# BE_PROJECT_PCB_final.net
KiCad netlist of a schematic drawn in EAGLE
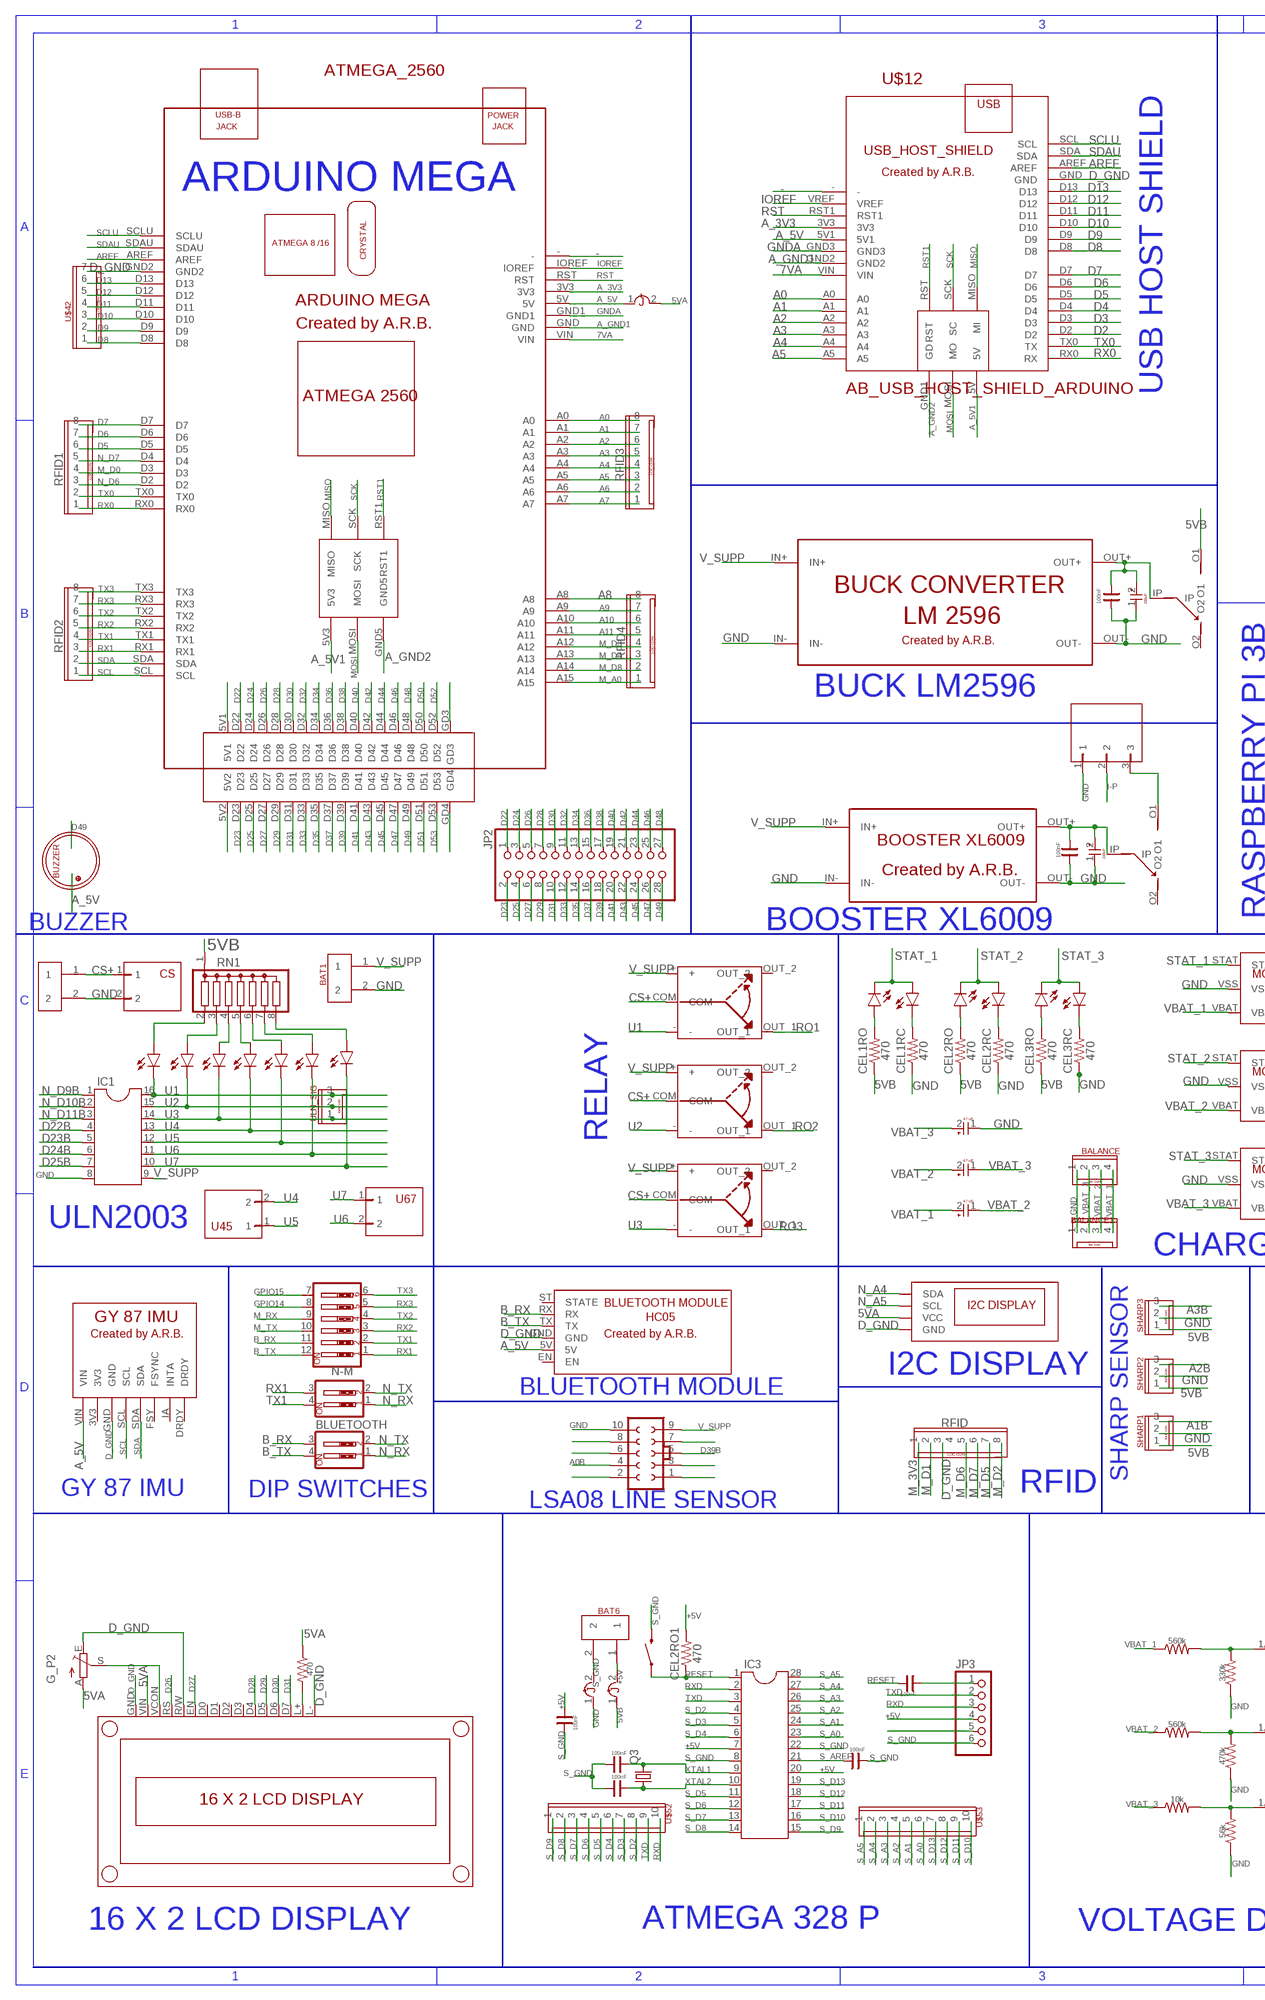
[diagram p0: schematic, sheet 1, part 1 of 3]
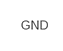
[diagram p1: schematic, sheet 1, part 2 of 3]
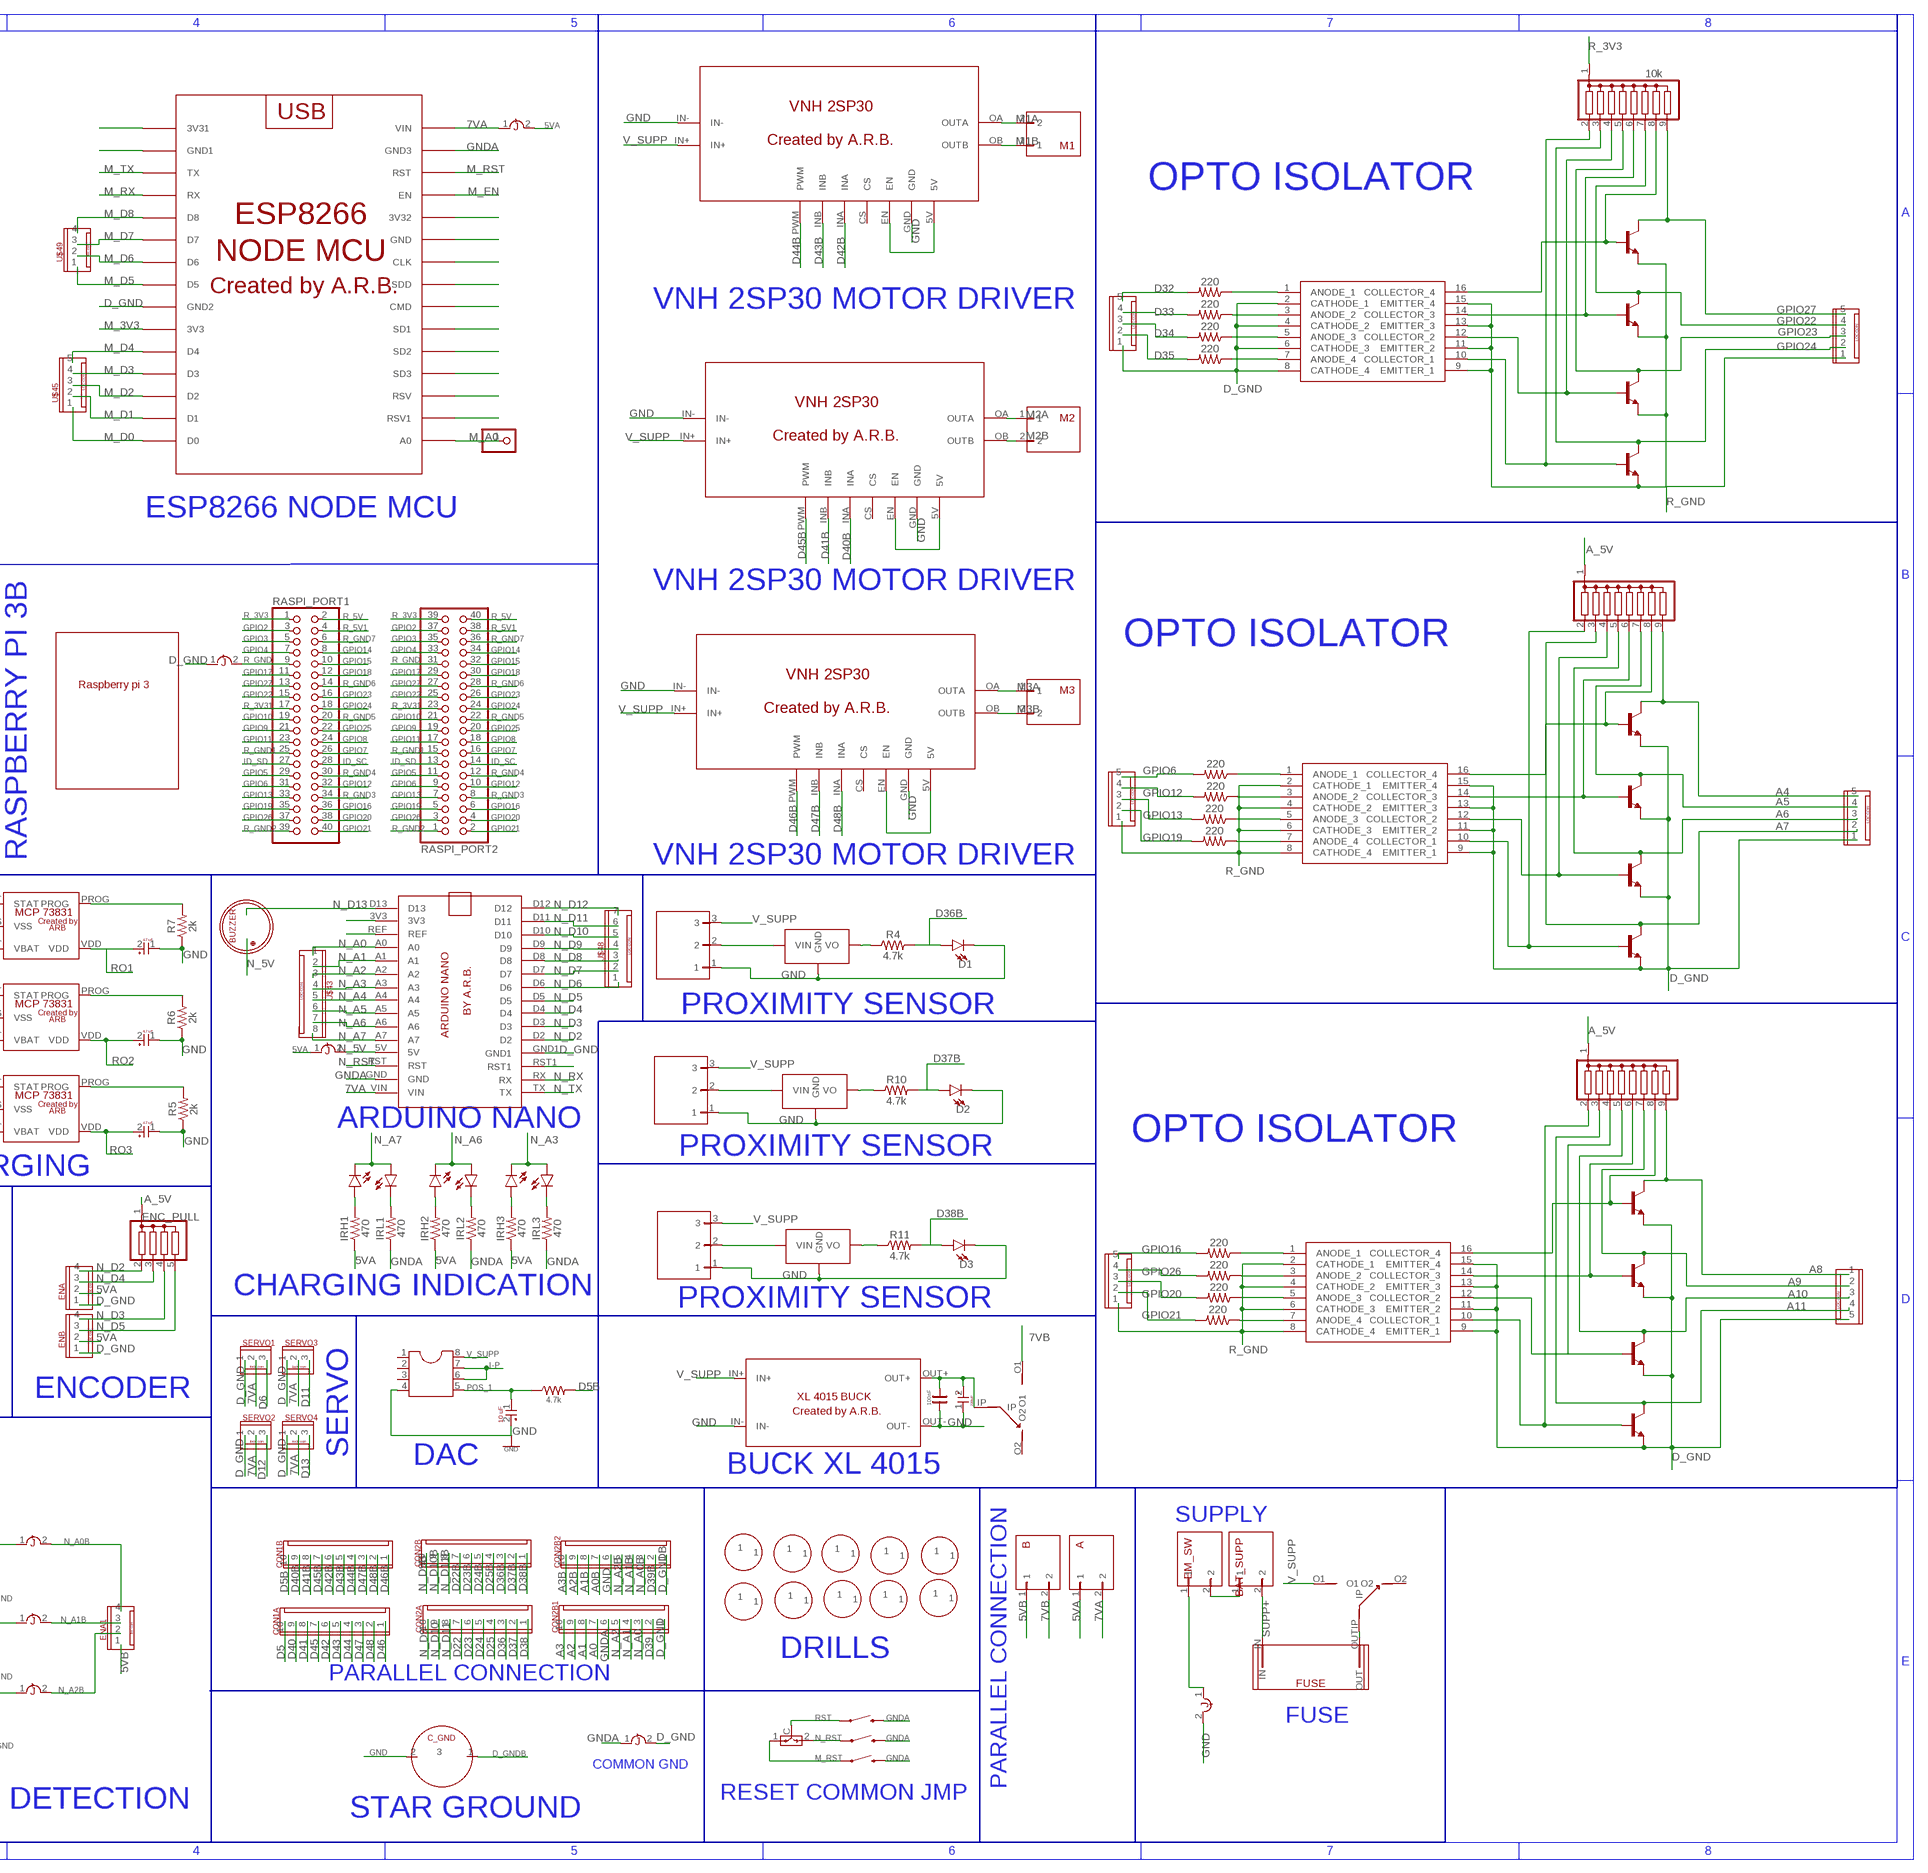
[diagram p2: schematic, sheet 1, part 3 of 3]

(export (version "E")
  (design (tool "Eeschema 10.0.6"))
  (components
    (comp (ref "10K")
      (value "10k")
      (footprint "eagle-import:SIL9")
      (libsource (lib "eagle-import") (part "G08R"))
    )
    (comp (ref "A")
      (value "AB_RIGHT_TER_BLK")
      (footprint "eagle-import:AB_RIGHT_TER_BLK")
      (libsource (lib "eagle-import") (part "AB_RIGHT_TER_BLK"))
    )
    (comp (ref "ATMEGA_2560")
      (value "AB_ARDUINO_MEGA")
      (footprint "eagle-import:AB_ARDUINO_MEGA")
      (libsource (lib "eagle-import") (part "AB_ARDUINO_MEGA"))
    )
    (comp (ref "B")
      (value "AB_RIGHT_TER_BLK")
      (footprint "eagle-import:AB_RIGHT_TER_BLK")
      (libsource (lib "eagle-import") (part "AB_RIGHT_TER_BLK"))
    )
    (comp (ref "BALANCE")
      (value "AB_4PIN_LOC_CONNECTOR")
      (footprint "eagle-import:AB_4PIN_LOC_CONNECTOR")
      (libsource (lib "eagle-import") (part "AB_4PIN_LOC_CONNECTOR"))
    )
    (comp (ref "BALANCE1")
      (value "AB_4PIN_LOC_CONNECTOR")
      (footprint "eagle-import:AB_4PIN_LOC_CONNECTOR")
      (libsource (lib "eagle-import") (part "AB_4PIN_LOC_CONNECTOR"))
    )
    (comp (ref "BAT1")
      (value "AB_SCREW_TERMINAL_5MM_2PIN")
      (footprint "eagle-import:AB_SCREW_TERMINAL_5MM_2PIN")
      (libsource (lib "eagle-import") (part "AB_SCREW_TERMINAL_5MM_2PIN"))
    )
    (comp (ref "BAT6")
      (value "AB_SCREW_TERMINAL_5MM_2PIN")
      (footprint "eagle-import:AB_SCREW_TERMINAL_5MM_2PIN")
      (libsource (lib "eagle-import") (part "AB_SCREW_TERMINAL_5MM_2PIN"))
    )
    (comp (ref "BAT_SUPP")
      (value "AB_RIGHT_TER_BLK")
      (footprint "eagle-import:AB_RIGHT_TER_BLK")
      (libsource (lib "eagle-import") (part "AB_RIGHT_TER_BLK"))
    )
    (comp (ref "BC547")
      (value "BC547")
      (footprint "eagle-import:TO92")
      (libsource (lib "eagle-import") (part "BC547"))
    )
    (comp (ref "BLUETOOTH")
      (value "SW_DIP-2")
      (footprint "eagle-import:EDG-02")
      (libsource (lib "eagle-import") (part "SW_DIP-2"))
    )
    (comp (ref "C1")
      (value "100nF")
      (footprint "eagle-import:C020-035X018")
      (libsource (lib "eagle-import") (part "CNP-C020-035X018"))
    )
    (comp (ref "C2")
      (value "100nF")
      (footprint "eagle-import:C020-035X018")
      (libsource (lib "eagle-import") (part "CNP-C020-035X018"))
    )
    (comp (ref "C3")
      (value "100nF")
      (footprint "eagle-import:C020-035X018")
      (libsource (lib "eagle-import") (part "CNP-C020-035X018"))
    )
    (comp (ref "C4")
      (value "100nF")
      (footprint "eagle-import:C020-035X018")
      (libsource (lib "eagle-import") (part "CNP-C020-035X018"))
    )
    (comp (ref "C5")
      (value "100nF")
      (footprint "eagle-import:C020-035X018")
      (libsource (lib "eagle-import") (part "CNP-C020-035X018"))
    )
    (comp (ref "C6")
      (value "100nF")
      (footprint "eagle-import:C020-035X018")
      (libsource (lib "eagle-import") (part "CNP-C020-035X018"))
    )
    (comp (ref "C7")
      (value "100nF")
      (footprint "eagle-import:C020-035X018")
      (libsource (lib "eagle-import") (part "CNP-C020-035X018"))
    )
    (comp (ref "C8")
      (value "100nF")
      (footprint "eagle-import:C020-035X018")
      (libsource (lib "eagle-import") (part "CNP-C020-035X018"))
    )
    (comp (ref "CEL1CC")
      (value "LED-3MM-NO_SILK")
      (footprint "eagle-import:LED_3MM-NS")
      (libsource (lib "eagle-import") (part "LED-3MM-NO_SILK"))
    )
    (comp (ref "CEL1CO")
      (value "LED-3MM-NO_SILK")
      (footprint "eagle-import:LED_3MM-NS")
      (libsource (lib "eagle-import") (part "LED-3MM-NO_SILK"))
    )
    (comp (ref "CEL1RC")
      (value "470")
      (footprint "eagle-import:AXIAL-0.3")
      (libsource (lib "eagle-import") (part "RESISTORAXIAL-0.3"))
    )
    (comp (ref "CEL1RO")
      (value "470")
      (footprint "eagle-import:AXIAL-0.3")
      (libsource (lib "eagle-import") (part "RESISTORAXIAL-0.3"))
    )
    (comp (ref "CEL2CC")
      (value "LED-3MM-NO_SILK")
      (footprint "eagle-import:LED_3MM-NS")
      (libsource (lib "eagle-import") (part "LED-3MM-NO_SILK"))
    )
    (comp (ref "CEL2CO")
      (value "LED-3MM-NO_SILK")
      (footprint "eagle-import:LED_3MM-NS")
      (libsource (lib "eagle-import") (part "LED-3MM-NO_SILK"))
    )
    (comp (ref "CEL2RC")
      (value "470")
      (footprint "eagle-import:AXIAL-0.3")
      (libsource (lib "eagle-import") (part "RESISTORAXIAL-0.3"))
    )
    (comp (ref "CEL2RO")
      (value "470")
      (footprint "eagle-import:AXIAL-0.3")
      (libsource (lib "eagle-import") (part "RESISTORAXIAL-0.3"))
    )
    (comp (ref "CEL2RO1")
      (value "470")
      (footprint "eagle-import:AXIAL-0.3")
      (libsource (lib "eagle-import") (part "RESISTORAXIAL-0.3"))
    )
    (comp (ref "CEL3CC")
      (value "LED-3MM-NO_SILK")
      (footprint "eagle-import:LED_3MM-NS")
      (libsource (lib "eagle-import") (part "LED-3MM-NO_SILK"))
    )
    (comp (ref "CEL3CO")
      (value "LED-3MM-NO_SILK")
      (footprint "eagle-import:LED_3MM-NS")
      (libsource (lib "eagle-import") (part "LED-3MM-NO_SILK"))
    )
    (comp (ref "CEL3RC")
      (value "470")
      (footprint "eagle-import:AXIAL-0.3")
      (libsource (lib "eagle-import") (part "RESISTORAXIAL-0.3"))
    )
    (comp (ref "CEL3RO")
      (value "470")
      (footprint "eagle-import:AXIAL-0.3")
      (libsource (lib "eagle-import") (part "RESISTORAXIAL-0.3"))
    )
    (comp (ref "CON1A")
      (value "AB_10PIN_LOC_CONNECTOR")
      (footprint "eagle-import:AB_10PIN_LOC_CONNECTOR")
      (libsource (lib "eagle-import") (part "AB_10PIN_LOC_CONNECTOR"))
    )
    (comp (ref "CON1B")
      (value "AB_10PIN_LOC_CONNECTOR")
      (footprint "eagle-import:AB_10PIN_LOC_CONNECTOR")
      (libsource (lib "eagle-import") (part "AB_10PIN_LOC_CONNECTOR"))
    )
    (comp (ref "CON2A")
      (value "AB_10PIN_LOC_CONNECTOR")
      (footprint "eagle-import:AB_10PIN_LOC_CONNECTOR")
      (libsource (lib "eagle-import") (part "AB_10PIN_LOC_CONNECTOR"))
    )
    (comp (ref "CON2B")
      (value "AB_10PIN_LOC_CONNECTOR")
      (footprint "eagle-import:AB_10PIN_LOC_CONNECTOR")
      (libsource (lib "eagle-import") (part "AB_10PIN_LOC_CONNECTOR"))
    )
    (comp (ref "CON2B1")
      (value "AB_10PIN_LOC_CONNECTOR")
      (footprint "eagle-import:AB_10PIN_LOC_CONNECTOR")
      (libsource (lib "eagle-import") (part "AB_10PIN_LOC_CONNECTOR"))
    )
    (comp (ref "CON2B2")
      (value "AB_10PIN_LOC_CONNECTOR")
      (footprint "eagle-import:AB_10PIN_LOC_CONNECTOR")
      (libsource (lib "eagle-import") (part "AB_10PIN_LOC_CONNECTOR"))
    )
    (comp (ref "CS")
      (value "AB_RIGHT_TER_BLK")
      (footprint "eagle-import:AB_RIGHT_TER_BLK")
      (libsource (lib "eagle-import") (part "AB_RIGHT_TER_BLK"))
    )
    (comp (ref "C_GND")
      (value "AB_JOINT_GND")
      (footprint "eagle-import:AB_JOINT_GND")
      (libsource (lib "eagle-import") (part "AB_JOINT_GND"))
    )
    (comp (ref "D1")
      (value "LED-3MM-NO_SILK")
      (footprint "eagle-import:LED_3MM-NS")
      (libsource (lib "eagle-import") (part "LED-3MM-NO_SILK"))
    )
    (comp (ref "D2")
      (value "LED-3MM-NO_SILK")
      (footprint "eagle-import:LED_3MM-NS")
      (libsource (lib "eagle-import") (part "LED-3MM-NO_SILK"))
    )
    (comp (ref "D3")
      (value "LED-3MM-NO_SILK")
      (footprint "eagle-import:LED_3MM-NS")
      (libsource (lib "eagle-import") (part "LED-3MM-NO_SILK"))
    )
    (comp (ref "EM_SW")
      (value "AB_RIGHT_TER_BLK")
      (footprint "eagle-import:AB_RIGHT_TER_BLK")
      (libsource (lib "eagle-import") (part "AB_RIGHT_TER_BLK"))
    )
    (comp (ref "ENA")
      (value "AB_4PIN_LOC_CONNECTOR")
      (footprint "eagle-import:AB_4PIN_LOC_CONNECTOR")
      (libsource (lib "eagle-import") (part "AB_4PIN_LOC_CONNECTOR"))
    )
    (comp (ref "ENA1")
      (value "AB_4PIN_LOC_CONNECTOR")
      (footprint "eagle-import:AB_4PIN_LOC_CONNECTOR")
      (libsource (lib "eagle-import") (part "AB_4PIN_LOC_CONNECTOR"))
    )
    (comp (ref "ENB")
      (value "AB_4PIN_LOC_CONNECTOR")
      (footprint "eagle-import:AB_4PIN_LOC_CONNECTOR")
      (libsource (lib "eagle-import") (part "AB_4PIN_LOC_CONNECTOR"))
    )
    (comp (ref "ENC_PULL")
      (value "G04R")
      (footprint "eagle-import:SIL5")
      (libsource (lib "eagle-import") (part "G04R"))
    )
    (comp (ref "FUSE")
      (value "AB_FUSE_HOLDER")
      (footprint "eagle-import:AB_FUSE_HOLDER")
      (libsource (lib "eagle-import") (part "AB_FUSE_HOLDER"))
    )
    (comp (ref "G_P2")
      (value "TRIM_EU-RS3")
      (footprint "eagle-import:RS3")
      (libsource (lib "eagle-import") (part "TRIM_EU-RS3"))
    )
    (comp (ref "IC1")
      (value "DIL16S")
      (footprint "eagle-import:SOCKET-16")
      (libsource (lib "eagle-import") (part "DIL16S"))
    )
    (comp (ref "IC2")
      (value "DIL8S")
      (footprint "eagle-import:SOCKET-08")
      (fields (field (name "SPICEPREFIX") "X"))
      (libsource (lib "eagle-import") (part "DIL8S"))
    )
    (comp (ref "IC3")
      (value "DIL28-3")
      (footprint "eagle-import:DIL28-3")
      (libsource (lib "eagle-import") (part "DIL28-3"))
    )
    (comp (ref "IC8")
      (value "TLP281-4(GB,J,F)")
      (footprint "eagle-import:SOIC127P700X210-16N")
      (fields
        (field (name "MOUSER_PART_NUMBER") "757-TLP281-4(GB,J,F)")
        (field (name "RS_PART_NUMBER") "7603227P")
      )
      (libsource (lib "eagle-import") (part "TLP281-4(GB,J,F)"))
    )
    (comp (ref "IC9")
      (value "TLP281-4(GB,J,F)")
      (footprint "eagle-import:SOIC127P700X210-16N")
      (fields
        (field (name "MOUSER_PART_NUMBER") "757-TLP281-4(GB,J,F)")
        (field (name "RS_PART_NUMBER") "7603227P")
      )
      (libsource (lib "eagle-import") (part "TLP281-4(GB,J,F)"))
    )
    (comp (ref "IC10")
      (value "TLP281-4(GB,J,F)")
      (footprint "eagle-import:SOIC127P700X210-16N")
      (fields
        (field (name "MOUSER_PART_NUMBER") "757-TLP281-4(GB,J,F)")
        (field (name "RS_PART_NUMBER") "7603227P")
      )
      (libsource (lib "eagle-import") (part "TLP281-4(GB,J,F)"))
    )
    (comp (ref "IH1")
      (value "LED-3MM-NO_SILK")
      (footprint "eagle-import:LED_3MM-NS")
      (libsource (lib "eagle-import") (part "LED-3MM-NO_SILK"))
    )
    (comp (ref "IH2")
      (value "LED-3MM-NO_SILK")
      (footprint "eagle-import:LED_3MM-NS")
      (libsource (lib "eagle-import") (part "LED-3MM-NO_SILK"))
    )
    (comp (ref "IH3")
      (value "LED-3MM-NO_SILK")
      (footprint "eagle-import:LED_3MM-NS")
      (libsource (lib "eagle-import") (part "LED-3MM-NO_SILK"))
    )
    (comp (ref "IL1")
      (value "LED-3MM-NO_SILK")
      (footprint "eagle-import:LED_3MM-NS")
      (libsource (lib "eagle-import") (part "LED-3MM-NO_SILK"))
    )
    (comp (ref "IL2")
      (value "LED-3MM-NO_SILK")
      (footprint "eagle-import:LED_3MM-NS")
      (libsource (lib "eagle-import") (part "LED-3MM-NO_SILK"))
    )
    (comp (ref "IL3")
      (value "LED-3MM-NO_SILK")
      (footprint "eagle-import:LED_3MM-NS")
      (libsource (lib "eagle-import") (part "LED-3MM-NO_SILK"))
    )
    (comp (ref "IRH1")
      (value "470")
      (footprint "eagle-import:AXIAL-0.3")
      (libsource (lib "eagle-import") (part "RESISTORAXIAL-0.3"))
    )
    (comp (ref "IRH2")
      (value "470")
      (footprint "eagle-import:AXIAL-0.3")
      (libsource (lib "eagle-import") (part "RESISTORAXIAL-0.3"))
    )
    (comp (ref "IRH3")
      (value "470")
      (footprint "eagle-import:AXIAL-0.3")
      (libsource (lib "eagle-import") (part "RESISTORAXIAL-0.3"))
    )
    (comp (ref "IRL1")
      (value "470")
      (footprint "eagle-import:AXIAL-0.3")
      (libsource (lib "eagle-import") (part "RESISTORAXIAL-0.3"))
    )
    (comp (ref "IRL2")
      (value "470")
      (footprint "eagle-import:AXIAL-0.3")
      (libsource (lib "eagle-import") (part "RESISTORAXIAL-0.3"))
    )
    (comp (ref "IRL3")
      (value "470")
      (footprint "eagle-import:AXIAL-0.3")
      (libsource (lib "eagle-import") (part "RESISTORAXIAL-0.3"))
    )
    (comp (ref "JP1")
      (value "PINHD-1X1")
      (footprint "eagle-import:1X01")
      (libsource (lib "eagle-import") (part "PINHD-1X1"))
    )
    (comp (ref "JP2")
      (value "PINHD-2X14")
      (footprint "eagle-import:2X14")
      (libsource (lib "eagle-import") (part "PINHD-2X14"))
    )
    (comp (ref "JP3")
      (value "PINHD-1X6")
      (footprint "eagle-import:1X06")
      (libsource (lib "eagle-import") (part "PINHD-1X6"))
    )
    (comp (ref "L1")
      (value "LED-3MM-NO_SILK")
      (footprint "eagle-import:LED_3MM-NS")
      (libsource (lib "eagle-import") (part "LED-3MM-NO_SILK"))
    )
    (comp (ref "L2")
      (value "LED-3MM-NO_SILK")
      (footprint "eagle-import:LED_3MM-NS")
      (libsource (lib "eagle-import") (part "LED-3MM-NO_SILK"))
    )
    (comp (ref "L3")
      (value "LED-3MM-NO_SILK")
      (footprint "eagle-import:LED_3MM-NS")
      (libsource (lib "eagle-import") (part "LED-3MM-NO_SILK"))
    )
    (comp (ref "L4")
      (value "LED-3MM-NO_SILK")
      (footprint "eagle-import:LED_3MM-NS")
      (libsource (lib "eagle-import") (part "LED-3MM-NO_SILK"))
    )
    (comp (ref "L5")
      (value "LED-3MM-NO_SILK")
      (footprint "eagle-import:LED_3MM-NS")
      (libsource (lib "eagle-import") (part "LED-3MM-NO_SILK"))
    )
    (comp (ref "L6")
      (value "LED-3MM-NO_SILK")
      (footprint "eagle-import:LED_3MM-NS")
      (libsource (lib "eagle-import") (part "LED-3MM-NO_SILK"))
    )
    (comp (ref "L7")
      (value "LED-3MM-NO_SILK")
      (footprint "eagle-import:LED_3MM-NS")
      (libsource (lib "eagle-import") (part "LED-3MM-NO_SILK"))
    )
    (comp (ref "LSA_2")
      (value "LSA1")
      (footprint "eagle-import:S10V")
      (libsource (lib "eagle-import") (part "SOCKET-10V"))
    )
    (comp (ref "M1")
      (value "AB_RIGHT_TER_BLK")
      (footprint "eagle-import:AB_RIGHT_TER_BLK")
      (libsource (lib "eagle-import") (part "AB_RIGHT_TER_BLK"))
    )
    (comp (ref "M2")
      (value "AB_RIGHT_TER_BLK")
      (footprint "eagle-import:AB_RIGHT_TER_BLK")
      (libsource (lib "eagle-import") (part "AB_RIGHT_TER_BLK"))
    )
    (comp (ref "M3")
      (value "AB_RIGHT_TER_BLK")
      (footprint "eagle-import:AB_RIGHT_TER_BLK")
      (libsource (lib "eagle-import") (part "AB_RIGHT_TER_BLK"))
    )
    (comp (ref "MEGA_RST")
      (value "MOMENTARY-SWITCH-SPST-PTH-6.0MM")
      (footprint "eagle-import:TACTILE_SWITCH_PTH_6.0MM")
      (libsource (lib "eagle-import") (part "MOMENTARY-SWITCH-SPST-PTH-6.0MM"))
    )
    (comp (ref "MEGA_RST1")
      (value "MOMENTARY-SWITCH-SPST-PTH-6.0MM")
      (footprint "eagle-import:TACTILE_SWITCH_PTH_6.0MM")
      (libsource (lib "eagle-import") (part "MOMENTARY-SWITCH-SPST-PTH-6.0MM"))
    )
    (comp (ref "M_RST")
      (value "MOMENTARY-SWITCH-SPST-PTH-6.0MM")
      (footprint "eagle-import:TACTILE_SWITCH_PTH_6.0MM")
      (libsource (lib "eagle-import") (part "MOMENTARY-SWITCH-SPST-PTH-6.0MM"))
    )
    (comp (ref "N-M")
      (value "SW_DIP-2")
      (footprint "eagle-import:EDG-02")
      (libsource (lib "eagle-import") (part "SW_DIP-2"))
    )
    (comp (ref "NANO")
      (value "AB_JUMPER_ONE_WAY")
      (footprint "eagle-import:AB_JUMPER_ONE_WAY")
      (libsource (lib "eagle-import") (part "AB_JUMPER_ONE_WAY"))
    )
    (comp (ref "NODEMCU")
      (value "AB_JUMPER_ONE_WAY")
      (footprint "eagle-import:AB_JUMPER_ONE_WAY")
      (libsource (lib "eagle-import") (part "AB_JUMPER_ONE_WAY"))
    )
    (comp (ref "N_RST")
      (value "MOMENTARY-SWITCH-SPST-PTH-6.0MM")
      (footprint "eagle-import:TACTILE_SWITCH_PTH_6.0MM")
      (libsource (lib "eagle-import") (part "MOMENTARY-SWITCH-SPST-PTH-6.0MM"))
    )
    (comp (ref "OISO1")
      (value "AB_5PIN_LOC_CONNECTOR")
      (footprint "eagle-import:AB_5PIN_LOC_CONNECTOR")
      (fields (field (name "SPICEPREFIX") "X"))
      (libsource (lib "eagle-import") (part "AB_5PIN_LOC_CONNECTOR"))
    )
    (comp (ref "OISO2")
      (value "AB_5PIN_LOC_CONNECTOR")
      (footprint "eagle-import:AB_5PIN_LOC_CONNECTOR")
      (fields (field (name "SPICEPREFIX") "X"))
      (libsource (lib "eagle-import") (part "AB_5PIN_LOC_CONNECTOR"))
    )
    (comp (ref "OISO3")
      (value "AB_5PIN_LOC_CONNECTOR")
      (footprint "eagle-import:AB_5PIN_LOC_CONNECTOR")
      (fields (field (name "SPICEPREFIX") "X"))
      (libsource (lib "eagle-import") (part "AB_5PIN_LOC_CONNECTOR"))
    )
    (comp (ref "OISO4")
      (value "AB_5PIN_LOC_CONNECTOR")
      (footprint "eagle-import:AB_5PIN_LOC_CONNECTOR")
      (fields (field (name "SPICEPREFIX") "X"))
      (libsource (lib "eagle-import") (part "AB_5PIN_LOC_CONNECTOR"))
    )
    (comp (ref "OISO5")
      (value "AB_5PIN_LOC_CONNECTOR")
      (footprint "eagle-import:AB_5PIN_LOC_CONNECTOR")
      (fields (field (name "SPICEPREFIX") "X"))
      (libsource (lib "eagle-import") (part "AB_5PIN_LOC_CONNECTOR"))
    )
    (comp (ref "OISO6")
      (value "AB_5PIN_LOC_CONNECTOR")
      (footprint "eagle-import:AB_5PIN_LOC_CONNECTOR")
      (fields (field (name "SPICEPREFIX") "X"))
      (libsource (lib "eagle-import") (part "AB_5PIN_LOC_CONNECTOR"))
    )
    (comp (ref "PPR_R1")
      (value "4.7k")
      (footprint "eagle-import:AXIAL-0.3")
      (libsource (lib "eagle-import") (part "RESISTORAXIAL-0.3"))
    )
    (comp (ref "PROX1")
      (value "AB_RIGHT_TER_BLK_3PIN")
      (footprint "eagle-import:AB_RIGHT_TER_BLK_3PIN")
      (libsource (lib "eagle-import") (part "AB_RIGHT_TER_BLK_3PIN"))
    )
    (comp (ref "PROX2")
      (value "AB_RIGHT_TER_BLK_3PIN")
      (footprint "eagle-import:AB_RIGHT_TER_BLK_3PIN")
      (libsource (lib "eagle-import") (part "AB_RIGHT_TER_BLK_3PIN"))
    )
    (comp (ref "PROX3")
      (value "AB_RIGHT_TER_BLK_3PIN")
      (footprint "eagle-import:AB_RIGHT_TER_BLK_3PIN")
      (libsource (lib "eagle-import") (part "AB_RIGHT_TER_BLK_3PIN"))
    )
    (comp (ref "Q3")
      (value "CRYSTALHC49U-V")
      (footprint "eagle-import:HC49U-V")
      (libsource (lib "eagle-import") (part "CRYSTALHC49U-V"))
    )
    (comp (ref "R2")
      (value "560k")
      (footprint "eagle-import:AXIAL-0.3")
      (libsource (lib "eagle-import") (part "RESISTORAXIAL-0.3"))
    )
    (comp (ref "R4")
      (value "4.7k")
      (footprint "eagle-import:AXIAL-0.3")
      (libsource (lib "eagle-import") (part "RESISTORAXIAL-0.3"))
    )
    (comp (ref "R5")
      (value "2k")
      (footprint "eagle-import:AXIAL-0.3")
      (libsource (lib "eagle-import") (part "RESISTORAXIAL-0.3"))
    )
    (comp (ref "R6")
      (value "2k")
      (footprint "eagle-import:AXIAL-0.3")
      (libsource (lib "eagle-import") (part "RESISTORAXIAL-0.3"))
    )
    (comp (ref "R7")
      (value "2k")
      (footprint "eagle-import:AXIAL-0.3")
      (libsource (lib "eagle-import") (part "RESISTORAXIAL-0.3"))
    )
    (comp (ref "R10")
      (value "4.7k")
      (footprint "eagle-import:AXIAL-0.3")
      (libsource (lib "eagle-import") (part "RESISTORAXIAL-0.3"))
    )
    (comp (ref "R11")
      (value "4.7k")
      (footprint "eagle-import:AXIAL-0.3")
      (libsource (lib "eagle-import") (part "RESISTORAXIAL-0.3"))
    )
    (comp (ref "R17")
      (value "470")
      (footprint "eagle-import:AXIAL-0.3")
      (libsource (lib "eagle-import") (part "RESISTORAXIAL-0.3"))
    )
    (comp (ref "R18")
      (value "220")
      (footprint "eagle-import:AXIAL-0.3")
      (libsource (lib "eagle-import") (part "RESISTORAXIAL-0.3"))
    )
    (comp (ref "R19")
      (value "220")
      (footprint "eagle-import:AXIAL-0.3")
      (libsource (lib "eagle-import") (part "RESISTORAXIAL-0.3"))
    )
    (comp (ref "R20")
      (value "220")
      (footprint "eagle-import:AXIAL-0.3")
      (libsource (lib "eagle-import") (part "RESISTORAXIAL-0.3"))
    )
    (comp (ref "R21")
      (value "220")
      (footprint "eagle-import:AXIAL-0.3")
      (libsource (lib "eagle-import") (part "RESISTORAXIAL-0.3"))
    )
    (comp (ref "R22")
      (value "220")
      (footprint "eagle-import:AXIAL-0.3")
      (libsource (lib "eagle-import") (part "RESISTORAXIAL-0.3"))
    )
    (comp (ref "R23")
      (value "220")
      (footprint "eagle-import:AXIAL-0.3")
      (libsource (lib "eagle-import") (part "RESISTORAXIAL-0.3"))
    )
    (comp (ref "R24")
      (value "220")
      (footprint "eagle-import:AXIAL-0.3")
      (libsource (lib "eagle-import") (part "RESISTORAXIAL-0.3"))
    )
    (comp (ref "R25")
      (value "220")
      (footprint "eagle-import:AXIAL-0.3")
      (libsource (lib "eagle-import") (part "RESISTORAXIAL-0.3"))
    )
    (comp (ref "R26")
      (value "220")
      (footprint "eagle-import:AXIAL-0.3")
      (libsource (lib "eagle-import") (part "RESISTORAXIAL-0.3"))
    )
    (comp (ref "R27")
      (value "220")
      (footprint "eagle-import:AXIAL-0.3")
      (libsource (lib "eagle-import") (part "RESISTORAXIAL-0.3"))
    )
    (comp (ref "R28")
      (value "220")
      (footprint "eagle-import:AXIAL-0.3")
      (libsource (lib "eagle-import") (part "RESISTORAXIAL-0.3"))
    )
    (comp (ref "R32")
      (value "220")
      (footprint "eagle-import:AXIAL-0.3")
      (libsource (lib "eagle-import") (part "RESISTORAXIAL-0.3"))
    )
    (comp (ref "R34")
      (value "330k")
      (footprint "eagle-import:AXIAL-0.3")
      (libsource (lib "eagle-import") (part "RESISTORAXIAL-0.3"))
    )
    (comp (ref "R35")
      (value "560k")
      (footprint "eagle-import:AXIAL-0.3")
      (libsource (lib "eagle-import") (part "RESISTORAXIAL-0.3"))
    )
    (comp (ref "R36")
      (value "470k")
      (footprint "eagle-import:AXIAL-0.3")
      (libsource (lib "eagle-import") (part "RESISTORAXIAL-0.3"))
    )
    (comp (ref "R37")
      (value "10k")
      (footprint "eagle-import:AXIAL-0.3")
      (libsource (lib "eagle-import") (part "RESISTORAXIAL-0.3"))
    )
    (comp (ref "R38")
      (value "56k")
      (footprint "eagle-import:AXIAL-0.3")
      (libsource (lib "eagle-import") (part "RESISTORAXIAL-0.3"))
    )
    (comp (ref "RASPI_PORT1")
      (value "PINHD-2X20")
      (footprint "eagle-import:2X20")
      (libsource (lib "eagle-import") (part "PINHD-2X20"))
    )
    (comp (ref "RASPI_PORT2")
      (value "PINHD-2X20")
      (footprint "eagle-import:2X20")
      (libsource (lib "eagle-import") (part "PINHD-2X20"))
    )
    (comp (ref "REL1")
      (value "12v")
      (footprint "eagle-import:AB_ELECTROMAGNETIC_RELAY")
      (libsource (lib "eagle-import") (part "AB_ELECTROMAGNETIC_RELAY"))
    )
    (comp (ref "REL2")
      (value "12v")
      (footprint "eagle-import:AB_ELECTROMAGNETIC_RELAY")
      (libsource (lib "eagle-import") (part "AB_ELECTROMAGNETIC_RELAY"))
    )
    (comp (ref "REL3")
      (value "12v")
      (footprint "eagle-import:AB_ELECTROMAGNETIC_RELAY")
      (libsource (lib "eagle-import") (part "AB_ELECTROMAGNETIC_RELAY"))
    )
    (comp (ref "RFID")
      (value "AB_8PIN_LOC_CONNECTOR")
      (footprint "eagle-import:AB_8PIN_LOC_CONNECTOR")
      (libsource (lib "eagle-import") (part "AB_8PIN_LOC_CONNECTOR"))
    )
    (comp (ref "RFID1")
      (value "AB_8PIN_LOC_CONNECTOR")
      (footprint "eagle-import:AB_8PIN_LOC_CONNECTOR")
      (libsource (lib "eagle-import") (part "AB_8PIN_LOC_CONNECTOR"))
    )
    (comp (ref "RFID2")
      (value "AB_8PIN_LOC_CONNECTOR")
      (footprint "eagle-import:AB_8PIN_LOC_CONNECTOR")
      (libsource (lib "eagle-import") (part "AB_8PIN_LOC_CONNECTOR"))
    )
    (comp (ref "RFID3")
      (value "AB_8PIN_LOC_CONNECTOR")
      (footprint "eagle-import:AB_8PIN_LOC_CONNECTOR")
      (libsource (lib "eagle-import") (part "AB_8PIN_LOC_CONNECTOR"))
    )
    (comp (ref "RFID4")
      (value "AB_8PIN_LOC_CONNECTOR")
      (footprint "eagle-import:AB_8PIN_LOC_CONNECTOR")
      (libsource (lib "eagle-import") (part "AB_8PIN_LOC_CONNECTOR"))
    )
    (comp (ref "RN1")
      (value "G07R")
      (footprint "eagle-import:SIL8")
      (libsource (lib "eagle-import") (part "G07R"))
    )
    (comp (ref "RN6")
      (value "G08R")
      (footprint "eagle-import:SIL9")
      (libsource (lib "eagle-import") (part "G08R"))
    )
    (comp (ref "RN7")
      (value "G08R")
      (footprint "eagle-import:SIL9")
      (libsource (lib "eagle-import") (part "G08R"))
    )
    (comp (ref "SERVO1")
      (value "AB_3PIN_LOC_CONNECTOR")
      (footprint "eagle-import:AB_3PIN_LOC_CONNECTOR")
      (libsource (lib "eagle-import") (part "AB_3PIN_LOC_CONNECTOR"))
    )
    (comp (ref "SERVO2")
      (value "AB_3PIN_LOC_CONNECTOR")
      (footprint "eagle-import:AB_3PIN_LOC_CONNECTOR")
      (libsource (lib "eagle-import") (part "AB_3PIN_LOC_CONNECTOR"))
    )
    (comp (ref "SERVO3")
      (value "AB_3PIN_LOC_CONNECTOR")
      (footprint "eagle-import:AB_3PIN_LOC_CONNECTOR")
      (libsource (lib "eagle-import") (part "AB_3PIN_LOC_CONNECTOR"))
    )
    (comp (ref "SERVO4")
      (value "AB_3PIN_LOC_CONNECTOR")
      (footprint "eagle-import:AB_3PIN_LOC_CONNECTOR")
      (libsource (lib "eagle-import") (part "AB_3PIN_LOC_CONNECTOR"))
    )
    (comp (ref "SHARP1")
      (value "AB_3PIN_LOC_CONNECTOR")
      (footprint "eagle-import:AB_3PIN_LOC_CONNECTOR")
      (libsource (lib "eagle-import") (part "AB_3PIN_LOC_CONNECTOR"))
    )
    (comp (ref "SHARP2")
      (value "AB_3PIN_LOC_CONNECTOR")
      (footprint "eagle-import:AB_3PIN_LOC_CONNECTOR")
      (libsource (lib "eagle-import") (part "AB_3PIN_LOC_CONNECTOR"))
    )
    (comp (ref "SHARP3")
      (value "AB_3PIN_LOC_CONNECTOR")
      (footprint "eagle-import:AB_3PIN_LOC_CONNECTOR")
      (libsource (lib "eagle-import") (part "AB_3PIN_LOC_CONNECTOR"))
    )
    (comp (ref "SW1")
      (value "SW_DIP-6")
      (footprint "eagle-import:EDG-06")
      (libsource (lib "eagle-import") (part "SW_DIP-6"))
    )
    (comp (ref "TR14")
      (value "BC547")
      (footprint "eagle-import:TO92")
      (libsource (lib "eagle-import") (part "BC547"))
    )
    (comp (ref "TR15")
      (value "BC547")
      (footprint "eagle-import:TO92")
      (libsource (lib "eagle-import") (part "BC547"))
    )
    (comp (ref "TR16")
      (value "BC547")
      (footprint "eagle-import:TO92")
      (libsource (lib "eagle-import") (part "BC547"))
    )
    (comp (ref "TR17")
      (value "BC547")
      (footprint "eagle-import:TO92")
      (libsource (lib "eagle-import") (part "BC547"))
    )
    (comp (ref "TR18")
      (value "BC547")
      (footprint "eagle-import:TO92")
      (libsource (lib "eagle-import") (part "BC547"))
    )
    (comp (ref "TR19")
      (value "BC547")
      (footprint "eagle-import:TO92")
      (libsource (lib "eagle-import") (part "BC547"))
    )
    (comp (ref "TR20")
      (value "BC547")
      (footprint "eagle-import:TO92")
      (libsource (lib "eagle-import") (part "BC547"))
    )
    (comp (ref "TR21")
      (value "BC547")
      (footprint "eagle-import:TO92")
      (libsource (lib "eagle-import") (part "BC547"))
    )
    (comp (ref "TR22")
      (value "BC547")
      (footprint "eagle-import:TO92")
      (libsource (lib "eagle-import") (part "BC547"))
    )
    (comp (ref "TR23")
      (value "BC547")
      (footprint "eagle-import:TO92")
      (libsource (lib "eagle-import") (part "BC547"))
    )
    (comp (ref "TR24")
      (value "BC547")
      (footprint "eagle-import:TO92")
      (libsource (lib "eagle-import") (part "BC547"))
    )
    (comp (ref "U$1")
      (value "AB_JUMPER_ONE_WAY")
      (footprint "eagle-import:AB_JUMPER_ONE_WAY")
      (libsource (lib "eagle-import") (part "AB_JUMPER_ONE_WAY"))
    )
    (comp (ref "U$2")
      (value "AB_16X2_LCD_DISPLAY")
      (footprint "eagle-import:AB_16X2_LCD_DISPLAY")
      (libsource (lib "eagle-import") (part "AB_16X2_LCD_DISPLAY"))
    )
    (comp (ref "U$3")
      (value "AB_VNH2SP30")
      (footprint "eagle-import:AB_VNH2SP30_MODULE")
      (libsource (lib "eagle-import") (part "AB_VNH2SP30"))
    )
    (comp (ref "U$4")
      (value "ESP8266_NODEMCU_BY_AB")
      (footprint "eagle-import:AB_ESP8266_BREAKOUT")
      (libsource (lib "eagle-import") (part "ESP8266_NODEMCU_BY_AB"))
    )
    (comp (ref "U$5")
      (value "AB_RASPBERRY_PI_3")
      (footprint "eagle-import:AB_RASPBERRY_PI_3")
      (libsource (lib "eagle-import") (part "AB_RASPBERRY_PI_3"))
    )
    (comp (ref "U$6")
      (value "AB_VNH2SP30")
      (footprint "eagle-import:AB_VNH2SP30_MODULE")
      (libsource (lib "eagle-import") (part "AB_VNH2SP30"))
    )
    (comp (ref "U$7")
      (value "AB_LM2596_BUCK_CONVERTER")
      (footprint "eagle-import:AB_LM2596_BUCK_CONVERTER")
      (libsource (lib "eagle-import") (part "AB_LM2596_BUCK_CONVERTER"))
    )
    (comp (ref "U$8")
      (value "AB_XL6009_BOOST_CONVERTER")
      (footprint "eagle-import:AB_XL6009E1_BOOST_CONVERTER")
      (libsource (lib "eagle-import") (part "AB_XL6009_BOOST_CONVERTER"))
    )
    (comp (ref "U$9")
      (value "AB_VNH2SP30")
      (footprint "eagle-import:AB_VNH2SP30_MODULE")
      (libsource (lib "eagle-import") (part "AB_VNH2SP30"))
    )
    (comp (ref "U$10")
      (value "AB_GY87")
      (footprint "eagle-import:AB_IMU_GY87")
      (libsource (lib "eagle-import") (part "AB_GY87"))
    )
    (comp (ref "U$11")
      (value "AB_BLUETOOTH_HC05")
      (footprint "eagle-import:AB_BLUETOOTH_HC05")
      (libsource (lib "eagle-import") (part "AB_BLUETOOTH_HC05"))
    )
    (comp (ref "U$12")
      (value "AB_USB_HOST_SHIELD_ARDUINO")
      (footprint "eagle-import:AB_USB_HOST_SHIELD_ARDUINO")
      (libsource (lib "eagle-import") (part "AB_USB_HOST_SHIELD_ARDUINO"))
    )
    (comp (ref "U$13")
      (value "AB_XL4015_5A_")
      (footprint "eagle-import:AB_XL_4015_5A_BUCK")
      (libsource (lib "eagle-import") (part "AB_XL4015_5A_"))
    )
    (comp (ref "U$14")
      (value "AB_SW")
      (footprint "eagle-import:AB_SW")
      (libsource (lib "eagle-import") (part "AB_SW"))
    )
    (comp (ref "U$15")
      (value "AB_SW")
      (footprint "eagle-import:AB_SW")
      (libsource (lib "eagle-import") (part "AB_SW"))
    )
    (comp (ref "U$16")
      (value "AB_SW")
      (footprint "eagle-import:AB_SW")
      (libsource (lib "eagle-import") (part "AB_SW"))
    )
    (comp (ref "U$17")
      (value "AB_JUMPER_ONE_WAY")
      (footprint "eagle-import:AB_JUMPER_ONE_WAY")
      (libsource (lib "eagle-import") (part "AB_JUMPER_ONE_WAY"))
    )
    (comp (ref "U$18")
      (value "AB_MCP_73831_LIPO_CHARGER")
      (footprint "eagle-import:AB_MCP_73831_LIPO_CHARGER")
      (libsource (lib "eagle-import") (part "AB_MCP_73831_LIPO_CHARGER"))
    )
    (comp (ref "U$19")
      (value "AB_MCP_73831_LIPO_CHARGER")
      (footprint "eagle-import:AB_MCP_73831_LIPO_CHARGER")
      (libsource (lib "eagle-import") (part "AB_MCP_73831_LIPO_CHARGER"))
    )
    (comp (ref "U$20")
      (value "AB_MCP_73831_LIPO_CHARGER")
      (footprint "eagle-import:AB_MCP_73831_LIPO_CHARGER")
      (libsource (lib "eagle-import") (part "AB_MCP_73831_LIPO_CHARGER"))
    )
    (comp (ref "U$21")
      (value "4.7 uF")
      (footprint "eagle-import:AB_POL_CAP")
      (libsource (lib "eagle-import") (part "AB_POL_CAP"))
    )
    (comp (ref "U$22")
      (value "4.7 uF")
      (footprint "eagle-import:AB_POL_CAP")
      (libsource (lib "eagle-import") (part "AB_POL_CAP"))
    )
    (comp (ref "U$23")
      (value "4.7 uF")
      (footprint "eagle-import:AB_POL_CAP")
      (libsource (lib "eagle-import") (part "AB_POL_CAP"))
    )
    (comp (ref "U$24")
      (value "AB_0.91_INCH_I2C_DISPLAY")
      (footprint "eagle-import:AB_0.91INCH_I2C_DISPLAY")
      (libsource (lib "eagle-import") (part "AB_0.91_INCH_I2C_DISPLAY"))
    )
    (comp (ref "U$25")
      (value "4.7 uF")
      (footprint "eagle-import:AB_POL_CAP")
      (libsource (lib "eagle-import") (part "AB_POL_CAP"))
    )
    (comp (ref "U$26")
      (value "4.7 uF")
      (footprint "eagle-import:AB_POL_CAP")
      (libsource (lib "eagle-import") (part "AB_POL_CAP"))
    )
    (comp (ref "U$27")
      (value "4.7 uF")
      (footprint "eagle-import:AB_POL_CAP")
      (libsource (lib "eagle-import") (part "AB_POL_CAP"))
    )
    (comp (ref "U$28")
      (value "AB_BUZZER")
      (footprint "eagle-import:AB_BUZZER")
      (libsource (lib "eagle-import") (part "AB_BUZZER"))
    )
    (comp (ref "U$29")
      (value "10 uF")
      (footprint "eagle-import:AB_POL_CAP")
      (libsource (lib "eagle-import") (part "AB_POL_CAP"))
    )
    (comp (ref "U$30")
      (value "AB_JUMPER_TWO_WAY")
      (footprint "eagle-import:AB_JUMPER_TWO_WAY")
      (libsource (lib "eagle-import") (part "AB_JUMPER_TWO_WAY"))
    )
    (comp (ref "U$31")
      (value "AB_JUMPER_ONE_WAY")
      (footprint "eagle-import:AB_JUMPER_ONE_WAY")
      (libsource (lib "eagle-import") (part "AB_JUMPER_ONE_WAY"))
    )
    (comp (ref "U$32")
      (value "AB_SW")
      (footprint "eagle-import:AB_SW")
      (libsource (lib "eagle-import") (part "AB_SW"))
    )
    (comp (ref "U$33")
      (value "AB_JUMPER_ONE_WAY")
      (footprint "eagle-import:AB_JUMPER_ONE_WAY")
      (libsource (lib "eagle-import") (part "AB_JUMPER_ONE_WAY"))
    )
    (comp (ref "U$34")
      (value "220uF")
      (footprint "eagle-import:AB_POL_CAP")
      (libsource (lib "eagle-import") (part "AB_POL_CAP"))
    )
    (comp (ref "U$35")
      (value "AB_ARDUINO_NANO")
      (footprint "eagle-import:AB_ARDUINO_NANO")
      (libsource (lib "eagle-import") (part "AB_ARDUINO_NANO"))
    )
    (comp (ref "U$36")
      (value "AB_SCREW_TERMINAL_5MM_2PIN")
      (footprint "eagle-import:AB_SCREW_TERMINAL_5MM_2PIN")
      (libsource (lib "eagle-import") (part "AB_SCREW_TERMINAL_5MM_2PIN"))
    )
    (comp (ref "U$37")
      (value "220uF")
      (footprint "eagle-import:AB_POL_CAP")
      (libsource (lib "eagle-import") (part "AB_POL_CAP"))
    )
    (comp (ref "U$38")
      (value "220uF")
      (footprint "eagle-import:AB_POL_CAP")
      (libsource (lib "eagle-import") (part "AB_POL_CAP"))
    )
    (comp (ref "U$39")
      (value "AB_BUZZER")
      (footprint "eagle-import:AB_BUZZER")
      (libsource (lib "eagle-import") (part "AB_BUZZER"))
    )
    (comp (ref "U$40")
      (value "AB_JUMPER_ONE_WAY")
      (footprint "eagle-import:AB_JUMPER_ONE_WAY")
      (libsource (lib "eagle-import") (part "AB_JUMPER_ONE_WAY"))
    )
    (comp (ref "U$41")
      (value "AB_JUMPER_ONE_WAY")
      (footprint "eagle-import:AB_JUMPER_ONE_WAY")
      (libsource (lib "eagle-import") (part "AB_JUMPER_ONE_WAY"))
    )
    (comp (ref "U$42")
      (value "AB_7PIN_LOC_CONNECTOR")
      (footprint "eagle-import:AB_7PIN_LOC_CONNECTOR")
      (libsource (lib "eagle-import") (part "AB_7PIN_LOC_CONNECTOR"))
    )
    (comp (ref "U$43")
      (value "AB_8PIN_LOC_CONNECTOR")
      (footprint "eagle-import:AB_8PIN_LOC_CONNECTOR")
      (libsource (lib "eagle-import") (part "AB_8PIN_LOC_CONNECTOR"))
    )
    (comp (ref "U$44")
      (value "AB_7805_FLAT")
      (footprint "eagle-import:AB_7805_FLAT")
      (libsource (lib "eagle-import") (part "AB_7805_FLAT"))
    )
    (comp (ref "U$45")
      (value "AB_5PIN_LOC_CONNECTOR")
      (footprint "eagle-import:AB_5PIN_LOC_CONNECTOR")
      (fields (field (name "SPICEPREFIX") "X"))
      (libsource (lib "eagle-import") (part "AB_5PIN_LOC_CONNECTOR"))
    )
    (comp (ref "U$46")
      (value "AB_7805_FLAT")
      (footprint "eagle-import:AB_7805_FLAT")
      (libsource (lib "eagle-import") (part "AB_7805_FLAT"))
    )
    (comp (ref "U$47")
      (value "AB_7805_FLAT")
      (footprint "eagle-import:AB_7805_FLAT")
      (libsource (lib "eagle-import") (part "AB_7805_FLAT"))
    )
    (comp (ref "U$48")
      (value "AB_7PIN_LOC_CONNECTOR")
      (footprint "eagle-import:AB_7PIN_LOC_CONNECTOR")
      (libsource (lib "eagle-import") (part "AB_7PIN_LOC_CONNECTOR"))
    )
    (comp (ref "U$49")
      (value "AB_4PIN_LOC_CONNECTOR")
      (footprint "eagle-import:AB_4PIN_LOC_CONNECTOR")
      (libsource (lib "eagle-import") (part "AB_4PIN_LOC_CONNECTOR"))
    )
    (comp (ref "U$50")
      (value "AB_JUMPER_ONE_WAY")
      (footprint "eagle-import:AB_JUMPER_ONE_WAY")
      (libsource (lib "eagle-import") (part "AB_JUMPER_ONE_WAY"))
    )
    (comp (ref "U$51")
      (value "AB_JUMPER_ONE_WAY")
      (footprint "eagle-import:AB_JUMPER_ONE_WAY")
      (libsource (lib "eagle-import") (part "AB_JUMPER_ONE_WAY"))
    )
    (comp (ref "U$52")
      (value "AB_10PIN_LOC_CONNECTOR")
      (footprint "eagle-import:AB_10PIN_LOC_CONNECTOR")
      (libsource (lib "eagle-import") (part "AB_10PIN_LOC_CONNECTOR"))
    )
    (comp (ref "U$53")
      (value "AB_10PIN_LOC_CONNECTOR")
      (footprint "eagle-import:AB_10PIN_LOC_CONNECTOR")
      (libsource (lib "eagle-import") (part "AB_10PIN_LOC_CONNECTOR"))
    )
    (comp (ref "U$54")
      (value "AB_PLATED_DRILL_160MIL")
      (footprint "eagle-import:AB_PLATED_DRILL_160MIL")
      (libsource (lib "eagle-import") (part "AB_PLATED_DRILL_160MIL"))
    )
    (comp (ref "U$55")
      (value "AB_PLATED_DRILL_160MIL")
      (footprint "eagle-import:AB_PLATED_DRILL_160MIL")
      (libsource (lib "eagle-import") (part "AB_PLATED_DRILL_160MIL"))
    )
    (comp (ref "U$56")
      (value "AB_PLATED_DRILL_160MIL")
      (footprint "eagle-import:AB_PLATED_DRILL_160MIL")
      (libsource (lib "eagle-import") (part "AB_PLATED_DRILL_160MIL"))
    )
    (comp (ref "U$57")
      (value "AB_PLATED_DRILL_160MIL")
      (footprint "eagle-import:AB_PLATED_DRILL_160MIL")
      (libsource (lib "eagle-import") (part "AB_PLATED_DRILL_160MIL"))
    )
    (comp (ref "U$58")
      (value "AB_PLATED_DRILL_160MIL")
      (footprint "eagle-import:AB_PLATED_DRILL_160MIL")
      (libsource (lib "eagle-import") (part "AB_PLATED_DRILL_160MIL"))
    )
    (comp (ref "U$59")
      (value "AB_PLATED_DRILL_160MIL")
      (footprint "eagle-import:AB_PLATED_DRILL_160MIL")
      (libsource (lib "eagle-import") (part "AB_PLATED_DRILL_160MIL"))
    )
    (comp (ref "U$60")
      (value "AB_PLATED_DRILL_160MIL")
      (footprint "eagle-import:AB_PLATED_DRILL_160MIL")
      (libsource (lib "eagle-import") (part "AB_PLATED_DRILL_160MIL"))
    )
    (comp (ref "U$61")
      (value "AB_PLATED_DRILL_160MIL")
      (footprint "eagle-import:AB_PLATED_DRILL_160MIL")
      (libsource (lib "eagle-import") (part "AB_PLATED_DRILL_160MIL"))
    )
    (comp (ref "U$62")
      (value "AB_JUMPER_ONE_WAY")
      (footprint "eagle-import:AB_JUMPER_ONE_WAY")
      (libsource (lib "eagle-import") (part "AB_JUMPER_ONE_WAY"))
    )
    (comp (ref "U$63")
      (value "AB_PLATED_DRILL_160MIL")
      (footprint "eagle-import:AB_PLATED_DRILL_160MIL")
      (libsource (lib "eagle-import") (part "AB_PLATED_DRILL_160MIL"))
    )
    (comp (ref "U$64")
      (value "AB_PLATED_DRILL_160MIL")
      (footprint "eagle-import:AB_PLATED_DRILL_160MIL")
      (libsource (lib "eagle-import") (part "AB_PLATED_DRILL_160MIL"))
    )
    (comp (ref "U45")
      (value "AB_RIGHT_TER_BLK")
      (footprint "eagle-import:AB_RIGHT_TER_BLK")
      (libsource (lib "eagle-import") (part "AB_RIGHT_TER_BLK"))
    )
    (comp (ref "U67")
      (value "AB_RIGHT_TER_BLK")
      (footprint "eagle-import:AB_RIGHT_TER_BLK")
      (libsource (lib "eagle-import") (part "AB_RIGHT_TER_BLK"))
    )
    (comp (ref "ULN_SIG")
      (value "AB_3PIN_LOC_CONNECTOR")
      (footprint "eagle-import:AB_3PIN_LOC_CONNECTOR")
      (libsource (lib "eagle-import") (part "AB_3PIN_LOC_CONNECTOR"))
    )
    (comp (ref "V-P")
      (value "AB_RIGHT_TER_BLK_3PIN")
      (footprint "eagle-import:AB_RIGHT_TER_BLK_3PIN")
      (libsource (lib "eagle-import") (part "AB_RIGHT_TER_BLK_3PIN"))
    )
  )
  (nets
    (net (code "1") (name "+5V") (class "Default")
      (node (ref "BAT6") (pin "1") (pinfunction "1_1") (pintype "bidirectional"))
      (node (ref "C5") (pin "1") (pinfunction "1_1") (pintype "passive"))
      (node (ref "CEL2RO1") (pin "P$2") (pinfunction "2_P$2") (pintype "passive"))
      (node (ref "IC3") (pin "20") (pinfunction "20_20") (pintype "passive"))
      (node (ref "IC3") (pin "7") (pinfunction "7_7") (pintype "passive"))
      (node (ref "JP3") (pin "4") (pinfunction "4_4") (pintype "passive"))
      (node (ref "U$50") (pin "2") (pinfunction "2_2") (pintype "bidirectional"))
    )
    (net (code "2") (name "-") (class "Default")
      (node (ref "ATMEGA_2560") (pin "-") (pinfunction "-_-") (pintype "bidirectional"))
      (node (ref "U$12") (pin "-") (pinfunction "-_-") (pintype "bidirectional"))
    )
    (net (code "3") (name "5VA") (class "Default")
      (node (ref "A") (pin "1") (pinfunction "1_1") (pintype "bidirectional"))
      (node (ref "ENA") (pin "2") (pinfunction "2_2") (pintype "bidirectional"))
      (node (ref "ENB") (pin "2") (pinfunction "2_2") (pintype "bidirectional"))
      (node (ref "G_P2") (pin "A") (pinfunction "A_A") (pintype "passive"))
      (node (ref "IRH1") (pin "P$1") (pinfunction "1_P$1") (pintype "passive"))
      (node (ref "IRH2") (pin "P$1") (pinfunction "1_P$1") (pintype "passive"))
      (node (ref "IRH3") (pin "P$1") (pinfunction "1_P$1") (pintype "passive"))
      (node (ref "NANO") (pin "1") (pinfunction "1_1") (pintype "bidirectional"))
      (node (ref "NODEMCU") (pin "2") (pinfunction "2_2") (pintype "bidirectional"))
      (node (ref "R17") (pin "P$1") (pinfunction "1_P$1") (pintype "passive"))
      (node (ref "U$2") (pin "VIN") (pinfunction "VIN_VIN") (pintype "bidirectional"))
      (node (ref "U$24") (pin "VCC") (pinfunction "VCC_VCC") (pintype "bidirectional"))
      (node (ref "U$31") (pin "2") (pinfunction "2_2") (pintype "bidirectional"))
    )
    (net (code "4") (name "5VB") (class "Default")
      (node (ref "B") (pin "1") (pinfunction "1_1") (pintype "bidirectional"))
      (node (ref "CEL1RO") (pin "P$1") (pinfunction "1_P$1") (pintype "passive"))
      (node (ref "CEL2RO") (pin "P$1") (pinfunction "1_P$1") (pintype "passive"))
      (node (ref "CEL3RO") (pin "P$1") (pinfunction "1_P$1") (pintype "passive"))
      (node (ref "ENA1") (pin "1") (pinfunction "1_1") (pintype "bidirectional"))
      (node (ref "RN1") (pin "1") (pinfunction "1_1") (pintype "passive"))
      (node (ref "SHARP1") (pin "1") (pinfunction "1_1") (pintype "bidirectional"))
      (node (ref "SHARP2") (pin "1") (pinfunction "1_1") (pintype "bidirectional"))
      (node (ref "SHARP3") (pin "1") (pinfunction "1_1") (pintype "bidirectional"))
      (node (ref "U$14") (pin "O1") (pinfunction "O1_O1") (pintype "bidirectional"))
      (node (ref "U$50") (pin "1") (pinfunction "1_1") (pintype "bidirectional"))
    )
    (net (code "5") (name "7VA") (class "Default")
      (node (ref "A") (pin "2") (pinfunction "2_2") (pintype "bidirectional"))
      (node (ref "ATMEGA_2560") (pin "VIN") (pinfunction "VIN_VIN") (pintype "bidirectional"))
      (node (ref "NODEMCU") (pin "1") (pinfunction "1_1") (pintype "bidirectional"))
      (node (ref "SERVO1") (pin "2") (pinfunction "2_2") (pintype "bidirectional"))
      (node (ref "SERVO2") (pin "2") (pinfunction "2_2") (pintype "bidirectional"))
      (node (ref "SERVO3") (pin "2") (pinfunction "2_2") (pintype "bidirectional"))
      (node (ref "SERVO4") (pin "2") (pinfunction "2_2") (pintype "bidirectional"))
      (node (ref "U$12") (pin "VIN") (pinfunction "VIN_VIN") (pintype "bidirectional"))
      (node (ref "U$35") (pin "VIN") (pinfunction "VIN_VIN") (pintype "bidirectional"))
      (node (ref "U$4") (pin "VIN") (pinfunction "VIN_VIN") (pintype "bidirectional"))
    )
    (net (code "6") (name "7VB") (class "Default")
      (node (ref "B") (pin "2") (pinfunction "2_2") (pintype "bidirectional"))
      (node (ref "U$16") (pin "O1") (pinfunction "O1_O1") (pintype "bidirectional"))
    )
    (net (code "7") (name "A0") (class "Default")
      (node (ref "ATMEGA_2560") (pin "A0") (pinfunction "A0_A0") (pintype "bidirectional"))
      (node (ref "CON2B1") (pin "7") (pinfunction "7_7") (pintype "bidirectional"))
      (node (ref "RFID3") (pin "8") (pinfunction "8_8") (pintype "bidirectional"))
      (node (ref "U$12") (pin "A0") (pinfunction "A0_A0") (pintype "bidirectional"))
    )
    (net (code "8") (name "A0B") (class "Default")
      (node (ref "CON2B2") (pin "7") (pinfunction "7_7") (pintype "bidirectional"))
      (node (ref "LSA_2") (pin "4") (pinfunction "4_4") (pintype "passive"))
    )
    (net (code "9") (name "A1") (class "Default")
      (node (ref "ATMEGA_2560") (pin "A1") (pinfunction "A1_A1") (pintype "bidirectional"))
      (node (ref "CON2B1") (pin "8") (pinfunction "8_8") (pintype "bidirectional"))
      (node (ref "RFID3") (pin "7") (pinfunction "7_7") (pintype "bidirectional"))
      (node (ref "U$12") (pin "A1") (pinfunction "A1_A1") (pintype "bidirectional"))
    )
    (net (code "10") (name "A1B") (class "Default")
      (node (ref "CON2B2") (pin "8") (pinfunction "8_8") (pintype "bidirectional"))
      (node (ref "SHARP1") (pin "3") (pinfunction "3_3") (pintype "bidirectional"))
    )
    (net (code "11") (name "A2") (class "Default")
      (node (ref "ATMEGA_2560") (pin "A2") (pinfunction "A2_A2") (pintype "bidirectional"))
      (node (ref "CON2B1") (pin "9") (pinfunction "9_9") (pintype "bidirectional"))
      (node (ref "RFID3") (pin "6") (pinfunction "6_6") (pintype "bidirectional"))
      (node (ref "U$12") (pin "A2") (pinfunction "A2_A2") (pintype "bidirectional"))
    )
    (net (code "12") (name "A2B") (class "Default")
      (node (ref "CON2B2") (pin "9") (pinfunction "9_9") (pintype "bidirectional"))
      (node (ref "SHARP2") (pin "3") (pinfunction "3_3") (pintype "bidirectional"))
    )
    (net (code "13") (name "A3") (class "Default")
      (node (ref "ATMEGA_2560") (pin "A3") (pinfunction "A3_A3") (pintype "bidirectional"))
      (node (ref "CON2B1") (pin "10") (pinfunction "10_10") (pintype "bidirectional"))
      (node (ref "RFID3") (pin "5") (pinfunction "5_5") (pintype "bidirectional"))
      (node (ref "U$12") (pin "A3") (pinfunction "A3_A3") (pintype "bidirectional"))
    )
    (net (code "14") (name "A3B") (class "Default")
      (node (ref "CON2B2") (pin "10") (pinfunction "10_10") (pintype "bidirectional"))
      (node (ref "SHARP3") (pin "3") (pinfunction "3_3") (pintype "bidirectional"))
    )
    (net (code "15") (name "A4") (class "Default")
      (node (ref "ATMEGA_2560") (pin "A4") (pinfunction "A4_A4") (pintype "bidirectional"))
      (node (ref "OISO4") (pin "5") (pinfunction "5_5") (pintype "bidirectional"))
      (node (ref "RFID3") (pin "4") (pinfunction "4_4") (pintype "bidirectional"))
      (node (ref "RN6") (pin "9") (pinfunction "9_9") (pintype "passive"))
      (node (ref "TR17") (pin "3") (pinfunction "C_3") (pintype "passive"))
      (node (ref "U$12") (pin "A4") (pinfunction "A4_A4") (pintype "bidirectional"))
    )
    (net (code "16") (name "A5") (class "Default")
      (node (ref "ATMEGA_2560") (pin "A5") (pinfunction "A5_A5") (pintype "bidirectional"))
      (node (ref "OISO4") (pin "4") (pinfunction "4_4") (pintype "bidirectional"))
      (node (ref "RFID3") (pin "3") (pinfunction "3_3") (pintype "bidirectional"))
      (node (ref "RN6") (pin "7") (pinfunction "7_7") (pintype "passive"))
      (node (ref "TR18") (pin "3") (pinfunction "C_3") (pintype "passive"))
      (node (ref "U$12") (pin "A5") (pinfunction "A5_A5") (pintype "bidirectional"))
    )
    (net (code "17") (name "A6") (class "Default")
      (node (ref "ATMEGA_2560") (pin "A6") (pinfunction "A6_A6") (pintype "bidirectional"))
      (node (ref "OISO4") (pin "3") (pinfunction "3_3") (pintype "bidirectional"))
      (node (ref "RFID3") (pin "2") (pinfunction "2_2") (pintype "bidirectional"))
      (node (ref "RN6") (pin "5") (pinfunction "5_5") (pintype "passive"))
      (node (ref "TR19") (pin "3") (pinfunction "C_3") (pintype "passive"))
    )
    (net (code "18") (name "A7") (class "Default")
      (node (ref "ATMEGA_2560") (pin "A7") (pinfunction "A7_A7") (pintype "bidirectional"))
      (node (ref "OISO4") (pin "2") (pinfunction "2_2") (pintype "bidirectional"))
      (node (ref "RFID3") (pin "1") (pinfunction "1_1") (pintype "bidirectional"))
      (node (ref "RN6") (pin "3") (pinfunction "3_3") (pintype "passive"))
      (node (ref "TR20") (pin "3") (pinfunction "C_3") (pintype "passive"))
    )
    (net (code "19") (name "A8") (class "Default")
      (node (ref "ATMEGA_2560") (pin "A8") (pinfunction "A8_A8") (pintype "bidirectional"))
      (node (ref "OISO6") (pin "1") (pinfunction "1_1") (pintype "bidirectional"))
      (node (ref "RFID4") (pin "8") (pinfunction "8_8") (pintype "bidirectional"))
      (node (ref "RN7") (pin "9") (pinfunction "9_9") (pintype "passive"))
      (node (ref "TR21") (pin "3") (pinfunction "C_3") (pintype "passive"))
    )
    (net (code "20") (name "A9") (class "Default")
      (node (ref "ATMEGA_2560") (pin "A9") (pinfunction "A9_A9") (pintype "bidirectional"))
      (node (ref "OISO6") (pin "2") (pinfunction "2_2") (pintype "bidirectional"))
      (node (ref "RFID4") (pin "7") (pinfunction "7_7") (pintype "bidirectional"))
      (node (ref "RN7") (pin "7") (pinfunction "7_7") (pintype "passive"))
      (node (ref "TR22") (pin "3") (pinfunction "C_3") (pintype "passive"))
    )
    (net (code "21") (name "A10") (class "Default")
      (node (ref "ATMEGA_2560") (pin "A10") (pinfunction "A10_A10") (pintype "bidirectional"))
      (node (ref "OISO6") (pin "3") (pinfunction "3_3") (pintype "bidirectional"))
      (node (ref "RFID4") (pin "6") (pinfunction "6_6") (pintype "bidirectional"))
      (node (ref "RN7") (pin "5") (pinfunction "5_5") (pintype "passive"))
      (node (ref "TR23") (pin "3") (pinfunction "C_3") (pintype "passive"))
    )
    (net (code "22") (name "A11") (class "Default")
      (node (ref "ATMEGA_2560") (pin "A11") (pinfunction "A11_A11") (pintype "bidirectional"))
      (node (ref "OISO6") (pin "4") (pinfunction "4_4") (pintype "bidirectional"))
      (node (ref "RFID4") (pin "5") (pinfunction "5_5") (pintype "bidirectional"))
      (node (ref "RN7") (pin "3") (pinfunction "3_3") (pintype "passive"))
      (node (ref "TR24") (pin "3") (pinfunction "C_3") (pintype "passive"))
    )
    (net (code "23") (name "AREF") (class "Default")
      (node (ref "ATMEGA_2560") (pin "AREF") (pinfunction "AREF_AREF") (pintype "bidirectional"))
      (node (ref "U$12") (pin "AREF") (pinfunction "AREF_AREF") (pintype "bidirectional"))
    )
    (net (code "24") (name "A_3V3") (class "Default")
      (node (ref "ATMEGA_2560") (pin "3V3") (pinfunction "3V3_3V3") (pintype "bidirectional"))
      (node (ref "U$12") (pin "3V3") (pinfunction "3V3_3V3") (pintype "bidirectional"))
    )
    (net (code "25") (name "A_5V") (class "Default")
      (node (ref "ATMEGA_2560") (pin "5V") (pinfunction "5V_5V") (pintype "bidirectional"))
      (node (ref "ENC_PULL") (pin "1") (pinfunction "1_1") (pintype "passive"))
      (node (ref "RN6") (pin "1") (pinfunction "1_1") (pintype "passive"))
      (node (ref "RN7") (pin "1") (pinfunction "1_1") (pintype "passive"))
      (node (ref "U$10") (pin "VIN") (pinfunction "VIN_VIN") (pintype "bidirectional"))
      (node (ref "U$11") (pin "5V") (pinfunction "5V_5V") (pintype "bidirectional"))
      (node (ref "U$12") (pin "5V1") (pinfunction "5V1_5V1") (pintype "bidirectional"))
      (node (ref "U$31") (pin "1") (pinfunction "1_1") (pintype "bidirectional"))
      (node (ref "U$39") (pin "+") (pinfunction "+_+") (pintype "bidirectional"))
    )
    (net (code "26") (name "A_5V1") (class "Default")
      (node (ref "ATMEGA_2560") (pin "5V3") (pinfunction "5V3_5V3") (pintype "bidirectional"))
      (node (ref "U$12") (pin "5V") (pinfunction "5V_5V") (pintype "bidirectional"))
    )
    (net (code "27") (name "A_GND1") (class "Default")
      (node (ref "ATMEGA_2560") (pin "GND") (pinfunction "GND_GND") (pintype "bidirectional"))
      (node (ref "U$12") (pin "GND2") (pinfunction "GND2_GND2") (pintype "bidirectional"))
    )
    (net (code "28") (name "A_GND2") (class "Default")
      (node (ref "ATMEGA_2560") (pin "GND5") (pinfunction "GND5_GND5") (pintype "bidirectional"))
      (node (ref "U$12") (pin "GND1") (pinfunction "GD_GND1") (pintype "bidirectional"))
    )
    (net (code "29") (name "B_RX") (class "Default")
      (node (ref "BLUETOOTH") (pin "3") (pinfunction "3_3") (pintype "passive"))
      (node (ref "SW1") (pin "11") (pinfunction "11_11") (pintype "passive"))
      (node (ref "U$11") (pin "RX") (pinfunction "RX_RX") (pintype "bidirectional"))
    )
    (net (code "30") (name "B_TX") (class "Default")
      (node (ref "BLUETOOTH") (pin "4") (pinfunction "4_4") (pintype "passive"))
      (node (ref "SW1") (pin "12") (pinfunction "12_12") (pintype "passive"))
      (node (ref "U$11") (pin "TX") (pinfunction "TX_TX") (pintype "bidirectional"))
    )
    (net (code "31") (name "CS+") (class "Default")
      (node (ref "CS") (pin "1") (pinfunction "1_1") (pintype "bidirectional"))
      (node (ref "REL1") (pin "COM") (pinfunction "COM_COM") (pintype "bidirectional"))
      (node (ref "REL2") (pin "COM") (pinfunction "COM_COM") (pintype "bidirectional"))
      (node (ref "REL3") (pin "COM") (pinfunction "COM_COM") (pintype "bidirectional"))
      (node (ref "U$36") (pin "1") (pinfunction "1_1") (pintype "bidirectional"))
    )
    (net (code "32") (name "D2") (class "Default")
      (node (ref "U$12") (pin "D2") (pinfunction "D2_D2") (pintype "bidirectional"))
    )
    (net (code "33") (name "D3") (class "Default")
      (node (ref "U$12") (pin "D3") (pinfunction "D3_D3") (pintype "bidirectional"))
    )
    (net (code "34") (name "D4") (class "Default")
      (node (ref "U$12") (pin "D4") (pinfunction "D4_D4") (pintype "bidirectional"))
    )
    (net (code "35") (name "D5") (class "Default")
      (node (ref "ATMEGA_2560") (pin "D5") (pinfunction "D5_D5") (pintype "bidirectional"))
      (node (ref "CON1A") (pin "10") (pinfunction "10_10") (pintype "bidirectional"))
      (node (ref "RFID1") (pin "6") (pinfunction "6_6") (pintype "bidirectional"))
      (node (ref "U$12") (pin "D5") (pinfunction "D5_D5") (pintype "bidirectional"))
    )
    (net (code "36") (name "D5B") (class "Default")
      (node (ref "CON1B") (pin "10") (pinfunction "10_10") (pintype "bidirectional"))
      (node (ref "PPR_R1") (pin "P$2") (pinfunction "2_P$2") (pintype "passive"))
    )
    (net (code "37") (name "D6") (class "Default")
      (node (ref "ATMEGA_2560") (pin "D6") (pinfunction "D6_D6") (pintype "bidirectional"))
      (node (ref "RFID1") (pin "7") (pinfunction "7_7") (pintype "bidirectional"))
      (node (ref "SERVO1") (pin "3") (pinfunction "3_3") (pintype "bidirectional"))
      (node (ref "U$12") (pin "D6") (pinfunction "D6_D6") (pintype "bidirectional"))
    )
    (net (code "38") (name "D7") (class "Default")
      (node (ref "ATMEGA_2560") (pin "D7") (pinfunction "D7_D7") (pintype "bidirectional"))
      (node (ref "RFID1") (pin "8") (pinfunction "8_8") (pintype "bidirectional"))
      (node (ref "U$12") (pin "D7") (pinfunction "D7_D7") (pintype "bidirectional"))
    )
    (net (code "39") (name "D8") (class "Default")
      (node (ref "ATMEGA_2560") (pin "D8") (pinfunction "D8_D8") (pintype "bidirectional"))
      (node (ref "U$12") (pin "D8") (pinfunction "D8_D8") (pintype "bidirectional"))
      (node (ref "U$42") (pin "1") (pinfunction "1_1") (pintype "bidirectional"))
    )
    (net (code "40") (name "D9") (class "Default")
      (node (ref "ATMEGA_2560") (pin "D9") (pinfunction "D9_D9") (pintype "bidirectional"))
      (node (ref "U$12") (pin "D9") (pinfunction "D9_D9") (pintype "bidirectional"))
      (node (ref "U$42") (pin "2") (pinfunction "2_2") (pintype "bidirectional"))
    )
    (net (code "41") (name "D10") (class "Default")
      (node (ref "ATMEGA_2560") (pin "D10") (pinfunction "D10_D10") (pintype "bidirectional"))
      (node (ref "U$12") (pin "D10") (pinfunction "D10_D10") (pintype "bidirectional"))
      (node (ref "U$42") (pin "3") (pinfunction "3_3") (pintype "bidirectional"))
    )
    (net (code "42") (name "D11") (class "Default")
      (node (ref "ATMEGA_2560") (pin "D11") (pinfunction "D11_D11") (pintype "bidirectional"))
      (node (ref "SERVO3") (pin "3") (pinfunction "3_3") (pintype "bidirectional"))
      (node (ref "U$12") (pin "D11") (pinfunction "D11_D11") (pintype "bidirectional"))
      (node (ref "U$42") (pin "4") (pinfunction "4_4") (pintype "bidirectional"))
    )
    (net (code "43") (name "D12") (class "Default")
      (node (ref "ATMEGA_2560") (pin "D12") (pinfunction "D12_D12") (pintype "bidirectional"))
      (node (ref "SERVO2") (pin "3") (pinfunction "3_3") (pintype "bidirectional"))
      (node (ref "U$12") (pin "D12") (pinfunction "D12_D12") (pintype "bidirectional"))
      (node (ref "U$42") (pin "5") (pinfunction "5_5") (pintype "bidirectional"))
    )
    (net (code "44") (name "D13") (class "Default")
      (node (ref "ATMEGA_2560") (pin "D13") (pinfunction "D13_D13") (pintype "bidirectional"))
      (node (ref "SERVO4") (pin "3") (pinfunction "3_3") (pintype "bidirectional"))
      (node (ref "U$12") (pin "D13") (pinfunction "D13_D13") (pintype "bidirectional"))
      (node (ref "U$42") (pin "6") (pinfunction "6_6") (pintype "bidirectional"))
    )
    (net (code "45") (name "D22") (class "Default")
      (node (ref "ATMEGA_2560") (pin "D22") (pinfunction "D22_D22") (pintype "bidirectional"))
      (node (ref "CON2A") (pin "7") (pinfunction "7_7") (pintype "bidirectional"))
      (node (ref "JP2") (pin "1") (pinfunction "1_1") (pintype "passive"))
    )
    (net (code "46") (name "D22B") (class "Default")
      (node (ref "CON2B") (pin "7") (pinfunction "7_7") (pintype "bidirectional"))
      (node (ref "IC1") (pin "4") (pinfunction "4_4") (pintype "passive"))
    )
    (net (code "47") (name "D23") (class "Default")
      (node (ref "ATMEGA_2560") (pin "D23") (pinfunction "D23_D23") (pintype "bidirectional"))
      (node (ref "CON2A") (pin "6") (pinfunction "6_6") (pintype "bidirectional"))
      (node (ref "JP2") (pin "2") (pinfunction "2_2") (pintype "passive"))
    )
    (net (code "48") (name "D23B") (class "Default")
      (node (ref "CON2B") (pin "6") (pinfunction "6_6") (pintype "bidirectional"))
      (node (ref "IC1") (pin "5") (pinfunction "5_5") (pintype "passive"))
    )
    (net (code "49") (name "D24") (class "Default")
      (node (ref "ATMEGA_2560") (pin "D24") (pinfunction "D24_D24") (pintype "bidirectional"))
      (node (ref "CON2A") (pin "5") (pinfunction "5_5") (pintype "bidirectional"))
      (node (ref "JP2") (pin "3") (pinfunction "3_3") (pintype "passive"))
    )
    (net (code "50") (name "D24B") (class "Default")
      (node (ref "CON2B") (pin "5") (pinfunction "5_5") (pintype "bidirectional"))
      (node (ref "IC1") (pin "6") (pinfunction "6_6") (pintype "passive"))
    )
    (net (code "51") (name "D25") (class "Default")
      (node (ref "ATMEGA_2560") (pin "D25") (pinfunction "D25_D25") (pintype "bidirectional"))
      (node (ref "CON2A") (pin "4") (pinfunction "4_4") (pintype "bidirectional"))
      (node (ref "JP2") (pin "4") (pinfunction "4_4") (pintype "passive"))
    )
    (net (code "52") (name "D25B") (class "Default")
      (node (ref "CON2B") (pin "4") (pinfunction "4_4") (pintype "bidirectional"))
      (node (ref "IC1") (pin "7") (pinfunction "7_7") (pintype "passive"))
    )
    (net (code "53") (name "D26") (class "Default")
      (node (ref "ATMEGA_2560") (pin "D26") (pinfunction "D26_D26") (pintype "bidirectional"))
      (node (ref "JP2") (pin "5") (pinfunction "5_5") (pintype "passive"))
      (node (ref "U$2") (pin "RS") (pinfunction "RS_RS") (pintype "bidirectional"))
    )
    (net (code "54") (name "D27") (class "Default")
      (node (ref "ATMEGA_2560") (pin "D27") (pinfunction "D27_D27") (pintype "bidirectional"))
      (node (ref "JP2") (pin "6") (pinfunction "6_6") (pintype "passive"))
      (node (ref "U$2") (pin "EN") (pinfunction "EN_EN") (pintype "bidirectional"))
    )
    (net (code "55") (name "D28") (class "Default")
      (node (ref "ATMEGA_2560") (pin "D28") (pinfunction "D28_D28") (pintype "bidirectional"))
      (node (ref "JP2") (pin "7") (pinfunction "7_7") (pintype "passive"))
      (node (ref "U$2") (pin "D4") (pinfunction "D4_D4") (pintype "bidirectional"))
    )
    (net (code "56") (name "D29") (class "Default")
      (node (ref "ATMEGA_2560") (pin "D29") (pinfunction "D29_D29") (pintype "bidirectional"))
      (node (ref "JP2") (pin "8") (pinfunction "8_8") (pintype "passive"))
      (node (ref "U$2") (pin "D5") (pinfunction "D5_D5") (pintype "bidirectional"))
    )
    (net (code "57") (name "D30") (class "Default")
      (node (ref "ATMEGA_2560") (pin "D30") (pinfunction "D30_D30") (pintype "bidirectional"))
      (node (ref "JP2") (pin "9") (pinfunction "9_9") (pintype "passive"))
      (node (ref "U$2") (pin "D6") (pinfunction "D6_D6") (pintype "bidirectional"))
    )
    (net (code "58") (name "D31") (class "Default")
      (node (ref "ATMEGA_2560") (pin "D31") (pinfunction "D31_D31") (pintype "bidirectional"))
      (node (ref "JP2") (pin "10") (pinfunction "10_10") (pintype "passive"))
      (node (ref "U$2") (pin "D7") (pinfunction "D7_D7") (pintype "bidirectional"))
    )
    (net (code "59") (name "D32") (class "Default")
      (node (ref "ATMEGA_2560") (pin "D32") (pinfunction "D32_D32") (pintype "bidirectional"))
      (node (ref "JP2") (pin "11") (pinfunction "11_11") (pintype "passive"))
      (node (ref "OISO1") (pin "5") (pinfunction "5_5") (pintype "bidirectional"))
      (node (ref "R32") (pin "P$2") (pinfunction "2_P$2") (pintype "passive"))
    )
    (net (code "60") (name "D33") (class "Default")
      (node (ref "ATMEGA_2560") (pin "D33") (pinfunction "D33_D33") (pintype "bidirectional"))
      (node (ref "JP2") (pin "12") (pinfunction "12_12") (pintype "passive"))
      (node (ref "OISO1") (pin "4") (pinfunction "4_4") (pintype "bidirectional"))
      (node (ref "R18") (pin "P$2") (pinfunction "2_P$2") (pintype "passive"))
    )
    (net (code "61") (name "D34") (class "Default")
      (node (ref "ATMEGA_2560") (pin "D34") (pinfunction "D34_D34") (pintype "bidirectional"))
      (node (ref "JP2") (pin "13") (pinfunction "13_13") (pintype "passive"))
      (node (ref "OISO1") (pin "3") (pinfunction "3_3") (pintype "bidirectional"))
      (node (ref "R19") (pin "P$2") (pinfunction "2_P$2") (pintype "passive"))
    )
    (net (code "62") (name "D35") (class "Default")
      (node (ref "ATMEGA_2560") (pin "D35") (pinfunction "D35_D35") (pintype "bidirectional"))
      (node (ref "JP2") (pin "14") (pinfunction "14_14") (pintype "passive"))
      (node (ref "OISO1") (pin "2") (pinfunction "2_2") (pintype "bidirectional"))
      (node (ref "R20") (pin "P$2") (pinfunction "2_P$2") (pintype "passive"))
    )
    (net (code "63") (name "D36") (class "Default")
      (node (ref "ATMEGA_2560") (pin "D36") (pinfunction "D36_D36") (pintype "bidirectional"))
      (node (ref "CON2A") (pin "3") (pinfunction "3_3") (pintype "bidirectional"))
      (node (ref "JP2") (pin "15") (pinfunction "15_15") (pintype "passive"))
    )
    (net (code "64") (name "D36B") (class "Default")
      (node (ref "CON2B") (pin "3") (pinfunction "3_3") (pintype "bidirectional"))
      (node (ref "D1") (pin "A") (pinfunction "A_A") (pintype "passive"))
      (node (ref "R4") (pin "P$2") (pinfunction "2_P$2") (pintype "passive"))
    )
    (net (code "65") (name "D37") (class "Default")
      (node (ref "ATMEGA_2560") (pin "D37") (pinfunction "D37_D37") (pintype "bidirectional"))
      (node (ref "CON2A") (pin "2") (pinfunction "2_2") (pintype "bidirectional"))
      (node (ref "JP2") (pin "16") (pinfunction "16_16") (pintype "passive"))
    )
    (net (code "66") (name "D37B") (class "Default")
      (node (ref "CON2B") (pin "2") (pinfunction "2_2") (pintype "bidirectional"))
      (node (ref "D2") (pin "A") (pinfunction "A_A") (pintype "passive"))
      (node (ref "R10") (pin "P$2") (pinfunction "2_P$2") (pintype "passive"))
    )
    (net (code "67") (name "D38") (class "Default")
      (node (ref "ATMEGA_2560") (pin "D38") (pinfunction "D38_D38") (pintype "bidirectional"))
      (node (ref "CON2A") (pin "1") (pinfunction "1_1") (pintype "bidirectional"))
      (node (ref "JP2") (pin "17") (pinfunction "17_17") (pintype "passive"))
    )
    (net (code "68") (name "D38B") (class "Default")
      (node (ref "CON2B") (pin "1") (pinfunction "1_1") (pintype "bidirectional"))
      (node (ref "D3") (pin "A") (pinfunction "A_A") (pintype "passive"))
      (node (ref "R11") (pin "P$2") (pinfunction "2_P$2") (pintype "passive"))
    )
    (net (code "69") (name "D39") (class "Default")
      (node (ref "ATMEGA_2560") (pin "D39") (pinfunction "D39_D39") (pintype "bidirectional"))
      (node (ref "CON2B1") (pin "2") (pinfunction "2_2") (pintype "bidirectional"))
      (node (ref "JP2") (pin "18") (pinfunction "18_18") (pintype "passive"))
    )
    (net (code "70") (name "D39B") (class "Default")
      (node (ref "CON2B2") (pin "2") (pinfunction "2_2") (pintype "bidirectional"))
      (node (ref "LSA_2") (pin "5") (pinfunction "5_5") (pintype "passive"))
    )
    (net (code "71") (name "D40") (class "Default")
      (node (ref "ATMEGA_2560") (pin "D40") (pinfunction "D40_D40") (pintype "bidirectional"))
      (node (ref "CON1A") (pin "9") (pinfunction "9_9") (pintype "bidirectional"))
      (node (ref "JP2") (pin "19") (pinfunction "19_19") (pintype "passive"))
    )
    (net (code "72") (name "D40B") (class "Default")
      (node (ref "CON1B") (pin "9") (pinfunction "9_9") (pintype "bidirectional"))
      (node (ref "U$6") (pin "INA") (pinfunction "INA_INA") (pintype "bidirectional"))
    )
    (net (code "73") (name "D41") (class "Default")
      (node (ref "ATMEGA_2560") (pin "D41") (pinfunction "D41_D41") (pintype "bidirectional"))
      (node (ref "CON1A") (pin "8") (pinfunction "8_8") (pintype "bidirectional"))
      (node (ref "JP2") (pin "20") (pinfunction "20_20") (pintype "passive"))
    )
    (net (code "74") (name "D41B") (class "Default")
      (node (ref "CON1B") (pin "8") (pinfunction "8_8") (pintype "bidirectional"))
      (node (ref "U$6") (pin "INB") (pinfunction "INB_INB") (pintype "bidirectional"))
    )
    (net (code "75") (name "D42") (class "Default")
      (node (ref "ATMEGA_2560") (pin "D42") (pinfunction "D42_D42") (pintype "bidirectional"))
      (node (ref "CON1A") (pin "6") (pinfunction "6_6") (pintype "bidirectional"))
      (node (ref "JP2") (pin "21") (pinfunction "21_21") (pintype "passive"))
    )
    (net (code "76") (name "D42B") (class "Default")
      (node (ref "CON1B") (pin "6") (pinfunction "6_6") (pintype "bidirectional"))
      (node (ref "U$3") (pin "INA") (pinfunction "INA_INA") (pintype "bidirectional"))
    )
    (net (code "77") (name "D43") (class "Default")
      (node (ref "ATMEGA_2560") (pin "D43") (pinfunction "D43_D43") (pintype "bidirectional"))
      (node (ref "CON1A") (pin "5") (pinfunction "5_5") (pintype "bidirectional"))
      (node (ref "JP2") (pin "22") (pinfunction "22_22") (pintype "passive"))
    )
    (net (code "78") (name "D43B") (class "Default")
      (node (ref "CON1B") (pin "5") (pinfunction "5_5") (pintype "bidirectional"))
      (node (ref "U$3") (pin "INB") (pinfunction "INB_INB") (pintype "bidirectional"))
    )
    (net (code "79") (name "D44") (class "Default")
      (node (ref "ATMEGA_2560") (pin "D44") (pinfunction "D44_D44") (pintype "bidirectional"))
      (node (ref "CON1A") (pin "4") (pinfunction "4_4") (pintype "bidirectional"))
      (node (ref "JP2") (pin "23") (pinfunction "23_23") (pintype "passive"))
    )
    (net (code "80") (name "D44B") (class "Default")
      (node (ref "CON1B") (pin "4") (pinfunction "4_4") (pintype "bidirectional"))
      (node (ref "U$3") (pin "PWM") (pinfunction "PWM_PWM") (pintype "bidirectional"))
    )
    (net (code "81") (name "D45") (class "Default")
      (node (ref "ATMEGA_2560") (pin "D45") (pinfunction "D45_D45") (pintype "bidirectional"))
      (node (ref "CON1A") (pin "7") (pinfunction "7_7") (pintype "bidirectional"))
      (node (ref "JP2") (pin "24") (pinfunction "24_24") (pintype "passive"))
    )
    (net (code "82") (name "D45B") (class "Default")
      (node (ref "CON1B") (pin "7") (pinfunction "7_7") (pintype "bidirectional"))
      (node (ref "U$6") (pin "PWM") (pinfunction "PWM_PWM") (pintype "bidirectional"))
    )
    (net (code "83") (name "D46") (class "Default")
      (node (ref "ATMEGA_2560") (pin "D46") (pinfunction "D46_D46") (pintype "bidirectional"))
      (node (ref "CON1A") (pin "1") (pinfunction "1_1") (pintype "bidirectional"))
      (node (ref "JP2") (pin "25") (pinfunction "25_25") (pintype "passive"))
    )
    (net (code "84") (name "D46B") (class "Default")
      (node (ref "CON1B") (pin "1") (pinfunction "1_1") (pintype "bidirectional"))
      (node (ref "U$9") (pin "PWM") (pinfunction "PWM_PWM") (pintype "bidirectional"))
    )
    (net (code "85") (name "D47") (class "Default")
      (node (ref "ATMEGA_2560") (pin "D47") (pinfunction "D47_D47") (pintype "bidirectional"))
      (node (ref "CON1A") (pin "3") (pinfunction "3_3") (pintype "bidirectional"))
      (node (ref "JP2") (pin "26") (pinfunction "26_26") (pintype "passive"))
    )
    (net (code "86") (name "D47B") (class "Default")
      (node (ref "CON1B") (pin "3") (pinfunction "3_3") (pintype "bidirectional"))
      (node (ref "U$9") (pin "INB") (pinfunction "INB_INB") (pintype "bidirectional"))
    )
    (net (code "87") (name "D48") (class "Default")
      (node (ref "ATMEGA_2560") (pin "D48") (pinfunction "D48_D48") (pintype "bidirectional"))
      (node (ref "CON1A") (pin "2") (pinfunction "2_2") (pintype "bidirectional"))
      (node (ref "JP2") (pin "27") (pinfunction "27_27") (pintype "passive"))
    )
    (net (code "88") (name "D48B") (class "Default")
      (node (ref "CON1B") (pin "2") (pinfunction "2_2") (pintype "bidirectional"))
      (node (ref "U$9") (pin "INA") (pinfunction "INA_INA") (pintype "bidirectional"))
    )
    (net (code "89") (name "D49") (class "Default")
      (node (ref "ATMEGA_2560") (pin "D49") (pinfunction "D49_D49") (pintype "bidirectional"))
      (node (ref "JP2") (pin "28") (pinfunction "28_28") (pintype "passive"))
      (node (ref "U$39") (pin "-") (pinfunction "-_-") (pintype "bidirectional"))
    )
    (net (code "90") (name "D50") (class "Default")
      (node (ref "ATMEGA_2560") (pin "D50") (pinfunction "D50_D50") (pintype "bidirectional"))
    )
    (net (code "91") (name "D51") (class "Default")
      (node (ref "ATMEGA_2560") (pin "D51") (pinfunction "D51_D51") (pintype "bidirectional"))
    )
    (net (code "92") (name "D52") (class "Default")
      (node (ref "ATMEGA_2560") (pin "D52") (pinfunction "D52_D52") (pintype "bidirectional"))
    )
    (net (code "93") (name "D53") (class "Default")
      (node (ref "ATMEGA_2560") (pin "D53") (pinfunction "D53_D53") (pintype "bidirectional"))
    )
    (net (code "94") (name "D_GND") (class "Default")
      (node (ref "ATMEGA_2560") (pin "GND2") (pinfunction "GND2_GND2") (pintype "bidirectional"))
      (node (ref "CON2B1") (pin "1") (pinfunction "1_1") (pintype "bidirectional"))
      (node (ref "ENA") (pin "1") (pinfunction "1_1") (pintype "bidirectional"))
      (node (ref "ENB") (pin "1") (pinfunction "1_1") (pintype "bidirectional"))
      (node (ref "G_P2") (pin "E") (pinfunction "E_E") (pintype "passive"))
      (node (ref "IC10") (pin "11") (pinfunction "EMITTER_2_11") (pintype "bidirectional"))
      (node (ref "IC10") (pin "13") (pinfunction "EMITTER_3_13") (pintype "bidirectional"))
      (node (ref "IC10") (pin "15") (pinfunction "EMITTER_4_15") (pintype "bidirectional"))
      (node (ref "IC10") (pin "9") (pinfunction "EMITTER_1_9") (pintype "bidirectional"))
      (node (ref "IC8") (pin "2") (pinfunction "CATHODE_1_2") (pintype "bidirectional"))
      (node (ref "IC8") (pin "4") (pinfunction "CATHODE_2_4") (pintype "bidirectional"))
      (node (ref "IC8") (pin "6") (pinfunction "CATHODE_3_6") (pintype "bidirectional"))
      (node (ref "IC8") (pin "8") (pinfunction "CATHODE_4_8") (pintype "bidirectional"))
      (node (ref "IC9") (pin "11") (pinfunction "EMITTER_2_11") (pintype "bidirectional"))
      (node (ref "IC9") (pin "13") (pinfunction "EMITTER_3_13") (pintype "bidirectional"))
      (node (ref "IC9") (pin "15") (pinfunction "EMITTER_4_15") (pintype "bidirectional"))
      (node (ref "IC9") (pin "9") (pinfunction "EMITTER_1_9") (pintype "bidirectional"))
      (node (ref "OISO1") (pin "1") (pinfunction "1_1") (pintype "bidirectional"))
      (node (ref "OISO4") (pin "1") (pinfunction "1_1") (pintype "bidirectional"))
      (node (ref "OISO6") (pin "5") (pinfunction "5_5") (pintype "bidirectional"))
      (node (ref "RFID") (pin "3") (pinfunction "3_3") (pintype "bidirectional"))
      (node (ref "SERVO1") (pin "1") (pinfunction "1_1") (pintype "bidirectional"))
      (node (ref "SERVO2") (pin "1") (pinfunction "1_1") (pintype "bidirectional"))
      (node (ref "SERVO3") (pin "1") (pinfunction "1_1") (pintype "bidirectional"))
      (node (ref "SERVO4") (pin "1") (pinfunction "1_1") (pintype "bidirectional"))
      (node (ref "TR17") (pin "1") (pinfunction "E_1") (pintype "passive"))
      (node (ref "TR18") (pin "1") (pinfunction "E_1") (pintype "passive"))
      (node (ref "TR19") (pin "1") (pinfunction "E_1") (pintype "passive"))
      (node (ref "TR20") (pin "1") (pinfunction "E_1") (pintype "passive"))
      (node (ref "TR21") (pin "1") (pinfunction "E_1") (pintype "passive"))
      (node (ref "TR22") (pin "1") (pinfunction "E_1") (pintype "passive"))
      (node (ref "TR23") (pin "1") (pinfunction "E_1") (pintype "passive"))
      (node (ref "TR24") (pin "1") (pinfunction "E_1") (pintype "passive"))
      (node (ref "U$10") (pin "GND") (pinfunction "GND_GND") (pintype "bidirectional"))
      (node (ref "U$11") (pin "GND") (pinfunction "GND_GND") (pintype "bidirectional"))
      (node (ref "U$12") (pin "GND") (pinfunction "GND_GND") (pintype "bidirectional"))
      (node (ref "U$17") (pin "1") (pinfunction "1_1") (pintype "bidirectional"))
      (node (ref "U$2") (pin "GND") (pinfunction "GND_GND") (pintype "bidirectional"))
      (node (ref "U$2") (pin "L-") (pinfunction "L-_L-") (pintype "bidirectional"))
      (node (ref "U$2") (pin "R/W") (pinfunction "R/W_R/W") (pintype "bidirectional"))
      (node (ref "U$24") (pin "GND") (pinfunction "GND_GND") (pintype "bidirectional"))
      (node (ref "U$35") (pin "GND1") (pinfunction "GND1_GND1") (pintype "bidirectional"))
      (node (ref "U$4") (pin "GND2") (pinfunction "GND2_GND2") (pintype "bidirectional"))
      (node (ref "U$42") (pin "7") (pinfunction "7_7") (pintype "bidirectional"))
      (node (ref "U$62") (pin "2") (pinfunction "2_2") (pintype "bidirectional"))
    )
    (net (code "95") (name "D_GNDB") (class "Default")
      (node (ref "CON2B2") (pin "1") (pinfunction "1_1") (pintype "bidirectional"))
      (node (ref "C_GND") (pin "1") (pinfunction "1_1") (pintype "bidirectional"))
    )
    (net (code "96") (name "GND") (class "Default")
      (node (ref "BALANCE") (pin "1") (pinfunction "1_1") (pintype "bidirectional"))
      (node (ref "BALANCE1") (pin "1") (pinfunction "1_1") (pintype "bidirectional"))
      (node (ref "BAT1") (pin "2") (pinfunction "2_2") (pintype "bidirectional"))
      (node (ref "C1") (pin "1") (pinfunction "1_1") (pintype "passive"))
      (node (ref "C3") (pin "1") (pinfunction "1_1") (pintype "passive"))
      (node (ref "C4") (pin "1") (pinfunction "1_1") (pintype "passive"))
      (node (ref "CEL1RC") (pin "P$1") (pinfunction "1_P$1") (pintype "passive"))
      (node (ref "CEL2RC") (pin "P$1") (pinfunction "1_P$1") (pintype "passive"))
      (node (ref "CEL3RC") (pin "P$1") (pinfunction "1_P$1") (pintype "passive"))
      (node (ref "CON2B2") (pin "6") (pinfunction "6_6") (pintype "bidirectional"))
      (node (ref "CS") (pin "2") (pinfunction "2_2") (pintype "bidirectional"))
      (node (ref "C_GND") (pin "2") (pinfunction "2_2") (pintype "bidirectional"))
      (node (ref "D1") (pin "K") (pinfunction "C_K") (pintype "passive"))
      (node (ref "D2") (pin "K") (pinfunction "C_K") (pintype "passive"))
      (node (ref "D3") (pin "K") (pinfunction "C_K") (pintype "passive"))
      (node (ref "IC1") (pin "8") (pinfunction "8_8") (pintype "passive"))
      (node (ref "IC2") (pin "4") (pinfunction "4_4") (pintype "passive"))
      (node (ref "LSA_2") (pin "10") (pinfunction "10_10") (pintype "passive"))
      (node (ref "PROX1") (pin "1") (pinfunction "1_1") (pintype "bidirectional"))
      (node (ref "PROX2") (pin "1") (pinfunction "1_1") (pintype "bidirectional"))
      (node (ref "PROX3") (pin "1") (pinfunction "1_1") (pintype "bidirectional"))
      (node (ref "R34") (pin "P$1") (pinfunction "1_P$1") (pintype "passive"))
      (node (ref "R36") (pin "P$1") (pinfunction "1_P$1") (pintype "passive"))
      (node (ref "R38") (pin "P$1") (pinfunction "1_P$1") (pintype "passive"))
      (node (ref "R5") (pin "P$1") (pinfunction "1_P$1") (pintype "passive"))
      (node (ref "R6") (pin "P$1") (pinfunction "1_P$1") (pintype "passive"))
      (node (ref "R7") (pin "P$1") (pinfunction "1_P$1") (pintype "passive"))
      (node (ref "SHARP1") (pin "2") (pinfunction "2_2") (pintype "bidirectional"))
      (node (ref "SHARP2") (pin "2") (pinfunction "2_2") (pintype "bidirectional"))
      (node (ref "SHARP3") (pin "2") (pinfunction "2_2") (pintype "bidirectional"))
      (node (ref "U$13") (pin "IN-") (pinfunction "IN-_IN-") (pintype "bidirectional"))
      (node (ref "U$13") (pin "OUT-") (pinfunction "OUT-_OUT-") (pintype "bidirectional"))
      (node (ref "U$18") (pin "VSS") (pinfunction "VSS_VSS") (pintype "bidirectional"))
      (node (ref "U$19") (pin "VSS") (pinfunction "VSS_VSS") (pintype "bidirectional"))
      (node (ref "U$20") (pin "VSS") (pinfunction "VSS_VSS") (pintype "bidirectional"))
      (node (ref "U$23") (pin "1") (pinfunction "1_1") (pintype "bidirectional"))
      (node (ref "U$25") (pin "1") (pinfunction "1_1") (pintype "bidirectional"))
      (node (ref "U$26") (pin "1") (pinfunction "1_1") (pintype "bidirectional"))
      (node (ref "U$27") (pin "1") (pinfunction "1_1") (pintype "bidirectional"))
      (node (ref "U$29") (pin "2") (pinfunction "2_2") (pintype "bidirectional"))
      (node (ref "U$3") (pin "GND") (pinfunction "GND_GND") (pintype "bidirectional"))
      (node (ref "U$3") (pin "IN-") (pinfunction "IN-_IN-") (pintype "bidirectional"))
      (node (ref "U$33") (pin "2") (pinfunction "2_2") (pintype "bidirectional"))
      (node (ref "U$34") (pin "1") (pinfunction "1_1") (pintype "bidirectional"))
      (node (ref "U$36") (pin "2") (pinfunction "2_2") (pintype "bidirectional"))
      (node (ref "U$37") (pin "1") (pinfunction "1_1") (pintype "bidirectional"))
      (node (ref "U$38") (pin "1") (pinfunction "1_1") (pintype "bidirectional"))
      (node (ref "U$44") (pin "2") (pinfunction "GND_2") (pintype "bidirectional"))
      (node (ref "U$46") (pin "2") (pinfunction "GND_2") (pintype "bidirectional"))
      (node (ref "U$47") (pin "2") (pinfunction "GND_2") (pintype "bidirectional"))
      (node (ref "U$51") (pin "1") (pinfunction "1_1") (pintype "bidirectional"))
      (node (ref "U$6") (pin "GND") (pinfunction "GND_GND") (pintype "bidirectional"))
      (node (ref "U$6") (pin "IN-") (pinfunction "IN-_IN-") (pintype "bidirectional"))
      (node (ref "U$7") (pin "IN-") (pinfunction "IN-_IN-") (pintype "bidirectional"))
      (node (ref "U$7") (pin "OUT-") (pinfunction "OUT-_OUT-") (pintype "bidirectional"))
      (node (ref "U$8") (pin "IN-") (pinfunction "IN-_IN-") (pintype "bidirectional"))
      (node (ref "U$8") (pin "OUT-") (pinfunction "OUT-_OUT-") (pintype "bidirectional"))
      (node (ref "U$9") (pin "GND") (pinfunction "GND_GND") (pintype "bidirectional"))
      (node (ref "U$9") (pin "IN-") (pinfunction "IN-_IN-") (pintype "bidirectional"))
      (node (ref "V-P") (pin "1") (pinfunction "1_1") (pintype "bidirectional"))
    )
    (net (code "97") (name "GNDA") (class "Default")
      (node (ref "ATMEGA_2560") (pin "GND1") (pinfunction "GND1_GND1") (pintype "bidirectional"))
      (node (ref "CON2B1") (pin "6") (pinfunction "6_6") (pintype "bidirectional"))
      (node (ref "IRL1") (pin "P$1") (pinfunction "1_P$1") (pintype "passive"))
      (node (ref "IRL2") (pin "P$1") (pinfunction "1_P$1") (pintype "passive"))
      (node (ref "IRL3") (pin "P$1") (pinfunction "1_P$1") (pintype "passive"))
      (node (ref "MEGA_RST") (pin "3") (pinfunction "2_3") (pintype "passive"))
      (node (ref "M_RST") (pin "3") (pinfunction "2_3") (pintype "passive"))
      (node (ref "N_RST") (pin "3") (pinfunction "2_3") (pintype "passive"))
      (node (ref "U$12") (pin "GND3") (pinfunction "GND3_GND3") (pintype "bidirectional"))
      (node (ref "U$35") (pin "GND") (pinfunction "GND_GND") (pintype "bidirectional"))
      (node (ref "U$4") (pin "GND3") (pinfunction "GND3_GND3") (pintype "bidirectional"))
      (node (ref "U$62") (pin "1") (pinfunction "1_1") (pintype "bidirectional"))
    )
    (net (code "98") (name "GPIO2") (class "Default")
      (node (ref "RASPI_PORT1") (pin "3") (pinfunction "3_3") (pintype "passive"))
      (node (ref "RASPI_PORT2") (pin "37") (pinfunction "37_37") (pintype "passive"))
    )
    (net (code "99") (name "GPIO3") (class "Default")
      (node (ref "RASPI_PORT1") (pin "5") (pinfunction "5_5") (pintype "passive"))
      (node (ref "RASPI_PORT2") (pin "35") (pinfunction "35_35") (pintype "passive"))
    )
    (net (code "100") (name "GPIO4") (class "Default")
      (node (ref "RASPI_PORT1") (pin "7") (pinfunction "7_7") (pintype "passive"))
      (node (ref "RASPI_PORT2") (pin "33") (pinfunction "33_33") (pintype "passive"))
    )
    (net (code "101") (name "GPIO5") (class "Default")
      (node (ref "RASPI_PORT1") (pin "29") (pinfunction "29_29") (pintype "passive"))
      (node (ref "RASPI_PORT2") (pin "11") (pinfunction "11_11") (pintype "passive"))
    )
    (net (code "102") (name "GPIO6") (class "Default")
      (node (ref "OISO3") (pin "5") (pinfunction "5_5") (pintype "bidirectional"))
      (node (ref "R21") (pin "P$2") (pinfunction "2_P$2") (pintype "passive"))
      (node (ref "RASPI_PORT1") (pin "31") (pinfunction "31_31") (pintype "passive"))
      (node (ref "RASPI_PORT2") (pin "9") (pinfunction "9_9") (pintype "passive"))
    )
    (net (code "103") (name "GPIO7") (class "Default")
      (node (ref "RASPI_PORT1") (pin "26") (pinfunction "26_26") (pintype "passive"))
      (node (ref "RASPI_PORT2") (pin "16") (pinfunction "16_16") (pintype "passive"))
    )
    (net (code "104") (name "GPIO8") (class "Default")
      (node (ref "RASPI_PORT1") (pin "24") (pinfunction "24_24") (pintype "passive"))
      (node (ref "RASPI_PORT2") (pin "18") (pinfunction "18_18") (pintype "passive"))
    )
    (net (code "105") (name "GPIO9") (class "Default")
      (node (ref "RASPI_PORT1") (pin "21") (pinfunction "21_21") (pintype "passive"))
      (node (ref "RASPI_PORT2") (pin "19") (pinfunction "19_19") (pintype "passive"))
    )
    (net (code "106") (name "GPIO10") (class "Default")
      (node (ref "RASPI_PORT1") (pin "19") (pinfunction "19_19") (pintype "passive"))
      (node (ref "RASPI_PORT2") (pin "21") (pinfunction "21_21") (pintype "passive"))
    )
    (net (code "107") (name "GPIO11") (class "Default")
      (node (ref "RASPI_PORT1") (pin "23") (pinfunction "23_23") (pintype "passive"))
      (node (ref "RASPI_PORT2") (pin "17") (pinfunction "17_17") (pintype "passive"))
    )
    (net (code "108") (name "GPIO12") (class "Default")
      (node (ref "OISO3") (pin "4") (pinfunction "4_4") (pintype "bidirectional"))
      (node (ref "R22") (pin "P$2") (pinfunction "2_P$2") (pintype "passive"))
      (node (ref "RASPI_PORT1") (pin "32") (pinfunction "32_32") (pintype "passive"))
      (node (ref "RASPI_PORT2") (pin "10") (pinfunction "10_10") (pintype "passive"))
    )
    (net (code "109") (name "GPIO13") (class "Default")
      (node (ref "OISO3") (pin "3") (pinfunction "3_3") (pintype "bidirectional"))
      (node (ref "R23") (pin "P$2") (pinfunction "2_P$2") (pintype "passive"))
      (node (ref "RASPI_PORT1") (pin "33") (pinfunction "33_33") (pintype "passive"))
      (node (ref "RASPI_PORT2") (pin "7") (pinfunction "7_7") (pintype "passive"))
    )
    (net (code "110") (name "GPIO14") (class "Default")
      (node (ref "RASPI_PORT1") (pin "8") (pinfunction "8_8") (pintype "passive"))
      (node (ref "RASPI_PORT2") (pin "34") (pinfunction "34_34") (pintype "passive"))
      (node (ref "SW1") (pin "8") (pinfunction "8_8") (pintype "passive"))
    )
    (net (code "111") (name "GPIO15") (class "Default")
      (node (ref "RASPI_PORT1") (pin "10") (pinfunction "10_10") (pintype "passive"))
      (node (ref "RASPI_PORT2") (pin "32") (pinfunction "32_32") (pintype "passive"))
      (node (ref "SW1") (pin "7") (pinfunction "7_7") (pintype "passive"))
    )
    (net (code "112") (name "GPIO16") (class "Default")
      (node (ref "OISO5") (pin "5") (pinfunction "5_5") (pintype "bidirectional"))
      (node (ref "R25") (pin "P$2") (pinfunction "2_P$2") (pintype "passive"))
      (node (ref "RASPI_PORT1") (pin "36") (pinfunction "36_36") (pintype "passive"))
      (node (ref "RASPI_PORT2") (pin "6") (pinfunction "6_6") (pintype "passive"))
    )
    (net (code "113") (name "GPIO17") (class "Default")
      (node (ref "RASPI_PORT1") (pin "11") (pinfunction "11_11") (pintype "passive"))
      (node (ref "RASPI_PORT2") (pin "29") (pinfunction "29_29") (pintype "passive"))
    )
    (net (code "114") (name "GPIO18") (class "Default")
      (node (ref "RASPI_PORT1") (pin "12") (pinfunction "12_12") (pintype "passive"))
      (node (ref "RASPI_PORT2") (pin "30") (pinfunction "30_30") (pintype "passive"))
    )
    (net (code "115") (name "GPIO19") (class "Default")
      (node (ref "OISO3") (pin "2") (pinfunction "2_2") (pintype "bidirectional"))
      (node (ref "R24") (pin "P$2") (pinfunction "2_P$2") (pintype "passive"))
      (node (ref "RASPI_PORT1") (pin "35") (pinfunction "35_35") (pintype "passive"))
      (node (ref "RASPI_PORT2") (pin "5") (pinfunction "5_5") (pintype "passive"))
    )
    (net (code "116") (name "GPIO20") (class "Default")
      (node (ref "OISO5") (pin "3") (pinfunction "3_3") (pintype "bidirectional"))
      (node (ref "R27") (pin "P$2") (pinfunction "2_P$2") (pintype "passive"))
      (node (ref "RASPI_PORT1") (pin "38") (pinfunction "38_38") (pintype "passive"))
      (node (ref "RASPI_PORT2") (pin "4") (pinfunction "4_4") (pintype "passive"))
    )
    (net (code "117") (name "GPIO21") (class "Default")
      (node (ref "OISO5") (pin "2") (pinfunction "2_2") (pintype "bidirectional"))
      (node (ref "R28") (pin "P$2") (pinfunction "2_P$2") (pintype "passive"))
      (node (ref "RASPI_PORT1") (pin "40") (pinfunction "40_40") (pintype "passive"))
      (node (ref "RASPI_PORT2") (pin "2") (pinfunction "2_2") (pintype "passive"))
    )
    (net (code "118") (name "GPIO22") (class "Default")
      (node (ref "10K") (pin "7") (pinfunction "7_7") (pintype "passive"))
      (node (ref "OISO2") (pin "4") (pinfunction "4_4") (pintype "bidirectional"))
      (node (ref "RASPI_PORT1") (pin "15") (pinfunction "15_15") (pintype "passive"))
      (node (ref "RASPI_PORT2") (pin "25") (pinfunction "25_25") (pintype "passive"))
      (node (ref "TR14") (pin "3") (pinfunction "C_3") (pintype "passive"))
    )
    (net (code "119") (name "GPIO23") (class "Default")
      (node (ref "10K") (pin "5") (pinfunction "5_5") (pintype "passive"))
      (node (ref "OISO2") (pin "3") (pinfunction "3_3") (pintype "bidirectional"))
      (node (ref "RASPI_PORT1") (pin "16") (pinfunction "16_16") (pintype "passive"))
      (node (ref "RASPI_PORT2") (pin "26") (pinfunction "26_26") (pintype "passive"))
      (node (ref "TR15") (pin "3") (pinfunction "C_3") (pintype "passive"))
    )
    (net (code "120") (name "GPIO24") (class "Default")
      (node (ref "10K") (pin "3") (pinfunction "3_3") (pintype "passive"))
      (node (ref "OISO2") (pin "2") (pinfunction "2_2") (pintype "bidirectional"))
      (node (ref "RASPI_PORT1") (pin "18") (pinfunction "18_18") (pintype "passive"))
      (node (ref "RASPI_PORT2") (pin "24") (pinfunction "24_24") (pintype "passive"))
      (node (ref "TR16") (pin "3") (pinfunction "C_3") (pintype "passive"))
    )
    (net (code "121") (name "GPIO25") (class "Default")
      (node (ref "RASPI_PORT1") (pin "22") (pinfunction "22_22") (pintype "passive"))
      (node (ref "RASPI_PORT2") (pin "20") (pinfunction "20_20") (pintype "passive"))
    )
    (net (code "122") (name "GPIO26") (class "Default")
      (node (ref "OISO5") (pin "4") (pinfunction "4_4") (pintype "bidirectional"))
      (node (ref "R26") (pin "P$2") (pinfunction "2_P$2") (pintype "passive"))
      (node (ref "RASPI_PORT1") (pin "37") (pinfunction "37_37") (pintype "passive"))
      (node (ref "RASPI_PORT2") (pin "3") (pinfunction "3_3") (pintype "passive"))
    )
    (net (code "123") (name "GPIO27") (class "Default")
      (node (ref "10K") (pin "9") (pinfunction "9_9") (pintype "passive"))
      (node (ref "BC547") (pin "3") (pinfunction "C_3") (pintype "passive"))
      (node (ref "OISO2") (pin "5") (pinfunction "5_5") (pintype "bidirectional"))
      (node (ref "RASPI_PORT1") (pin "13") (pinfunction "13_13") (pintype "passive"))
      (node (ref "RASPI_PORT2") (pin "27") (pinfunction "27_27") (pintype "passive"))
    )
    (net (code "124") (name "I-P") (class "Default")
      (node (ref "IC2") (pin "6") (pinfunction "6_6") (pintype "passive"))
      (node (ref "IC2") (pin "7") (pinfunction "7_7") (pintype "passive"))
      (node (ref "V-P") (pin "2") (pinfunction "2_2") (pintype "bidirectional"))
    )
    (net (code "125") (name "ID_SC") (class "Default")
      (node (ref "RASPI_PORT1") (pin "28") (pinfunction "28_28") (pintype "passive"))
      (node (ref "RASPI_PORT2") (pin "14") (pinfunction "14_14") (pintype "passive"))
    )
    (net (code "126") (name "ID_SD") (class "Default")
      (node (ref "RASPI_PORT1") (pin "27") (pinfunction "27_27") (pintype "passive"))
      (node (ref "RASPI_PORT2") (pin "13") (pinfunction "13_13") (pintype "passive"))
    )
    (net (code "127") (name "IOREF") (class "Default")
      (node (ref "ATMEGA_2560") (pin "IOREF") (pinfunction "IOREF_IOREF") (pintype "bidirectional"))
      (node (ref "U$12") (pin "VREF") (pinfunction "VREF_VREF") (pintype "bidirectional"))
    )
    (net (code "128") (name "M1A") (class "Default")
      (node (ref "M1") (pin "2") (pinfunction "2_2") (pintype "bidirectional"))
      (node (ref "U$3") (pin "OA") (pinfunction "OUTA_OA") (pintype "bidirectional"))
    )
    (net (code "129") (name "M1B") (class "Default")
      (node (ref "M1") (pin "1") (pinfunction "1_1") (pintype "bidirectional"))
      (node (ref "U$3") (pin "OB") (pinfunction "OUTB_OB") (pintype "bidirectional"))
    )
    (net (code "130") (name "M2A") (class "Default")
      (node (ref "M2") (pin "1") (pinfunction "1_1") (pintype "bidirectional"))
      (node (ref "U$6") (pin "OA") (pinfunction "OUTA_OA") (pintype "bidirectional"))
    )
    (net (code "131") (name "M2B") (class "Default")
      (node (ref "M2") (pin "2") (pinfunction "2_2") (pintype "bidirectional"))
      (node (ref "U$6") (pin "OB") (pinfunction "OUTB_OB") (pintype "bidirectional"))
    )
    (net (code "132") (name "M3A") (class "Default")
      (node (ref "M3") (pin "1") (pinfunction "1_1") (pintype "bidirectional"))
      (node (ref "U$9") (pin "OA") (pinfunction "OUTA_OA") (pintype "bidirectional"))
    )
    (net (code "133") (name "M3B") (class "Default")
      (node (ref "M3") (pin "2") (pinfunction "2_2") (pintype "bidirectional"))
      (node (ref "U$9") (pin "OB") (pinfunction "OUTB_OB") (pintype "bidirectional"))
    )
    (net (code "134") (name "MISO") (class "Default")
      (node (ref "ATMEGA_2560") (pin "MISO") (pinfunction "MISO_MISO") (pintype "bidirectional"))
      (node (ref "U$12") (pin "MISO") (pinfunction "MI_MISO") (pintype "bidirectional"))
    )
    (net (code "135") (name "MOSI") (class "Default")
      (node (ref "ATMEGA_2560") (pin "MOSI") (pinfunction "MOSI_MOSI") (pintype "bidirectional"))
      (node (ref "U$12") (pin "MOSI") (pinfunction "MO_MOSI") (pintype "bidirectional"))
    )
    (net (code "136") (name "M_3V3") (class "Default")
      (node (ref "RFID") (pin "1") (pinfunction "1_1") (pintype "bidirectional"))
      (node (ref "U$4") (pin "3V3") (pinfunction "3V3_3V3") (pintype "bidirectional"))
    )
    (net (code "137") (name "M_A0") (class "Default")
      (node (ref "ATMEGA_2560") (pin "A15") (pinfunction "A15_A15") (pintype "bidirectional"))
      (node (ref "JP1") (pin "1") (pinfunction "1_1") (pintype "passive"))
      (node (ref "RFID4") (pin "1") (pinfunction "1_1") (pintype "bidirectional"))
      (node (ref "U$4") (pin "A0") (pinfunction "A0_A0") (pintype "bidirectional"))
    )
    (net (code "138") (name "M_D0") (class "Default")
      (node (ref "ATMEGA_2560") (pin "D3") (pinfunction "D3_D3") (pintype "bidirectional"))
      (node (ref "RFID1") (pin "4") (pinfunction "4_4") (pintype "bidirectional"))
      (node (ref "U$4") (pin "D0") (pinfunction "D0_D0") (pintype "bidirectional"))
      (node (ref "U$45") (pin "1") (pinfunction "1_1") (pintype "bidirectional"))
    )
    (net (code "139") (name "M_D1") (class "Default")
      (node (ref "RFID") (pin "2") (pinfunction "2_2") (pintype "bidirectional"))
      (node (ref "U$4") (pin "D1") (pinfunction "D1_D1") (pintype "bidirectional"))
      (node (ref "U$45") (pin "2") (pinfunction "2_2") (pintype "bidirectional"))
    )
    (net (code "140") (name "M_D2") (class "Default")
      (node (ref "RFID") (pin "8") (pinfunction "8_8") (pintype "bidirectional"))
      (node (ref "U$4") (pin "D2") (pinfunction "D2_D2") (pintype "bidirectional"))
      (node (ref "U$45") (pin "3") (pinfunction "3_3") (pintype "bidirectional"))
    )
    (net (code "141") (name "M_D3") (class "Default")
      (node (ref "ATMEGA_2560") (pin "A12") (pinfunction "A12_A12") (pintype "bidirectional"))
      (node (ref "RFID4") (pin "4") (pinfunction "4_4") (pintype "bidirectional"))
      (node (ref "U$4") (pin "D3") (pinfunction "D3_D3") (pintype "bidirectional"))
      (node (ref "U$45") (pin "4") (pinfunction "4_4") (pintype "bidirectional"))
    )
    (net (code "142") (name "M_D4") (class "Default")
      (node (ref "ATMEGA_2560") (pin "A13") (pinfunction "A13_A13") (pintype "bidirectional"))
      (node (ref "RFID4") (pin "3") (pinfunction "3_3") (pintype "bidirectional"))
      (node (ref "U$4") (pin "D4") (pinfunction "D4_D4") (pintype "bidirectional"))
      (node (ref "U$45") (pin "5") (pinfunction "5_5") (pintype "bidirectional"))
    )
    (net (code "143") (name "M_D5") (class "Default")
      (node (ref "RFID") (pin "7") (pinfunction "7_7") (pintype "bidirectional"))
      (node (ref "U$4") (pin "D5") (pinfunction "D5_D5") (pintype "bidirectional"))
      (node (ref "U$49") (pin "1") (pinfunction "1_1") (pintype "bidirectional"))
    )
    (net (code "144") (name "M_D6") (class "Default")
      (node (ref "RFID") (pin "5") (pinfunction "5_5") (pintype "bidirectional"))
      (node (ref "U$4") (pin "D6") (pinfunction "D6_D6") (pintype "bidirectional"))
      (node (ref "U$49") (pin "2") (pinfunction "2_2") (pintype "bidirectional"))
    )
    (net (code "145") (name "M_D7") (class "Default")
      (node (ref "RFID") (pin "6") (pinfunction "6_6") (pintype "bidirectional"))
      (node (ref "U$4") (pin "D7") (pinfunction "D7_D7") (pintype "bidirectional"))
      (node (ref "U$49") (pin "3") (pinfunction "3_3") (pintype "bidirectional"))
    )
    (net (code "146") (name "M_D8") (class "Default")
      (node (ref "ATMEGA_2560") (pin "A14") (pinfunction "A14_A14") (pintype "bidirectional"))
      (node (ref "RFID4") (pin "2") (pinfunction "2_2") (pintype "bidirectional"))
      (node (ref "U$4") (pin "D8") (pinfunction "D8_D8") (pintype "bidirectional"))
      (node (ref "U$49") (pin "4") (pinfunction "4_4") (pintype "bidirectional"))
    )
    (net (code "147") (name "M_EN") (class "Default")
      (node (ref "U$4") (pin "EN") (pinfunction "EN_EN") (pintype "bidirectional"))
    )
    (net (code "148") (name "M_RST") (class "Default")
      (node (ref "M_RST") (pin "1") (pinfunction "1_1") (pintype "passive"))
      (node (ref "U$30") (pin "1") (pinfunction "1_1") (pintype "bidirectional"))
      (node (ref "U$4") (pin "RST") (pinfunction "RST_RST") (pintype "bidirectional"))
    )
    (net (code "149") (name "M_RX") (class "Default")
      (node (ref "SW1") (pin "9") (pinfunction "9_9") (pintype "passive"))
      (node (ref "U$4") (pin "RX") (pinfunction "RX_RX") (pintype "bidirectional"))
    )
    (net (code "150") (name "M_TX") (class "Default")
      (node (ref "SW1") (pin "10") (pinfunction "10_10") (pintype "passive"))
      (node (ref "U$4") (pin "TX") (pinfunction "TX_TX") (pintype "bidirectional"))
    )
    (net (code "151") (name "N_5V") (class "Default")
      (node (ref "NANO") (pin "2") (pinfunction "2_2") (pintype "bidirectional"))
      (node (ref "U$28") (pin "+") (pinfunction "+_+") (pintype "bidirectional"))
      (node (ref "U$35") (pin "5V") (pinfunction "5V_5V") (pintype "bidirectional"))
    )
    (net (code "152") (name "N_A0") (class "Default")
      (node (ref "CON2B1") (pin "3") (pinfunction "3_3") (pintype "bidirectional"))
      (node (ref "U$35") (pin "A0") (pinfunction "A0_A0") (pintype "bidirectional"))
      (node (ref "U$43") (pin "1") (pinfunction "1_1") (pintype "bidirectional"))
    )
    (net (code "153") (name "N_A0B") (class "Default")
      (node (ref "CON2B2") (pin "3") (pinfunction "3_3") (pintype "bidirectional"))
      (node (ref "ENA1") (pin "4") (pinfunction "4_4") (pintype "bidirectional"))
      (node (ref "U$1") (pin "2") (pinfunction "2_2") (pintype "bidirectional"))
    )
    (net (code "154") (name "N_A1") (class "Default")
      (node (ref "CON2B1") (pin "4") (pinfunction "4_4") (pintype "bidirectional"))
      (node (ref "U$35") (pin "A1") (pinfunction "A1_A1") (pintype "bidirectional"))
      (node (ref "U$43") (pin "2") (pinfunction "2_2") (pintype "bidirectional"))
    )
    (net (code "155") (name "N_A1B") (class "Default")
      (node (ref "CON2B2") (pin "4") (pinfunction "4_4") (pintype "bidirectional"))
      (node (ref "ENA1") (pin "3") (pinfunction "3_3") (pintype "bidirectional"))
      (node (ref "U$40") (pin "2") (pinfunction "2_2") (pintype "bidirectional"))
    )
    (net (code "156") (name "N_A2") (class "Default")
      (node (ref "CON2B1") (pin "5") (pinfunction "5_5") (pintype "bidirectional"))
      (node (ref "U$35") (pin "A2") (pinfunction "A2_A2") (pintype "bidirectional"))
      (node (ref "U$43") (pin "3") (pinfunction "3_3") (pintype "bidirectional"))
    )
    (net (code "157") (name "N_A2B") (class "Default")
      (node (ref "CON2B2") (pin "5") (pinfunction "5_5") (pintype "bidirectional"))
      (node (ref "ENA1") (pin "2") (pinfunction "2_2") (pintype "bidirectional"))
      (node (ref "U$41") (pin "2") (pinfunction "2_2") (pintype "bidirectional"))
    )
    (net (code "158") (name "N_A3") (class "Default")
      (node (ref "IH3") (pin "K") (pinfunction "C_K") (pintype "passive"))
      (node (ref "IL3") (pin "A") (pinfunction "A_A") (pintype "passive"))
      (node (ref "U$35") (pin "A3") (pinfunction "A3_A3") (pintype "bidirectional"))
      (node (ref "U$43") (pin "4") (pinfunction "4_4") (pintype "bidirectional"))
    )
    (net (code "159") (name "N_A4") (class "Default")
      (node (ref "U$24") (pin "SDA") (pinfunction "SDA_SDA") (pintype "bidirectional"))
      (node (ref "U$35") (pin "A4") (pinfunction "A4_A4") (pintype "bidirectional"))
      (node (ref "U$43") (pin "5") (pinfunction "5_5") (pintype "bidirectional"))
    )
    (net (code "160") (name "N_A5") (class "Default")
      (node (ref "U$24") (pin "SCL") (pinfunction "SCL_SCL") (pintype "bidirectional"))
      (node (ref "U$35") (pin "A5") (pinfunction "A5_A5") (pintype "bidirectional"))
      (node (ref "U$43") (pin "6") (pinfunction "6_6") (pintype "bidirectional"))
    )
    (net (code "161") (name "N_A6") (class "Default")
      (node (ref "IH2") (pin "K") (pinfunction "C_K") (pintype "passive"))
      (node (ref "IL2") (pin "A") (pinfunction "A_A") (pintype "passive"))
      (node (ref "U$35") (pin "A6") (pinfunction "A6_A6") (pintype "bidirectional"))
      (node (ref "U$43") (pin "7") (pinfunction "7_7") (pintype "bidirectional"))
    )
    (net (code "162") (name "N_A7") (class "Default")
      (node (ref "IH1") (pin "K") (pinfunction "C_K") (pintype "passive"))
      (node (ref "IL1") (pin "A") (pinfunction "A_A") (pintype "passive"))
      (node (ref "U$35") (pin "A7") (pinfunction "A7_A7") (pintype "bidirectional"))
      (node (ref "U$43") (pin "8") (pinfunction "8_8") (pintype "bidirectional"))
    )
    (net (code "163") (name "N_D2") (class "Default")
      (node (ref "ENA") (pin "4") (pinfunction "4_4") (pintype "bidirectional"))
      (node (ref "ENC_PULL") (pin "2") (pinfunction "2_2") (pintype "passive"))
      (node (ref "U$35") (pin "D2") (pinfunction "D2_D2") (pintype "bidirectional"))
    )
    (net (code "164") (name "N_D3") (class "Default")
      (node (ref "ENB") (pin "4") (pinfunction "4_4") (pintype "bidirectional"))
      (node (ref "ENC_PULL") (pin "4") (pinfunction "4_4") (pintype "passive"))
      (node (ref "U$35") (pin "D3") (pinfunction "D3_D3") (pintype "bidirectional"))
    )
    (net (code "165") (name "N_D4") (class "Default")
      (node (ref "ENA") (pin "3") (pinfunction "3_3") (pintype "bidirectional"))
      (node (ref "ENC_PULL") (pin "3") (pinfunction "3_3") (pintype "passive"))
      (node (ref "U$35") (pin "D4") (pinfunction "D4_D4") (pintype "bidirectional"))
    )
    (net (code "166") (name "N_D5") (class "Default")
      (node (ref "ENB") (pin "3") (pinfunction "3_3") (pintype "bidirectional"))
      (node (ref "ENC_PULL") (pin "5") (pinfunction "5_5") (pintype "passive"))
      (node (ref "U$35") (pin "D5") (pinfunction "D5_D5") (pintype "bidirectional"))
    )
    (net (code "167") (name "N_D6") (class "Default")
      (node (ref "ATMEGA_2560") (pin "D2") (pinfunction "D2_D2") (pintype "bidirectional"))
      (node (ref "RFID1") (pin "3") (pinfunction "3_3") (pintype "bidirectional"))
      (node (ref "U$35") (pin "D6") (pinfunction "D6_D6") (pintype "bidirectional"))
      (node (ref "U$48") (pin "1") (pinfunction "1_1") (pintype "bidirectional"))
    )
    (net (code "168") (name "N_D7") (class "Default")
      (node (ref "ATMEGA_2560") (pin "D4") (pinfunction "D4_D4") (pintype "bidirectional"))
      (node (ref "RFID1") (pin "5") (pinfunction "5_5") (pintype "bidirectional"))
      (node (ref "U$35") (pin "D7") (pinfunction "D7_D7") (pintype "bidirectional"))
      (node (ref "U$48") (pin "2") (pinfunction "2_2") (pintype "bidirectional"))
    )
    (net (code "169") (name "N_D8") (class "Default")
      (node (ref "U$35") (pin "D8") (pinfunction "D8_D8") (pintype "bidirectional"))
      (node (ref "U$48") (pin "3") (pinfunction "3_3") (pintype "bidirectional"))
    )
    (net (code "170") (name "N_D9") (class "Default")
      (node (ref "CON2A") (pin "10") (pinfunction "10_10") (pintype "bidirectional"))
      (node (ref "U$35") (pin "D9") (pinfunction "D9_D9") (pintype "bidirectional"))
      (node (ref "U$48") (pin "4") (pinfunction "4_4") (pintype "bidirectional"))
    )
    (net (code "171") (name "N_D9B") (class "Default")
      (node (ref "CON2B") (pin "10") (pinfunction "10_10") (pintype "bidirectional"))
      (node (ref "IC1") (pin "1") (pinfunction "1_1") (pintype "passive"))
    )
    (net (code "172") (name "N_D10") (class "Default")
      (node (ref "CON2A") (pin "9") (pinfunction "9_9") (pintype "bidirectional"))
      (node (ref "U$35") (pin "D10") (pinfunction "D10_D10") (pintype "bidirectional"))
      (node (ref "U$48") (pin "5") (pinfunction "5_5") (pintype "bidirectional"))
    )
    (net (code "173") (name "N_D10B") (class "Default")
      (node (ref "CON2B") (pin "9") (pinfunction "9_9") (pintype "bidirectional"))
      (node (ref "IC1") (pin "2") (pinfunction "2_2") (pintype "passive"))
    )
    (net (code "174") (name "N_D11") (class "Default")
      (node (ref "CON2A") (pin "8") (pinfunction "8_8") (pintype "bidirectional"))
      (node (ref "U$35") (pin "D11") (pinfunction "D11_D11") (pintype "bidirectional"))
      (node (ref "U$48") (pin "6") (pinfunction "6_6") (pintype "bidirectional"))
    )
    (net (code "175") (name "N_D11B") (class "Default")
      (node (ref "CON2B") (pin "8") (pinfunction "8_8") (pintype "bidirectional"))
      (node (ref "IC1") (pin "3") (pinfunction "3_3") (pintype "passive"))
    )
    (net (code "176") (name "N_D12") (class "Default")
      (node (ref "U$35") (pin "D12") (pinfunction "D12_D12") (pintype "bidirectional"))
      (node (ref "U$48") (pin "7") (pinfunction "7_7") (pintype "bidirectional"))
    )
    (net (code "177") (name "N_D13") (class "Default")
      (node (ref "U$28") (pin "-") (pinfunction "-_-") (pintype "bidirectional"))
      (node (ref "U$35") (pin "D13") (pinfunction "D13_D13") (pintype "bidirectional"))
    )
    (net (code "178") (name "N_RST") (class "Default")
      (node (ref "N_RST") (pin "1") (pinfunction "1_1") (pintype "passive"))
      (node (ref "U$30") (pin "2") (pinfunction "2_2") (pintype "bidirectional"))
      (node (ref "U$35") (pin "RST") (pinfunction "RST_RST") (pintype "bidirectional"))
    )
    (net (code "179") (name "N_RX") (class "Default")
      (node (ref "BLUETOOTH") (pin "1") (pinfunction "1_1") (pintype "passive"))
      (node (ref "N-M") (pin "1") (pinfunction "1_1") (pintype "passive"))
      (node (ref "U$35") (pin "RX") (pinfunction "RX_RX") (pintype "bidirectional"))
    )
    (net (code "180") (name "N_TX") (class "Default")
      (node (ref "BLUETOOTH") (pin "2") (pinfunction "2_2") (pintype "passive"))
      (node (ref "N-M") (pin "2") (pinfunction "2_2") (pintype "passive"))
      (node (ref "U$35") (pin "TX") (pinfunction "TX_TX") (pintype "bidirectional"))
    )
    (net (code "181") (name "Net-(BAT_SUPP-Pad1)") (class "Default")
      (node (ref "BAT_SUPP") (pin "1") (pinfunction "1_1") (pintype "bidirectional"))
      (node (ref "EM_SW") (pin "2") (pinfunction "2_2") (pintype "bidirectional"))
    )
    (net (code "182") (name "Net-(BC547-B)") (class "Default")
      (node (ref "10K") (pin "8") (pinfunction "8_8") (pintype "passive"))
      (node (ref "BC547") (pin "2") (pinfunction "B_2") (pintype "passive"))
      (node (ref "IC8") (pin "16") (pinfunction "COLLECTOR_4_16") (pintype "bidirectional"))
    )
    (net (code "183") (name "Net-(C1-Pad2)") (class "Default")
      (node (ref "C1") (pin "2") (pinfunction "2_2") (pintype "passive"))
      (node (ref "U$14") (pin "IP") (pinfunction "IP_IP") (pintype "bidirectional"))
      (node (ref "U$34") (pin "2") (pinfunction "2_2") (pintype "bidirectional"))
      (node (ref "U$7") (pin "OUT+") (pinfunction "OUT+_OUT+") (pintype "bidirectional"))
    )
    (net (code "184") (name "Net-(C2-Pad1)") (class "Default")
      (node (ref "C2") (pin "1") (pinfunction "1_1") (pintype "passive"))
      (node (ref "JP3") (pin "1") (pinfunction "1_1") (pintype "passive"))
    )
    (net (code "185") (name "Net-(C3-Pad2)") (class "Default")
      (node (ref "C3") (pin "2") (pinfunction "2_2") (pintype "passive"))
      (node (ref "U$15") (pin "IP") (pinfunction "IP_IP") (pintype "bidirectional"))
      (node (ref "U$37") (pin "2") (pinfunction "2_2") (pintype "bidirectional"))
      (node (ref "U$8") (pin "OUT+") (pinfunction "OUT+_OUT+") (pintype "bidirectional"))
    )
    (net (code "186") (name "Net-(C4-Pad2)") (class "Default")
      (node (ref "C4") (pin "2") (pinfunction "2_2") (pintype "passive"))
      (node (ref "U$13") (pin "OUT+") (pinfunction "OUT+_OUT+") (pintype "bidirectional"))
      (node (ref "U$16") (pin "IP") (pinfunction "IP_IP") (pintype "bidirectional"))
      (node (ref "U$38") (pin "2") (pinfunction "2_2") (pintype "bidirectional"))
    )
    (net (code "187") (name "Net-(CEL1CC-C)") (class "Default")
      (node (ref "CEL1CC") (pin "K") (pinfunction "C_K") (pintype "passive"))
      (node (ref "CEL1RC") (pin "P$2") (pinfunction "2_P$2") (pintype "passive"))
    )
    (net (code "188") (name "Net-(CEL1RO-2)") (class "Default")
      (node (ref "CEL1CO") (pin "A") (pinfunction "A_A") (pintype "passive"))
      (node (ref "CEL1RO") (pin "P$2") (pinfunction "2_P$2") (pintype "passive"))
    )
    (net (code "189") (name "Net-(CEL2CC-C)") (class "Default")
      (node (ref "CEL2CC") (pin "K") (pinfunction "C_K") (pintype "passive"))
      (node (ref "CEL2RC") (pin "P$2") (pinfunction "2_P$2") (pintype "passive"))
    )
    (net (code "190") (name "Net-(CEL2RO-2)") (class "Default")
      (node (ref "CEL2CO") (pin "A") (pinfunction "A_A") (pintype "passive"))
      (node (ref "CEL2RO") (pin "P$2") (pinfunction "2_P$2") (pintype "passive"))
    )
    (net (code "191") (name "Net-(CEL3CC-C)") (class "Default")
      (node (ref "CEL3CC") (pin "K") (pinfunction "C_K") (pintype "passive"))
      (node (ref "CEL3RC") (pin "P$2") (pinfunction "2_P$2") (pintype "passive"))
    )
    (net (code "192") (name "Net-(CEL3RO-2)") (class "Default")
      (node (ref "CEL3CO") (pin "A") (pinfunction "A_A") (pintype "passive"))
      (node (ref "CEL3RO") (pin "P$2") (pinfunction "2_P$2") (pintype "passive"))
    )
    (net (code "193") (name "Net-(EM_SW-Pad1)") (class "Default")
      (node (ref "EM_SW") (pin "1") (pinfunction "1_1") (pintype "bidirectional"))
      (node (ref "U$33") (pin "1") (pinfunction "1_1") (pintype "bidirectional"))
    )
    (net (code "194") (name "Net-(FUSE-PadOUT)") (class "Default")
      (node (ref "FUSE") (pin "OUT") (pinfunction "OUT_OUT") (pintype "bidirectional"))
      (node (ref "U$32") (pin "IP") (pinfunction "IP_IP") (pintype "bidirectional"))
    )
    (net (code "195") (name "Net-(G_P2-PadS)") (class "Default")
      (node (ref "G_P2") (pin "S") (pinfunction "S_S") (pintype "passive"))
      (node (ref "U$2") (pin "VCON") (pinfunction "VCON_VCON") (pintype "bidirectional"))
    )
    (net (code "196") (name "Net-(IC8-ANODE_1)") (class "Default")
      (node (ref "IC8") (pin "1") (pinfunction "ANODE_1_1") (pintype "bidirectional"))
      (node (ref "R32") (pin "P$1") (pinfunction "1_P$1") (pintype "passive"))
    )
    (net (code "197") (name "Net-(IC8-ANODE_2)") (class "Default")
      (node (ref "IC8") (pin "3") (pinfunction "ANODE_2_3") (pintype "bidirectional"))
      (node (ref "R18") (pin "P$1") (pinfunction "1_P$1") (pintype "passive"))
    )
    (net (code "198") (name "Net-(IC8-ANODE_3)") (class "Default")
      (node (ref "IC8") (pin "5") (pinfunction "ANODE_3_5") (pintype "bidirectional"))
      (node (ref "R19") (pin "P$1") (pinfunction "1_P$1") (pintype "passive"))
    )
    (net (code "199") (name "Net-(IC8-ANODE_4)") (class "Default")
      (node (ref "IC8") (pin "7") (pinfunction "ANODE_4_7") (pintype "bidirectional"))
      (node (ref "R20") (pin "P$1") (pinfunction "1_P$1") (pintype "passive"))
    )
    (net (code "200") (name "Net-(IC8-COLLECTOR_1)") (class "Default")
      (node (ref "10K") (pin "2") (pinfunction "2_2") (pintype "passive"))
      (node (ref "IC8") (pin "10") (pinfunction "COLLECTOR_1_10") (pintype "bidirectional"))
      (node (ref "TR16") (pin "2") (pinfunction "B_2") (pintype "passive"))
    )
    (net (code "201") (name "Net-(IC8-COLLECTOR_2)") (class "Default")
      (node (ref "10K") (pin "4") (pinfunction "4_4") (pintype "passive"))
      (node (ref "IC8") (pin "12") (pinfunction "COLLECTOR_2_12") (pintype "bidirectional"))
      (node (ref "TR15") (pin "2") (pinfunction "B_2") (pintype "passive"))
    )
    (net (code "202") (name "Net-(IC8-COLLECTOR_3)") (class "Default")
      (node (ref "10K") (pin "6") (pinfunction "6_6") (pintype "passive"))
      (node (ref "IC8") (pin "14") (pinfunction "COLLECTOR_3_14") (pintype "bidirectional"))
      (node (ref "TR14") (pin "2") (pinfunction "B_2") (pintype "passive"))
    )
    (net (code "203") (name "Net-(IC9-ANODE_1)") (class "Default")
      (node (ref "IC9") (pin "1") (pinfunction "ANODE_1_1") (pintype "bidirectional"))
      (node (ref "R21") (pin "P$1") (pinfunction "1_P$1") (pintype "passive"))
    )
    (net (code "204") (name "Net-(IC9-ANODE_2)") (class "Default")
      (node (ref "IC9") (pin "3") (pinfunction "ANODE_2_3") (pintype "bidirectional"))
      (node (ref "R22") (pin "P$1") (pinfunction "1_P$1") (pintype "passive"))
    )
    (net (code "205") (name "Net-(IC9-ANODE_3)") (class "Default")
      (node (ref "IC9") (pin "5") (pinfunction "ANODE_3_5") (pintype "bidirectional"))
      (node (ref "R23") (pin "P$1") (pinfunction "1_P$1") (pintype "passive"))
    )
    (net (code "206") (name "Net-(IC9-ANODE_4)") (class "Default")
      (node (ref "IC9") (pin "7") (pinfunction "ANODE_4_7") (pintype "bidirectional"))
      (node (ref "R24") (pin "P$1") (pinfunction "1_P$1") (pintype "passive"))
    )
    (net (code "207") (name "Net-(IC9-COLLECTOR_1)") (class "Default")
      (node (ref "IC9") (pin "10") (pinfunction "COLLECTOR_1_10") (pintype "bidirectional"))
      (node (ref "RN6") (pin "2") (pinfunction "2_2") (pintype "passive"))
      (node (ref "TR20") (pin "2") (pinfunction "B_2") (pintype "passive"))
    )
    (net (code "208") (name "Net-(IC9-COLLECTOR_2)") (class "Default")
      (node (ref "IC9") (pin "12") (pinfunction "COLLECTOR_2_12") (pintype "bidirectional"))
      (node (ref "RN6") (pin "4") (pinfunction "4_4") (pintype "passive"))
      (node (ref "TR19") (pin "2") (pinfunction "B_2") (pintype "passive"))
    )
    (net (code "209") (name "Net-(IC9-COLLECTOR_3)") (class "Default")
      (node (ref "IC9") (pin "14") (pinfunction "COLLECTOR_3_14") (pintype "bidirectional"))
      (node (ref "RN6") (pin "6") (pinfunction "6_6") (pintype "passive"))
      (node (ref "TR18") (pin "2") (pinfunction "B_2") (pintype "passive"))
    )
    (net (code "210") (name "Net-(IC9-COLLECTOR_4)") (class "Default")
      (node (ref "IC9") (pin "16") (pinfunction "COLLECTOR_4_16") (pintype "bidirectional"))
      (node (ref "RN6") (pin "8") (pinfunction "8_8") (pintype "passive"))
      (node (ref "TR17") (pin "2") (pinfunction "B_2") (pintype "passive"))
    )
    (net (code "211") (name "Net-(IC10-ANODE_1)") (class "Default")
      (node (ref "IC10") (pin "1") (pinfunction "ANODE_1_1") (pintype "bidirectional"))
      (node (ref "R25") (pin "P$1") (pinfunction "1_P$1") (pintype "passive"))
    )
    (net (code "212") (name "Net-(IC10-ANODE_2)") (class "Default")
      (node (ref "IC10") (pin "3") (pinfunction "ANODE_2_3") (pintype "bidirectional"))
      (node (ref "R26") (pin "P$1") (pinfunction "1_P$1") (pintype "passive"))
    )
    (net (code "213") (name "Net-(IC10-ANODE_3)") (class "Default")
      (node (ref "IC10") (pin "5") (pinfunction "ANODE_3_5") (pintype "bidirectional"))
      (node (ref "R27") (pin "P$1") (pinfunction "1_P$1") (pintype "passive"))
    )
    (net (code "214") (name "Net-(IC10-ANODE_4)") (class "Default")
      (node (ref "IC10") (pin "7") (pinfunction "ANODE_4_7") (pintype "bidirectional"))
      (node (ref "R28") (pin "P$1") (pinfunction "1_P$1") (pintype "passive"))
    )
    (net (code "215") (name "Net-(IC10-COLLECTOR_1)") (class "Default")
      (node (ref "IC10") (pin "10") (pinfunction "COLLECTOR_1_10") (pintype "bidirectional"))
      (node (ref "RN7") (pin "2") (pinfunction "2_2") (pintype "passive"))
      (node (ref "TR24") (pin "2") (pinfunction "B_2") (pintype "passive"))
    )
    (net (code "216") (name "Net-(IC10-COLLECTOR_2)") (class "Default")
      (node (ref "IC10") (pin "12") (pinfunction "COLLECTOR_2_12") (pintype "bidirectional"))
      (node (ref "RN7") (pin "4") (pinfunction "4_4") (pintype "passive"))
      (node (ref "TR23") (pin "2") (pinfunction "B_2") (pintype "passive"))
    )
    (net (code "217") (name "Net-(IC10-COLLECTOR_3)") (class "Default")
      (node (ref "IC10") (pin "14") (pinfunction "COLLECTOR_3_14") (pintype "bidirectional"))
      (node (ref "RN7") (pin "6") (pinfunction "6_6") (pintype "passive"))
      (node (ref "TR22") (pin "2") (pinfunction "B_2") (pintype "passive"))
    )
    (net (code "218") (name "Net-(IC10-COLLECTOR_4)") (class "Default")
      (node (ref "IC10") (pin "16") (pinfunction "COLLECTOR_4_16") (pintype "bidirectional"))
      (node (ref "RN7") (pin "8") (pinfunction "8_8") (pintype "passive"))
      (node (ref "TR21") (pin "2") (pinfunction "B_2") (pintype "passive"))
    )
    (net (code "219") (name "Net-(IL1-C)") (class "Default")
      (node (ref "IL1") (pin "K") (pinfunction "C_K") (pintype "passive"))
      (node (ref "IRL1") (pin "P$2") (pinfunction "2_P$2") (pintype "passive"))
    )
    (net (code "220") (name "Net-(IL2-C)") (class "Default")
      (node (ref "IL2") (pin "K") (pinfunction "C_K") (pintype "passive"))
      (node (ref "IRL2") (pin "P$2") (pinfunction "2_P$2") (pintype "passive"))
    )
    (net (code "221") (name "Net-(IL3-C)") (class "Default")
      (node (ref "IL3") (pin "K") (pinfunction "C_K") (pintype "passive"))
      (node (ref "IRL3") (pin "P$2") (pinfunction "2_P$2") (pintype "passive"))
    )
    (net (code "222") (name "Net-(IRH1-2)") (class "Default")
      (node (ref "IH1") (pin "A") (pinfunction "A_A") (pintype "passive"))
      (node (ref "IRH1") (pin "P$2") (pinfunction "2_P$2") (pintype "passive"))
    )
    (net (code "223") (name "Net-(IRH2-2)") (class "Default")
      (node (ref "IH2") (pin "A") (pinfunction "A_A") (pintype "passive"))
      (node (ref "IRH2") (pin "P$2") (pinfunction "2_P$2") (pintype "passive"))
    )
    (net (code "224") (name "Net-(IRH3-2)") (class "Default")
      (node (ref "IH3") (pin "A") (pinfunction "A_A") (pintype "passive"))
      (node (ref "IRH3") (pin "P$2") (pinfunction "2_P$2") (pintype "passive"))
    )
    (net (code "225") (name "Net-(L1-PadA)") (class "Default")
      (node (ref "L1") (pin "A") (pinfunction "A_A") (pintype "passive"))
      (node (ref "RN1") (pin "2") (pinfunction "2_2") (pintype "passive"))
    )
    (net (code "226") (name "Net-(L2-PadA)") (class "Default")
      (node (ref "L2") (pin "A") (pinfunction "A_A") (pintype "passive"))
      (node (ref "RN1") (pin "3") (pinfunction "3_3") (pintype "passive"))
    )
    (net (code "227") (name "Net-(L3-PadA)") (class "Default")
      (node (ref "L3") (pin "A") (pinfunction "A_A") (pintype "passive"))
      (node (ref "RN1") (pin "4") (pinfunction "4_4") (pintype "passive"))
    )
    (net (code "228") (name "Net-(L4-PadA)") (class "Default")
      (node (ref "L4") (pin "A") (pinfunction "A_A") (pintype "passive"))
      (node (ref "RN1") (pin "5") (pinfunction "5_5") (pintype "passive"))
    )
    (net (code "229") (name "Net-(L5-PadA)") (class "Default")
      (node (ref "L5") (pin "A") (pinfunction "A_A") (pintype "passive"))
      (node (ref "RN1") (pin "6") (pinfunction "6_6") (pintype "passive"))
    )
    (net (code "230") (name "Net-(L6-PadA)") (class "Default")
      (node (ref "L6") (pin "A") (pinfunction "A_A") (pintype "passive"))
      (node (ref "RN1") (pin "7") (pinfunction "7_7") (pintype "passive"))
    )
    (net (code "231") (name "Net-(L7-PadA)") (class "Default")
      (node (ref "L7") (pin "A") (pinfunction "A_A") (pintype "passive"))
      (node (ref "RN1") (pin "8") (pinfunction "8_8") (pintype "passive"))
    )
    (net (code "232") (name "Net-(R2-2)") (class "Default")
      (node (ref "R2") (pin "P$2") (pinfunction "2_P$2") (pintype "passive"))
      (node (ref "R34") (pin "P$2") (pinfunction "2_P$2") (pintype "passive"))
      (node (ref "U$1") (pin "1") (pinfunction "1_1") (pintype "bidirectional"))
    )
    (net (code "233") (name "Net-(R4-1)") (class "Default")
      (node (ref "R4") (pin "P$1") (pinfunction "1_P$1") (pintype "passive"))
      (node (ref "U$44") (pin "3") (pinfunction "VO_3") (pintype "bidirectional"))
    )
    (net (code "234") (name "Net-(R5-2)") (class "Default")
      (node (ref "R5") (pin "P$2") (pinfunction "2_P$2") (pintype "passive"))
      (node (ref "U$20") (pin "PROG") (pinfunction "PROG_PROG") (pintype "bidirectional"))
    )
    (net (code "235") (name "Net-(R6-2)") (class "Default")
      (node (ref "R6") (pin "P$2") (pinfunction "2_P$2") (pintype "passive"))
      (node (ref "U$19") (pin "PROG") (pinfunction "PROG_PROG") (pintype "bidirectional"))
    )
    (net (code "236") (name "Net-(R7-2)") (class "Default")
      (node (ref "R7") (pin "P$2") (pinfunction "2_P$2") (pintype "passive"))
      (node (ref "U$18") (pin "PROG") (pinfunction "PROG_PROG") (pintype "bidirectional"))
    )
    (net (code "237") (name "Net-(R10-1)") (class "Default")
      (node (ref "R10") (pin "P$1") (pinfunction "1_P$1") (pintype "passive"))
      (node (ref "U$46") (pin "3") (pinfunction "VO_3") (pintype "bidirectional"))
    )
    (net (code "238") (name "Net-(R11-1)") (class "Default")
      (node (ref "R11") (pin "P$1") (pinfunction "1_P$1") (pintype "passive"))
      (node (ref "U$47") (pin "3") (pinfunction "VO_3") (pintype "bidirectional"))
    )
    (net (code "239") (name "Net-(R17-2)") (class "Default")
      (node (ref "R17") (pin "P$2") (pinfunction "2_P$2") (pintype "passive"))
      (node (ref "U$2") (pin "L+") (pinfunction "L+_L+") (pintype "bidirectional"))
    )
    (net (code "240") (name "Net-(R35-2)") (class "Default")
      (node (ref "R35") (pin "P$2") (pinfunction "2_P$2") (pintype "passive"))
      (node (ref "R36") (pin "P$2") (pinfunction "2_P$2") (pintype "passive"))
      (node (ref "U$40") (pin "1") (pinfunction "1_1") (pintype "bidirectional"))
    )
    (net (code "241") (name "Net-(R37-2)") (class "Default")
      (node (ref "R37") (pin "P$2") (pinfunction "2_P$2") (pintype "passive"))
      (node (ref "R38") (pin "P$2") (pinfunction "2_P$2") (pintype "passive"))
      (node (ref "U$41") (pin "1") (pinfunction "1_1") (pintype "bidirectional"))
    )
    (net (code "242") (name "Net-(U$3-Pad5V)") (class "Default")
      (node (ref "U$3") (pin "5V") (pinfunction "5V_5V") (pintype "bidirectional"))
      (node (ref "U$3") (pin "EN") (pinfunction "EN_EN") (pintype "bidirectional"))
    )
    (net (code "243") (name "Net-(U$6-Pad5V)") (class "Default")
      (node (ref "U$6") (pin "5V") (pinfunction "5V_5V") (pintype "bidirectional"))
      (node (ref "U$6") (pin "EN") (pinfunction "EN_EN") (pintype "bidirectional"))
    )
    (net (code "244") (name "Net-(U$9-Pad5V)") (class "Default")
      (node (ref "U$9") (pin "5V") (pinfunction "5V_5V") (pintype "bidirectional"))
      (node (ref "U$9") (pin "EN") (pinfunction "EN_EN") (pintype "bidirectional"))
    )
    (net (code "245") (name "Net-(U$15-PadO1)") (class "Default")
      (node (ref "U$15") (pin "O1") (pinfunction "O1_O1") (pintype "bidirectional"))
      (node (ref "V-P") (pin "3") (pinfunction "3_3") (pintype "bidirectional"))
    )
    (net (code "246") (name "Net-(U$44-VIN)") (class "Default")
      (node (ref "PROX1") (pin "2") (pinfunction "2_2") (pintype "bidirectional"))
      (node (ref "U$44") (pin "1") (pinfunction "VIN_1") (pintype "bidirectional"))
    )
    (net (code "247") (name "Net-(U$46-VIN)") (class "Default")
      (node (ref "PROX2") (pin "2") (pinfunction "2_2") (pintype "bidirectional"))
      (node (ref "U$46") (pin "1") (pinfunction "VIN_1") (pintype "bidirectional"))
    )
    (net (code "248") (name "Net-(U$47-VIN)") (class "Default")
      (node (ref "PROX3") (pin "2") (pinfunction "2_2") (pintype "bidirectional"))
      (node (ref "U$47") (pin "1") (pinfunction "VIN_1") (pintype "bidirectional"))
    )
    (net (code "249") (name "POS_1") (class "Default")
      (node (ref "IC2") (pin "5") (pinfunction "5_5") (pintype "passive"))
      (node (ref "PPR_R1") (pin "P$1") (pinfunction "1_P$1") (pintype "passive"))
      (node (ref "U$29") (pin "1") (pinfunction "1_1") (pintype "bidirectional"))
    )
    (net (code "250") (name "RESET") (class "Default")
      (node (ref "C2") (pin "2") (pinfunction "2_2") (pintype "passive"))
      (node (ref "CEL2RO1") (pin "P$1") (pinfunction "1_P$1") (pintype "passive"))
      (node (ref "IC3") (pin "1") (pinfunction "1_1") (pintype "passive"))
      (node (ref "MEGA_RST1") (pin "1") (pinfunction "1_1") (pintype "passive"))
    )
    (net (code "251") (name "RO1") (class "Default")
      (node (ref "REL1") (pin "OUT_1") (pinfunction "OUT_1_OUT_1") (pintype "bidirectional"))
      (node (ref "U$18") (pin "VDD") (pinfunction "VDD_VDD") (pintype "bidirectional"))
      (node (ref "U$25") (pin "2") (pinfunction "2_2") (pintype "bidirectional"))
    )
    (net (code "252") (name "RO2") (class "Default")
      (node (ref "REL2") (pin "OUT_1") (pinfunction "OUT_1_OUT_1") (pintype "bidirectional"))
      (node (ref "U$19") (pin "VDD") (pinfunction "VDD_VDD") (pintype "bidirectional"))
      (node (ref "U$26") (pin "2") (pinfunction "2_2") (pintype "bidirectional"))
    )
    (net (code "253") (name "RO3") (class "Default")
      (node (ref "REL3") (pin "OUT_1") (pinfunction "OUT_1_OUT_1") (pintype "bidirectional"))
      (node (ref "U$20") (pin "VDD") (pinfunction "VDD_VDD") (pintype "bidirectional"))
      (node (ref "U$27") (pin "2") (pinfunction "2_2") (pintype "bidirectional"))
    )
    (net (code "254") (name "RST") (class "Default")
      (node (ref "ATMEGA_2560") (pin "RST") (pinfunction "RST_RST") (pintype "bidirectional"))
      (node (ref "MEGA_RST") (pin "1") (pinfunction "1_1") (pintype "passive"))
      (node (ref "U$12") (pin "RST1") (pinfunction "RST1_RST1") (pintype "bidirectional"))
      (node (ref "U$30") (pin "C") (pinfunction "C_C") (pintype "bidirectional"))
    )
    (net (code "255") (name "RST1") (class "Default")
      (node (ref "ATMEGA_2560") (pin "RST1") (pinfunction "RST1_RST1") (pintype "bidirectional"))
      (node (ref "U$12") (pin "RST") (pinfunction "RST_RST") (pintype "bidirectional"))
    )
    (net (code "256") (name "RX0") (class "Default")
      (node (ref "ATMEGA_2560") (pin "RX0") (pinfunction "RX0_RX0") (pintype "bidirectional"))
      (node (ref "RFID1") (pin "1") (pinfunction "1_1") (pintype "bidirectional"))
      (node (ref "U$12") (pin "RX0") (pinfunction "RX_RX0") (pintype "bidirectional"))
    )
    (net (code "257") (name "RX1") (class "Default")
      (node (ref "ATMEGA_2560") (pin "RX1") (pinfunction "RX1_RX1") (pintype "bidirectional"))
      (node (ref "N-M") (pin "3") (pinfunction "3_3") (pintype "passive"))
      (node (ref "RFID2") (pin "3") (pinfunction "3_3") (pintype "bidirectional"))
      (node (ref "SW1") (pin "1") (pinfunction "1_1") (pintype "passive"))
    )
    (net (code "258") (name "RX2") (class "Default")
      (node (ref "ATMEGA_2560") (pin "RX2") (pinfunction "RX2_RX2") (pintype "bidirectional"))
      (node (ref "RFID2") (pin "5") (pinfunction "5_5") (pintype "bidirectional"))
      (node (ref "SW1") (pin "3") (pinfunction "3_3") (pintype "passive"))
    )
    (net (code "259") (name "RX3") (class "Default")
      (node (ref "ATMEGA_2560") (pin "RX3") (pinfunction "RX3_RX3") (pintype "bidirectional"))
      (node (ref "RFID2") (pin "7") (pinfunction "7_7") (pintype "bidirectional"))
      (node (ref "SW1") (pin "5") (pinfunction "5_5") (pintype "passive"))
    )
    (net (code "260") (name "RXD") (class "Default")
      (node (ref "IC3") (pin "2") (pinfunction "2_2") (pintype "passive"))
      (node (ref "JP3") (pin "3") (pinfunction "3_3") (pintype "passive"))
      (node (ref "U$52") (pin "10") (pinfunction "10_10") (pintype "bidirectional"))
    )
    (net (code "261") (name "R_3V3") (class "Default")
      (node (ref "10K") (pin "1") (pinfunction "1_1") (pintype "passive"))
      (node (ref "RASPI_PORT1") (pin "1") (pinfunction "1_1") (pintype "passive"))
      (node (ref "RASPI_PORT2") (pin "39") (pinfunction "39_39") (pintype "passive"))
    )
    (net (code "262") (name "R_3V31") (class "Default")
      (node (ref "RASPI_PORT1") (pin "17") (pinfunction "17_17") (pintype "passive"))
      (node (ref "RASPI_PORT2") (pin "23") (pinfunction "23_23") (pintype "passive"))
    )
    (net (code "263") (name "R_5V") (class "Default")
      (node (ref "RASPI_PORT1") (pin "2") (pinfunction "2_2") (pintype "passive"))
      (node (ref "RASPI_PORT2") (pin "40") (pinfunction "40_40") (pintype "passive"))
    )
    (net (code "264") (name "R_5V1") (class "Default")
      (node (ref "RASPI_PORT1") (pin "4") (pinfunction "4_4") (pintype "passive"))
      (node (ref "RASPI_PORT2") (pin "38") (pinfunction "38_38") (pintype "passive"))
    )
    (net (code "265") (name "R_GND") (class "Default")
      (node (ref "BC547") (pin "1") (pinfunction "E_1") (pintype "passive"))
      (node (ref "IC10") (pin "2") (pinfunction "CATHODE_1_2") (pintype "bidirectional"))
      (node (ref "IC10") (pin "4") (pinfunction "CATHODE_2_4") (pintype "bidirectional"))
      (node (ref "IC10") (pin "6") (pinfunction "CATHODE_3_6") (pintype "bidirectional"))
      (node (ref "IC10") (pin "8") (pinfunction "CATHODE_4_8") (pintype "bidirectional"))
      (node (ref "IC8") (pin "11") (pinfunction "EMITTER_2_11") (pintype "bidirectional"))
      (node (ref "IC8") (pin "13") (pinfunction "EMITTER_3_13") (pintype "bidirectional"))
      (node (ref "IC8") (pin "15") (pinfunction "EMITTER_4_15") (pintype "bidirectional"))
      (node (ref "IC8") (pin "9") (pinfunction "EMITTER_1_9") (pintype "bidirectional"))
      (node (ref "IC9") (pin "2") (pinfunction "CATHODE_1_2") (pintype "bidirectional"))
      (node (ref "IC9") (pin "4") (pinfunction "CATHODE_2_4") (pintype "bidirectional"))
      (node (ref "IC9") (pin "6") (pinfunction "CATHODE_3_6") (pintype "bidirectional"))
      (node (ref "IC9") (pin "8") (pinfunction "CATHODE_4_8") (pintype "bidirectional"))
      (node (ref "OISO2") (pin "1") (pinfunction "1_1") (pintype "bidirectional"))
      (node (ref "OISO3") (pin "1") (pinfunction "1_1") (pintype "bidirectional"))
      (node (ref "OISO5") (pin "1") (pinfunction "1_1") (pintype "bidirectional"))
      (node (ref "RASPI_PORT1") (pin "9") (pinfunction "9_9") (pintype "passive"))
      (node (ref "RASPI_PORT2") (pin "31") (pinfunction "31_31") (pintype "passive"))
      (node (ref "TR14") (pin "1") (pinfunction "E_1") (pintype "passive"))
      (node (ref "TR15") (pin "1") (pinfunction "E_1") (pintype "passive"))
      (node (ref "TR16") (pin "1") (pinfunction "E_1") (pintype "passive"))
      (node (ref "U$17") (pin "2") (pinfunction "2_2") (pintype "bidirectional"))
    )
    (net (code "266") (name "R_GND1") (class "Default")
      (node (ref "RASPI_PORT1") (pin "25") (pinfunction "25_25") (pintype "passive"))
      (node (ref "RASPI_PORT2") (pin "15") (pinfunction "15_15") (pintype "passive"))
    )
    (net (code "267") (name "R_GND2") (class "Default")
      (node (ref "RASPI_PORT1") (pin "39") (pinfunction "39_39") (pintype "passive"))
      (node (ref "RASPI_PORT2") (pin "1") (pinfunction "1_1") (pintype "passive"))
    )
    (net (code "268") (name "R_GND3") (class "Default")
      (node (ref "RASPI_PORT1") (pin "34") (pinfunction "34_34") (pintype "passive"))
      (node (ref "RASPI_PORT2") (pin "8") (pinfunction "8_8") (pintype "passive"))
    )
    (net (code "269") (name "R_GND4") (class "Default")
      (node (ref "RASPI_PORT1") (pin "30") (pinfunction "30_30") (pintype "passive"))
      (node (ref "RASPI_PORT2") (pin "12") (pinfunction "12_12") (pintype "passive"))
    )
    (net (code "270") (name "R_GND5") (class "Default")
      (node (ref "RASPI_PORT1") (pin "20") (pinfunction "20_20") (pintype "passive"))
      (node (ref "RASPI_PORT2") (pin "22") (pinfunction "22_22") (pintype "passive"))
    )
    (net (code "271") (name "R_GND6") (class "Default")
      (node (ref "RASPI_PORT1") (pin "14") (pinfunction "14_14") (pintype "passive"))
      (node (ref "RASPI_PORT2") (pin "28") (pinfunction "28_28") (pintype "passive"))
    )
    (net (code "272") (name "R_GND7") (class "Default")
      (node (ref "RASPI_PORT1") (pin "6") (pinfunction "6_6") (pintype "passive"))
      (node (ref "RASPI_PORT2") (pin "36") (pinfunction "36_36") (pintype "passive"))
    )
    (net (code "273") (name "SCK") (class "Default")
      (node (ref "ATMEGA_2560") (pin "SCK") (pinfunction "SCK_SCK") (pintype "bidirectional"))
      (node (ref "U$12") (pin "SCK") (pinfunction "SC_SCK") (pintype "bidirectional"))
    )
    (net (code "274") (name "SCL") (class "Default")
      (node (ref "ATMEGA_2560") (pin "SCL") (pinfunction "SCL_SCL") (pintype "bidirectional"))
      (node (ref "RFID2") (pin "1") (pinfunction "1_1") (pintype "bidirectional"))
      (node (ref "U$10") (pin "SCL") (pinfunction "SCL_SCL") (pintype "bidirectional"))
    )
    (net (code "275") (name "SCLU") (class "Default")
      (node (ref "ATMEGA_2560") (pin "SCLU") (pinfunction "SCLU_SCLU") (pintype "bidirectional"))
      (node (ref "U$12") (pin "SCL") (pinfunction "SCL_SCL") (pintype "bidirectional"))
    )
    (net (code "276") (name "SDA") (class "Default")
      (node (ref "ATMEGA_2560") (pin "SDA") (pinfunction "SDA_SDA") (pintype "bidirectional"))
      (node (ref "RFID2") (pin "2") (pinfunction "2_2") (pintype "bidirectional"))
      (node (ref "U$10") (pin "SDA") (pinfunction "SDA_SDA") (pintype "bidirectional"))
    )
    (net (code "277") (name "SDAU") (class "Default")
      (node (ref "ATMEGA_2560") (pin "SDAU") (pinfunction "SDAU_SDAU") (pintype "bidirectional"))
      (node (ref "U$12") (pin "SDA") (pinfunction "SDA_SDA") (pintype "bidirectional"))
    )
    (net (code "278") (name "STAT_1") (class "Default")
      (node (ref "CEL1CC") (pin "A") (pinfunction "A_A") (pintype "passive"))
      (node (ref "CEL1CO") (pin "K") (pinfunction "C_K") (pintype "passive"))
      (node (ref "U$18") (pin "STAT") (pinfunction "STAT_STAT") (pintype "bidirectional"))
    )
    (net (code "279") (name "STAT_2") (class "Default")
      (node (ref "CEL2CC") (pin "A") (pinfunction "A_A") (pintype "passive"))
      (node (ref "CEL2CO") (pin "K") (pinfunction "C_K") (pintype "passive"))
      (node (ref "U$19") (pin "STAT") (pinfunction "STAT_STAT") (pintype "bidirectional"))
    )
    (net (code "280") (name "STAT_3") (class "Default")
      (node (ref "CEL3CC") (pin "A") (pinfunction "A_A") (pintype "passive"))
      (node (ref "CEL3CO") (pin "K") (pinfunction "C_K") (pintype "passive"))
      (node (ref "U$20") (pin "STAT") (pinfunction "STAT_STAT") (pintype "bidirectional"))
    )
    (net (code "281") (name "SUPP+") (class "Default")
      (node (ref "BAT_SUPP") (pin "2") (pinfunction "2_2") (pintype "bidirectional"))
      (node (ref "FUSE") (pin "IN") (pinfunction "IN_IN") (pintype "bidirectional"))
    )
    (net (code "282") (name "S_A0") (class "Default")
      (node (ref "IC3") (pin "23") (pinfunction "23_23") (pintype "passive"))
      (node (ref "U$53") (pin "6") (pinfunction "6_6") (pintype "bidirectional"))
    )
    (net (code "283") (name "S_A1") (class "Default")
      (node (ref "IC3") (pin "24") (pinfunction "24_24") (pintype "passive"))
      (node (ref "U$53") (pin "5") (pinfunction "5_5") (pintype "bidirectional"))
    )
    (net (code "284") (name "S_A2") (class "Default")
      (node (ref "IC3") (pin "25") (pinfunction "25_25") (pintype "passive"))
      (node (ref "U$53") (pin "4") (pinfunction "4_4") (pintype "bidirectional"))
    )
    (net (code "285") (name "S_A3") (class "Default")
      (node (ref "IC3") (pin "26") (pinfunction "26_26") (pintype "passive"))
      (node (ref "U$53") (pin "3") (pinfunction "3_3") (pintype "bidirectional"))
    )
    (net (code "286") (name "S_A4") (class "Default")
      (node (ref "IC3") (pin "27") (pinfunction "27_27") (pintype "passive"))
      (node (ref "U$53") (pin "2") (pinfunction "2_2") (pintype "bidirectional"))
    )
    (net (code "287") (name "S_A5") (class "Default")
      (node (ref "IC3") (pin "28") (pinfunction "28_28") (pintype "passive"))
      (node (ref "U$53") (pin "1") (pinfunction "1_1") (pintype "bidirectional"))
    )
    (net (code "288") (name "S_AREF") (class "Default")
      (node (ref "C8") (pin "1") (pinfunction "1_1") (pintype "passive"))
      (node (ref "IC3") (pin "21") (pinfunction "21_21") (pintype "passive"))
    )
    (net (code "289") (name "S_D2") (class "Default")
      (node (ref "IC3") (pin "4") (pinfunction "4_4") (pintype "passive"))
      (node (ref "U$52") (pin "8") (pinfunction "8_8") (pintype "bidirectional"))
    )
    (net (code "290") (name "S_D3") (class "Default")
      (node (ref "IC3") (pin "5") (pinfunction "5_5") (pintype "passive"))
      (node (ref "U$52") (pin "7") (pinfunction "7_7") (pintype "bidirectional"))
    )
    (net (code "291") (name "S_D4") (class "Default")
      (node (ref "IC3") (pin "6") (pinfunction "6_6") (pintype "passive"))
      (node (ref "U$52") (pin "6") (pinfunction "6_6") (pintype "bidirectional"))
    )
    (net (code "292") (name "S_D5") (class "Default")
      (node (ref "IC3") (pin "11") (pinfunction "11_11") (pintype "passive"))
      (node (ref "U$52") (pin "5") (pinfunction "5_5") (pintype "bidirectional"))
    )
    (net (code "293") (name "S_D6") (class "Default")
      (node (ref "IC3") (pin "12") (pinfunction "12_12") (pintype "passive"))
      (node (ref "U$52") (pin "4") (pinfunction "4_4") (pintype "bidirectional"))
    )
    (net (code "294") (name "S_D7") (class "Default")
      (node (ref "IC3") (pin "13") (pinfunction "13_13") (pintype "passive"))
      (node (ref "U$52") (pin "3") (pinfunction "3_3") (pintype "bidirectional"))
    )
    (net (code "295") (name "S_D8") (class "Default")
      (node (ref "IC3") (pin "14") (pinfunction "14_14") (pintype "passive"))
      (node (ref "U$52") (pin "2") (pinfunction "2_2") (pintype "bidirectional"))
    )
    (net (code "296") (name "S_D9") (class "Default")
      (node (ref "IC3") (pin "15") (pinfunction "15_15") (pintype "passive"))
      (node (ref "U$52") (pin "1") (pinfunction "1_1") (pintype "bidirectional"))
    )
    (net (code "297") (name "S_D10") (class "Default")
      (node (ref "IC3") (pin "16") (pinfunction "16_16") (pintype "passive"))
      (node (ref "U$53") (pin "10") (pinfunction "10_10") (pintype "bidirectional"))
    )
    (net (code "298") (name "S_D11") (class "Default")
      (node (ref "IC3") (pin "17") (pinfunction "17_17") (pintype "passive"))
      (node (ref "U$53") (pin "9") (pinfunction "9_9") (pintype "bidirectional"))
    )
    (net (code "299") (name "S_D12") (class "Default")
      (node (ref "IC3") (pin "18") (pinfunction "18_18") (pintype "passive"))
      (node (ref "U$53") (pin "8") (pinfunction "8_8") (pintype "bidirectional"))
    )
    (net (code "300") (name "S_D13") (class "Default")
      (node (ref "IC3") (pin "19") (pinfunction "19_19") (pintype "passive"))
      (node (ref "U$53") (pin "7") (pinfunction "7_7") (pintype "bidirectional"))
    )
    (net (code "301") (name "S_GND") (class "Default")
      (node (ref "BAT6") (pin "2") (pinfunction "2_2") (pintype "bidirectional"))
      (node (ref "C5") (pin "2") (pinfunction "2_2") (pintype "passive"))
      (node (ref "C6") (pin "1") (pinfunction "1_1") (pintype "passive"))
      (node (ref "C7") (pin "1") (pinfunction "1_1") (pintype "passive"))
      (node (ref "C8") (pin "2") (pinfunction "2_2") (pintype "passive"))
      (node (ref "IC3") (pin "22") (pinfunction "22_22") (pintype "passive"))
      (node (ref "IC3") (pin "8") (pinfunction "8_8") (pintype "passive"))
      (node (ref "JP3") (pin "6") (pinfunction "6_6") (pintype "passive"))
      (node (ref "MEGA_RST1") (pin "3") (pinfunction "2_3") (pintype "passive"))
      (node (ref "U$51") (pin "2") (pinfunction "2_2") (pintype "bidirectional"))
    )
    (net (code "302") (name "TX0") (class "Default")
      (node (ref "ATMEGA_2560") (pin "TX0") (pinfunction "TX0_TX0") (pintype "bidirectional"))
      (node (ref "RFID1") (pin "2") (pinfunction "2_2") (pintype "bidirectional"))
      (node (ref "U$12") (pin "TX0") (pinfunction "TX_TX0") (pintype "bidirectional"))
    )
    (net (code "303") (name "TX1") (class "Default")
      (node (ref "ATMEGA_2560") (pin "TX1") (pinfunction "TX1_TX1") (pintype "bidirectional"))
      (node (ref "N-M") (pin "4") (pinfunction "4_4") (pintype "passive"))
      (node (ref "RFID2") (pin "4") (pinfunction "4_4") (pintype "bidirectional"))
      (node (ref "SW1") (pin "2") (pinfunction "2_2") (pintype "passive"))
    )
    (net (code "304") (name "TX2") (class "Default")
      (node (ref "ATMEGA_2560") (pin "TX2") (pinfunction "TX2_TX2") (pintype "bidirectional"))
      (node (ref "RFID2") (pin "6") (pinfunction "6_6") (pintype "bidirectional"))
      (node (ref "SW1") (pin "4") (pinfunction "4_4") (pintype "passive"))
    )
    (net (code "305") (name "TX3") (class "Default")
      (node (ref "ATMEGA_2560") (pin "TX3") (pinfunction "TX3_TX3") (pintype "bidirectional"))
      (node (ref "RFID2") (pin "8") (pinfunction "8_8") (pintype "bidirectional"))
      (node (ref "SW1") (pin "6") (pinfunction "6_6") (pintype "passive"))
    )
    (net (code "306") (name "TXD") (class "Default")
      (node (ref "IC3") (pin "3") (pinfunction "3_3") (pintype "passive"))
      (node (ref "JP3") (pin "2") (pinfunction "2_2") (pintype "passive"))
      (node (ref "U$52") (pin "9") (pinfunction "9_9") (pintype "bidirectional"))
    )
    (net (code "307") (name "U1") (class "Default")
      (node (ref "IC1") (pin "16") (pinfunction "16_16") (pintype "passive"))
      (node (ref "L1") (pin "K") (pinfunction "C_K") (pintype "passive"))
      (node (ref "REL1") (pin "-") (pinfunction "-_-") (pintype "bidirectional"))
      (node (ref "ULN_SIG") (pin "3") (pinfunction "3_3") (pintype "bidirectional"))
    )
    (net (code "308") (name "U2") (class "Default")
      (node (ref "IC1") (pin "15") (pinfunction "15_15") (pintype "passive"))
      (node (ref "L2") (pin "K") (pinfunction "C_K") (pintype "passive"))
      (node (ref "REL2") (pin "-") (pinfunction "-_-") (pintype "bidirectional"))
      (node (ref "ULN_SIG") (pin "2") (pinfunction "2_2") (pintype "bidirectional"))
    )
    (net (code "309") (name "U3") (class "Default")
      (node (ref "IC1") (pin "14") (pinfunction "14_14") (pintype "passive"))
      (node (ref "L3") (pin "K") (pinfunction "C_K") (pintype "passive"))
      (node (ref "REL3") (pin "-") (pinfunction "-_-") (pintype "bidirectional"))
      (node (ref "ULN_SIG") (pin "1") (pinfunction "1_1") (pintype "bidirectional"))
    )
    (net (code "310") (name "U4") (class "Default")
      (node (ref "IC1") (pin "13") (pinfunction "13_13") (pintype "passive"))
      (node (ref "L4") (pin "K") (pinfunction "C_K") (pintype "passive"))
      (node (ref "U45") (pin "2") (pinfunction "2_2") (pintype "bidirectional"))
    )
    (net (code "311") (name "U5") (class "Default")
      (node (ref "IC1") (pin "12") (pinfunction "12_12") (pintype "passive"))
      (node (ref "L5") (pin "K") (pinfunction "C_K") (pintype "passive"))
      (node (ref "U45") (pin "1") (pinfunction "1_1") (pintype "bidirectional"))
    )
    (net (code "312") (name "U6") (class "Default")
      (node (ref "IC1") (pin "11") (pinfunction "11_11") (pintype "passive"))
      (node (ref "L6") (pin "K") (pinfunction "C_K") (pintype "passive"))
      (node (ref "U67") (pin "2") (pinfunction "2_2") (pintype "bidirectional"))
    )
    (net (code "313") (name "U7") (class "Default")
      (node (ref "IC1") (pin "10") (pinfunction "10_10") (pintype "passive"))
      (node (ref "L7") (pin "K") (pinfunction "C_K") (pintype "passive"))
      (node (ref "U67") (pin "1") (pinfunction "1_1") (pintype "bidirectional"))
    )
    (net (code "314") (name "VBAT_1") (class "Default")
      (node (ref "BALANCE") (pin "4") (pinfunction "4_4") (pintype "bidirectional"))
      (node (ref "BALANCE1") (pin "4") (pinfunction "4_4") (pintype "bidirectional"))
      (node (ref "R2") (pin "P$1") (pinfunction "1_P$1") (pintype "passive"))
      (node (ref "U$18") (pin "VBAT") (pinfunction "VBAT_VBAT") (pintype "bidirectional"))
      (node (ref "U$21") (pin "2") (pinfunction "2_2") (pintype "bidirectional"))
    )
    (net (code "315") (name "VBAT_2") (class "Default")
      (node (ref "BALANCE") (pin "3") (pinfunction "3_3") (pintype "bidirectional"))
      (node (ref "BALANCE1") (pin "3") (pinfunction "3_3") (pintype "bidirectional"))
      (node (ref "R35") (pin "P$1") (pinfunction "1_P$1") (pintype "passive"))
      (node (ref "U$19") (pin "VBAT") (pinfunction "VBAT_VBAT") (pintype "bidirectional"))
      (node (ref "U$21") (pin "1") (pinfunction "1_1") (pintype "bidirectional"))
      (node (ref "U$22") (pin "2") (pinfunction "2_2") (pintype "bidirectional"))
    )
    (net (code "316") (name "VBAT_3") (class "Default")
      (node (ref "BALANCE") (pin "2") (pinfunction "2_2") (pintype "bidirectional"))
      (node (ref "BALANCE1") (pin "2") (pinfunction "2_2") (pintype "bidirectional"))
      (node (ref "R37") (pin "P$1") (pinfunction "1_P$1") (pintype "passive"))
      (node (ref "U$20") (pin "VBAT") (pinfunction "VBAT_VBAT") (pintype "bidirectional"))
      (node (ref "U$22") (pin "1") (pinfunction "1_1") (pintype "bidirectional"))
      (node (ref "U$23") (pin "2") (pinfunction "2_2") (pintype "bidirectional"))
    )
    (net (code "317") (name "V_SUPP") (class "Default")
      (node (ref "BAT1") (pin "1") (pinfunction "1_1") (pintype "bidirectional"))
      (node (ref "IC1") (pin "9") (pinfunction "9_9") (pintype "passive"))
      (node (ref "IC2") (pin "8") (pinfunction "8_8") (pintype "passive"))
      (node (ref "LSA_2") (pin "9") (pinfunction "9_9") (pintype "passive"))
      (node (ref "PROX1") (pin "3") (pinfunction "3_3") (pintype "bidirectional"))
      (node (ref "PROX2") (pin "3") (pinfunction "3_3") (pintype "bidirectional"))
      (node (ref "PROX3") (pin "3") (pinfunction "3_3") (pintype "bidirectional"))
      (node (ref "REL1") (pin "+") (pinfunction "+_+") (pintype "bidirectional"))
      (node (ref "REL2") (pin "+") (pinfunction "+_+") (pintype "bidirectional"))
      (node (ref "REL3") (pin "+") (pinfunction "+_+") (pintype "bidirectional"))
      (node (ref "U$13") (pin "IN+") (pinfunction "IN+_IN+") (pintype "bidirectional"))
      (node (ref "U$3") (pin "IN+") (pinfunction "IN+_IN+") (pintype "bidirectional"))
      (node (ref "U$32") (pin "O1") (pinfunction "O1_O1") (pintype "bidirectional"))
      (node (ref "U$6") (pin "IN+") (pinfunction "IN+_IN+") (pintype "bidirectional"))
      (node (ref "U$7") (pin "IN+") (pinfunction "IN+_IN+") (pintype "bidirectional"))
      (node (ref "U$8") (pin "IN+") (pinfunction "IN+_IN+") (pintype "bidirectional"))
      (node (ref "U$9") (pin "IN+") (pinfunction "IN+_IN+") (pintype "bidirectional"))
    )
    (net (code "318") (name "XTAL1") (class "Default")
      (node (ref "C6") (pin "2") (pinfunction "2_2") (pintype "passive"))
      (node (ref "IC3") (pin "9") (pinfunction "9_9") (pintype "passive"))
      (node (ref "Q3") (pin "2") (pinfunction "2_2") (pintype "passive"))
    )
    (net (code "319") (name "XTAL2") (class "Default")
      (node (ref "C7") (pin "2") (pinfunction "2_2") (pintype "passive"))
      (node (ref "IC3") (pin "10") (pinfunction "10_10") (pintype "passive"))
      (node (ref "Q3") (pin "1") (pinfunction "1_1") (pintype "passive"))
    )
    (net (code "320") (name "unconnected-(ATMEGA_2560-Pad5V1)") (class "Default")
      (node (ref "ATMEGA_2560") (pin "5V1") (pinfunction "5V1_5V1") (pintype "bidirectional"))
    )
    (net (code "321") (name "unconnected-(ATMEGA_2560-Pad5V2)") (class "Default")
      (node (ref "ATMEGA_2560") (pin "5V2") (pinfunction "5V2_5V2") (pintype "bidirectional"))
    )
    (net (code "322") (name "unconnected-(ATMEGA_2560-PadGD3)") (class "Default")
      (node (ref "ATMEGA_2560") (pin "GD3") (pinfunction "GD3_GD3") (pintype "bidirectional"))
    )
    (net (code "323") (name "unconnected-(ATMEGA_2560-PadGD4)") (class "Default")
      (node (ref "ATMEGA_2560") (pin "GD4") (pinfunction "GD4_GD4") (pintype "bidirectional"))
    )
    (net (code "324") (name "unconnected-(C_GND-Pad3)") (class "Default")
      (node (ref "C_GND") (pin "3") (pinfunction "3_3") (pintype "bidirectional"))
    )
    (net (code "325") (name "unconnected-(IC2-Pad1)") (class "Default")
      (node (ref "IC2") (pin "1") (pinfunction "1_1") (pintype "passive"))
    )
    (net (code "326") (name "unconnected-(IC2-Pad2)") (class "Default")
      (node (ref "IC2") (pin "2") (pinfunction "2_2") (pintype "passive"))
    )
    (net (code "327") (name "unconnected-(IC2-Pad3)") (class "Default")
      (node (ref "IC2") (pin "3") (pinfunction "3_3") (pintype "passive"))
    )
    (net (code "328") (name "unconnected-(JP3-Pad5)") (class "Default")
      (node (ref "JP3") (pin "5") (pinfunction "5_5") (pintype "passive"))
    )
    (net (code "329") (name "unconnected-(LSA_2-Pad1)") (class "Default")
      (node (ref "LSA_2") (pin "1") (pinfunction "1_1") (pintype "passive"))
    )
    (net (code "330") (name "unconnected-(LSA_2-Pad2)") (class "Default")
      (node (ref "LSA_2") (pin "2") (pinfunction "2_2") (pintype "passive"))
    )
    (net (code "331") (name "unconnected-(LSA_2-Pad3)") (class "Default")
      (node (ref "LSA_2") (pin "3") (pinfunction "3_3") (pintype "passive"))
    )
    (net (code "332") (name "unconnected-(LSA_2-Pad6)") (class "Default")
      (node (ref "LSA_2") (pin "6") (pinfunction "6_6") (pintype "passive"))
    )
    (net (code "333") (name "unconnected-(LSA_2-Pad7)") (class "Default")
      (node (ref "LSA_2") (pin "7") (pinfunction "7_7") (pintype "passive"))
    )
    (net (code "334") (name "unconnected-(LSA_2-Pad8)") (class "Default")
      (node (ref "LSA_2") (pin "8") (pinfunction "8_8") (pintype "passive"))
    )
    (net (code "335") (name "unconnected-(REL1-PadOUT_2)") (class "Default")
      (node (ref "REL1") (pin "OUT_2") (pinfunction "OUT_2_OUT_2") (pintype "bidirectional"))
    )
    (net (code "336") (name "unconnected-(REL2-PadOUT_2)") (class "Default")
      (node (ref "REL2") (pin "OUT_2") (pinfunction "OUT_2_OUT_2") (pintype "bidirectional"))
    )
    (net (code "337") (name "unconnected-(REL3-PadOUT_2)") (class "Default")
      (node (ref "REL3") (pin "OUT_2") (pinfunction "OUT_2_OUT_2") (pintype "bidirectional"))
    )
    (net (code "338") (name "unconnected-(RFID-Pad4)") (class "Default")
      (node (ref "RFID") (pin "4") (pinfunction "4_4") (pintype "bidirectional"))
    )
    (net (code "339") (name "unconnected-(U$2-PadD0)") (class "Default")
      (node (ref "U$2") (pin "D0") (pinfunction "D0_D0") (pintype "bidirectional"))
    )
    (net (code "340") (name "unconnected-(U$2-PadD1)") (class "Default")
      (node (ref "U$2") (pin "D1") (pinfunction "D1_D1") (pintype "bidirectional"))
    )
    (net (code "341") (name "unconnected-(U$2-PadD2)") (class "Default")
      (node (ref "U$2") (pin "D2") (pinfunction "D2_D2") (pintype "bidirectional"))
    )
    (net (code "342") (name "unconnected-(U$2-PadD3)") (class "Default")
      (node (ref "U$2") (pin "D3") (pinfunction "D3_D3") (pintype "bidirectional"))
    )
    (net (code "343") (name "unconnected-(U$3-PadCS)") (class "Default")
      (node (ref "U$3") (pin "CS") (pinfunction "CS_CS") (pintype "bidirectional"))
    )
    (net (code "344") (name "unconnected-(U$4-Pad3V31)") (class "Default")
      (node (ref "U$4") (pin "3V31") (pinfunction "3V31_3V31") (pintype "bidirectional"))
    )
    (net (code "345") (name "unconnected-(U$4-Pad3V32)") (class "Default")
      (node (ref "U$4") (pin "3V32") (pinfunction "3V32_3V32") (pintype "bidirectional"))
    )
    (net (code "346") (name "unconnected-(U$4-PadCLK)") (class "Default")
      (node (ref "U$4") (pin "CLK") (pinfunction "CLK_CLK") (pintype "bidirectional"))
    )
    (net (code "347") (name "unconnected-(U$4-PadCMD)") (class "Default")
      (node (ref "U$4") (pin "CMD") (pinfunction "CMD_CMD") (pintype "bidirectional"))
    )
    (net (code "348") (name "unconnected-(U$4-PadGND)") (class "Default")
      (node (ref "U$4") (pin "GND") (pinfunction "GND_GND") (pintype "bidirectional"))
    )
    (net (code "349") (name "unconnected-(U$4-PadGND1)") (class "Default")
      (node (ref "U$4") (pin "GND1") (pinfunction "GND1_GND1") (pintype "bidirectional"))
    )
    (net (code "350") (name "unconnected-(U$4-PadRSV)") (class "Default")
      (node (ref "U$4") (pin "RSV") (pinfunction "RSV_RSV") (pintype "bidirectional"))
    )
    (net (code "351") (name "unconnected-(U$4-PadRSV1)") (class "Default")
      (node (ref "U$4") (pin "RSV1") (pinfunction "RSV1_RSV1") (pintype "bidirectional"))
    )
    (net (code "352") (name "unconnected-(U$4-PadSD1)") (class "Default")
      (node (ref "U$4") (pin "SD1") (pinfunction "SD1_SD1") (pintype "bidirectional"))
    )
    (net (code "353") (name "unconnected-(U$4-PadSD2)") (class "Default")
      (node (ref "U$4") (pin "SD2") (pinfunction "SD2_SD2") (pintype "bidirectional"))
    )
    (net (code "354") (name "unconnected-(U$4-PadSD3)") (class "Default")
      (node (ref "U$4") (pin "SD3") (pinfunction "SD3_SD3") (pintype "bidirectional"))
    )
    (net (code "355") (name "unconnected-(U$4-PadSDD)") (class "Default")
      (node (ref "U$4") (pin "SDD") (pinfunction "SDD_SDD") (pintype "bidirectional"))
    )
    (net (code "356") (name "unconnected-(U$6-PadCS)") (class "Default")
      (node (ref "U$6") (pin "CS") (pinfunction "CS_CS") (pintype "bidirectional"))
    )
    (net (code "357") (name "unconnected-(U$9-PadCS)") (class "Default")
      (node (ref "U$9") (pin "CS") (pinfunction "CS_CS") (pintype "bidirectional"))
    )
    (net (code "358") (name "unconnected-(U$10-FSYNC-PadFSY)") (class "Default")
      (node (ref "U$10") (pin "FSY") (pinfunction "FSYNC_FSY") (pintype "bidirectional"))
    )
    (net (code "359") (name "unconnected-(U$10-INTA-PadIA)") (class "Default")
      (node (ref "U$10") (pin "IA") (pinfunction "INTA_IA") (pintype "bidirectional"))
    )
    (net (code "360") (name "unconnected-(U$10-Pad3V3)") (class "Default")
      (node (ref "U$10") (pin "3V3") (pinfunction "3V3_3V3") (pintype "bidirectional"))
    )
    (net (code "361") (name "unconnected-(U$10-PadDRDY)") (class "Default")
      (node (ref "U$10") (pin "DRDY") (pinfunction "DRDY_DRDY") (pintype "bidirectional"))
    )
    (net (code "362") (name "unconnected-(U$11-PadEN)") (class "Default")
      (node (ref "U$11") (pin "EN") (pinfunction "EN_EN") (pintype "bidirectional"))
    )
    (net (code "363") (name "unconnected-(U$11-STATE-PadST)") (class "Default")
      (node (ref "U$11") (pin "ST") (pinfunction "STATE_ST") (pintype "bidirectional"))
    )
    (net (code "364") (name "unconnected-(U$14-PadO2)") (class "Default")
      (node (ref "U$14") (pin "O2") (pinfunction "O2_O2") (pintype "bidirectional"))
    )
    (net (code "365") (name "unconnected-(U$15-PadO2)") (class "Default")
      (node (ref "U$15") (pin "O2") (pinfunction "O2_O2") (pintype "bidirectional"))
    )
    (net (code "366") (name "unconnected-(U$16-PadO2)") (class "Default")
      (node (ref "U$16") (pin "O2") (pinfunction "O2_O2") (pintype "bidirectional"))
    )
    (net (code "367") (name "unconnected-(U$32-PadO2)") (class "Default")
      (node (ref "U$32") (pin "O2") (pinfunction "O2_O2") (pintype "bidirectional"))
    )
    (net (code "368") (name "unconnected-(U$35-Pad3V3)") (class "Default")
      (node (ref "U$35") (pin "3V3") (pinfunction "3V3_3V3") (pintype "bidirectional"))
    )
    (net (code "369") (name "unconnected-(U$35-PadREF)") (class "Default")
      (node (ref "U$35") (pin "REF") (pinfunction "REF_REF") (pintype "bidirectional"))
    )
    (net (code "370") (name "unconnected-(U$35-PadRST1)") (class "Default")
      (node (ref "U$35") (pin "RST1") (pinfunction "RST1_RST1") (pintype "bidirectional"))
    )
    (net (code "371") (name "unconnected-(U$54-Pad1)") (class "Default")
      (node (ref "U$54") (pin "1") (pinfunction "1_1") (pintype "bidirectional"))
    )
    (net (code "372") (name "unconnected-(U$55-Pad1)") (class "Default")
      (node (ref "U$55") (pin "1") (pinfunction "1_1") (pintype "bidirectional"))
    )
    (net (code "373") (name "unconnected-(U$56-Pad1)") (class "Default")
      (node (ref "U$56") (pin "1") (pinfunction "1_1") (pintype "bidirectional"))
    )
    (net (code "374") (name "unconnected-(U$57-Pad1)") (class "Default")
      (node (ref "U$57") (pin "1") (pinfunction "1_1") (pintype "bidirectional"))
    )
    (net (code "375") (name "unconnected-(U$58-Pad1)") (class "Default")
      (node (ref "U$58") (pin "1") (pinfunction "1_1") (pintype "bidirectional"))
    )
    (net (code "376") (name "unconnected-(U$59-Pad1)") (class "Default")
      (node (ref "U$59") (pin "1") (pinfunction "1_1") (pintype "bidirectional"))
    )
    (net (code "377") (name "unconnected-(U$60-Pad1)") (class "Default")
      (node (ref "U$60") (pin "1") (pinfunction "1_1") (pintype "bidirectional"))
    )
    (net (code "378") (name "unconnected-(U$61-Pad1)") (class "Default")
      (node (ref "U$61") (pin "1") (pinfunction "1_1") (pintype "bidirectional"))
    )
    (net (code "379") (name "unconnected-(U$63-Pad1)") (class "Default")
      (node (ref "U$63") (pin "1") (pinfunction "1_1") (pintype "bidirectional"))
    )
    (net (code "380") (name "unconnected-(U$64-Pad1)") (class "Default")
      (node (ref "U$64") (pin "1") (pinfunction "1_1") (pintype "bidirectional"))
    )
  )
)
